# RFMicronHermes_1_1.net
KiCad netlist of a schematic drawn in EAGLE
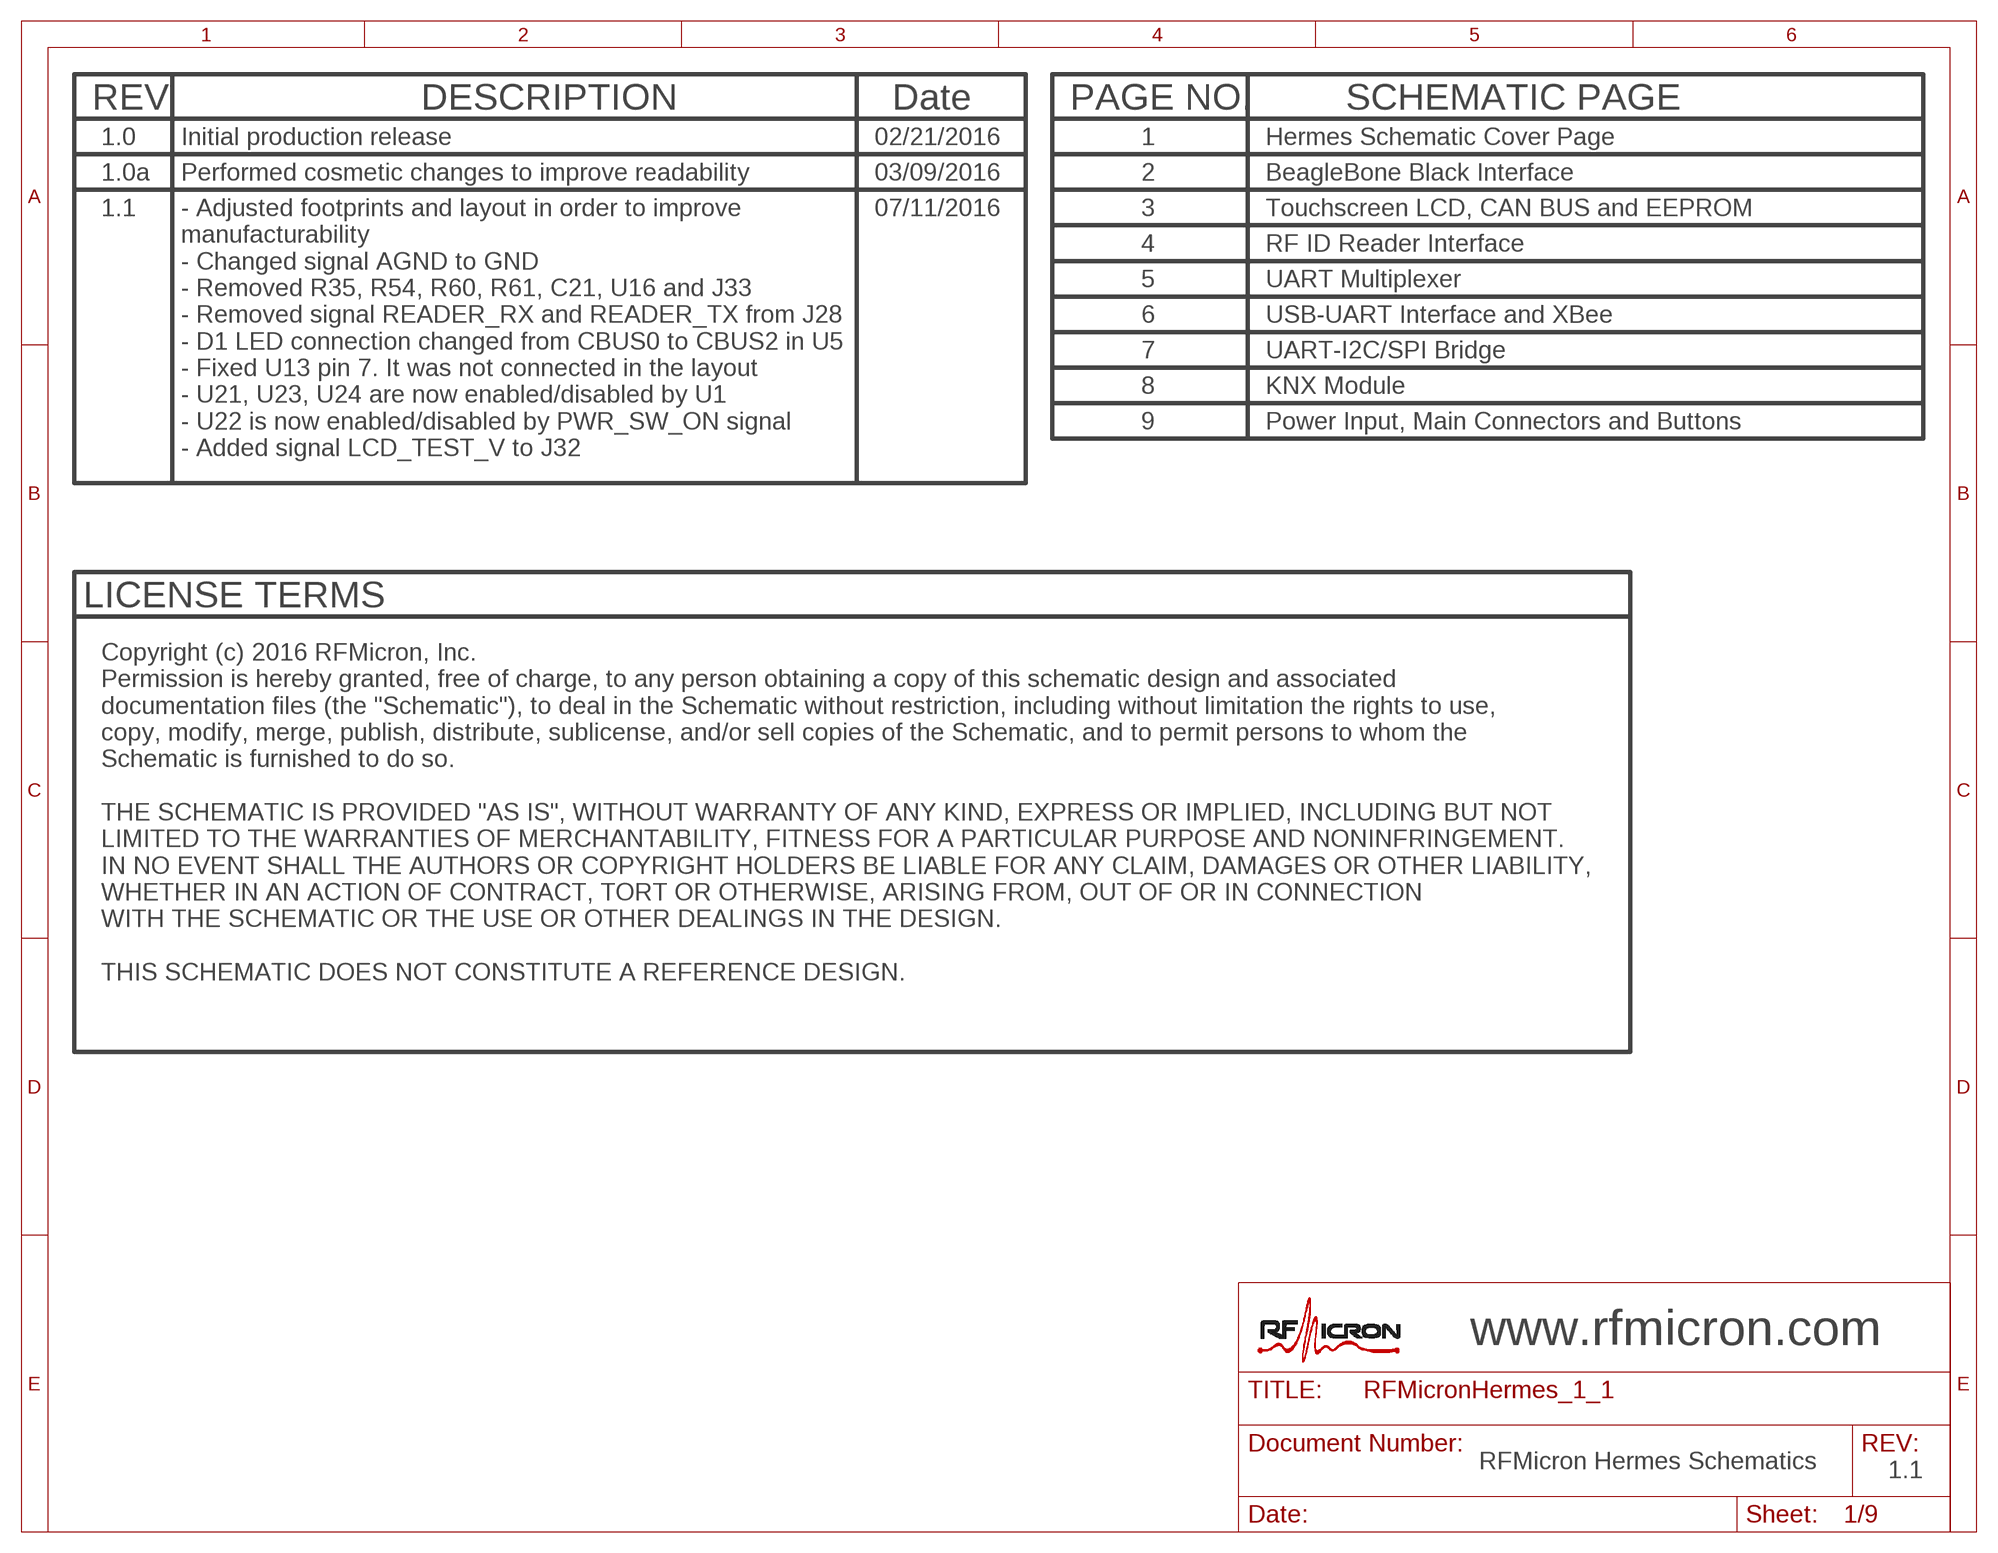
[diagram p0: schematic, sheet 1]
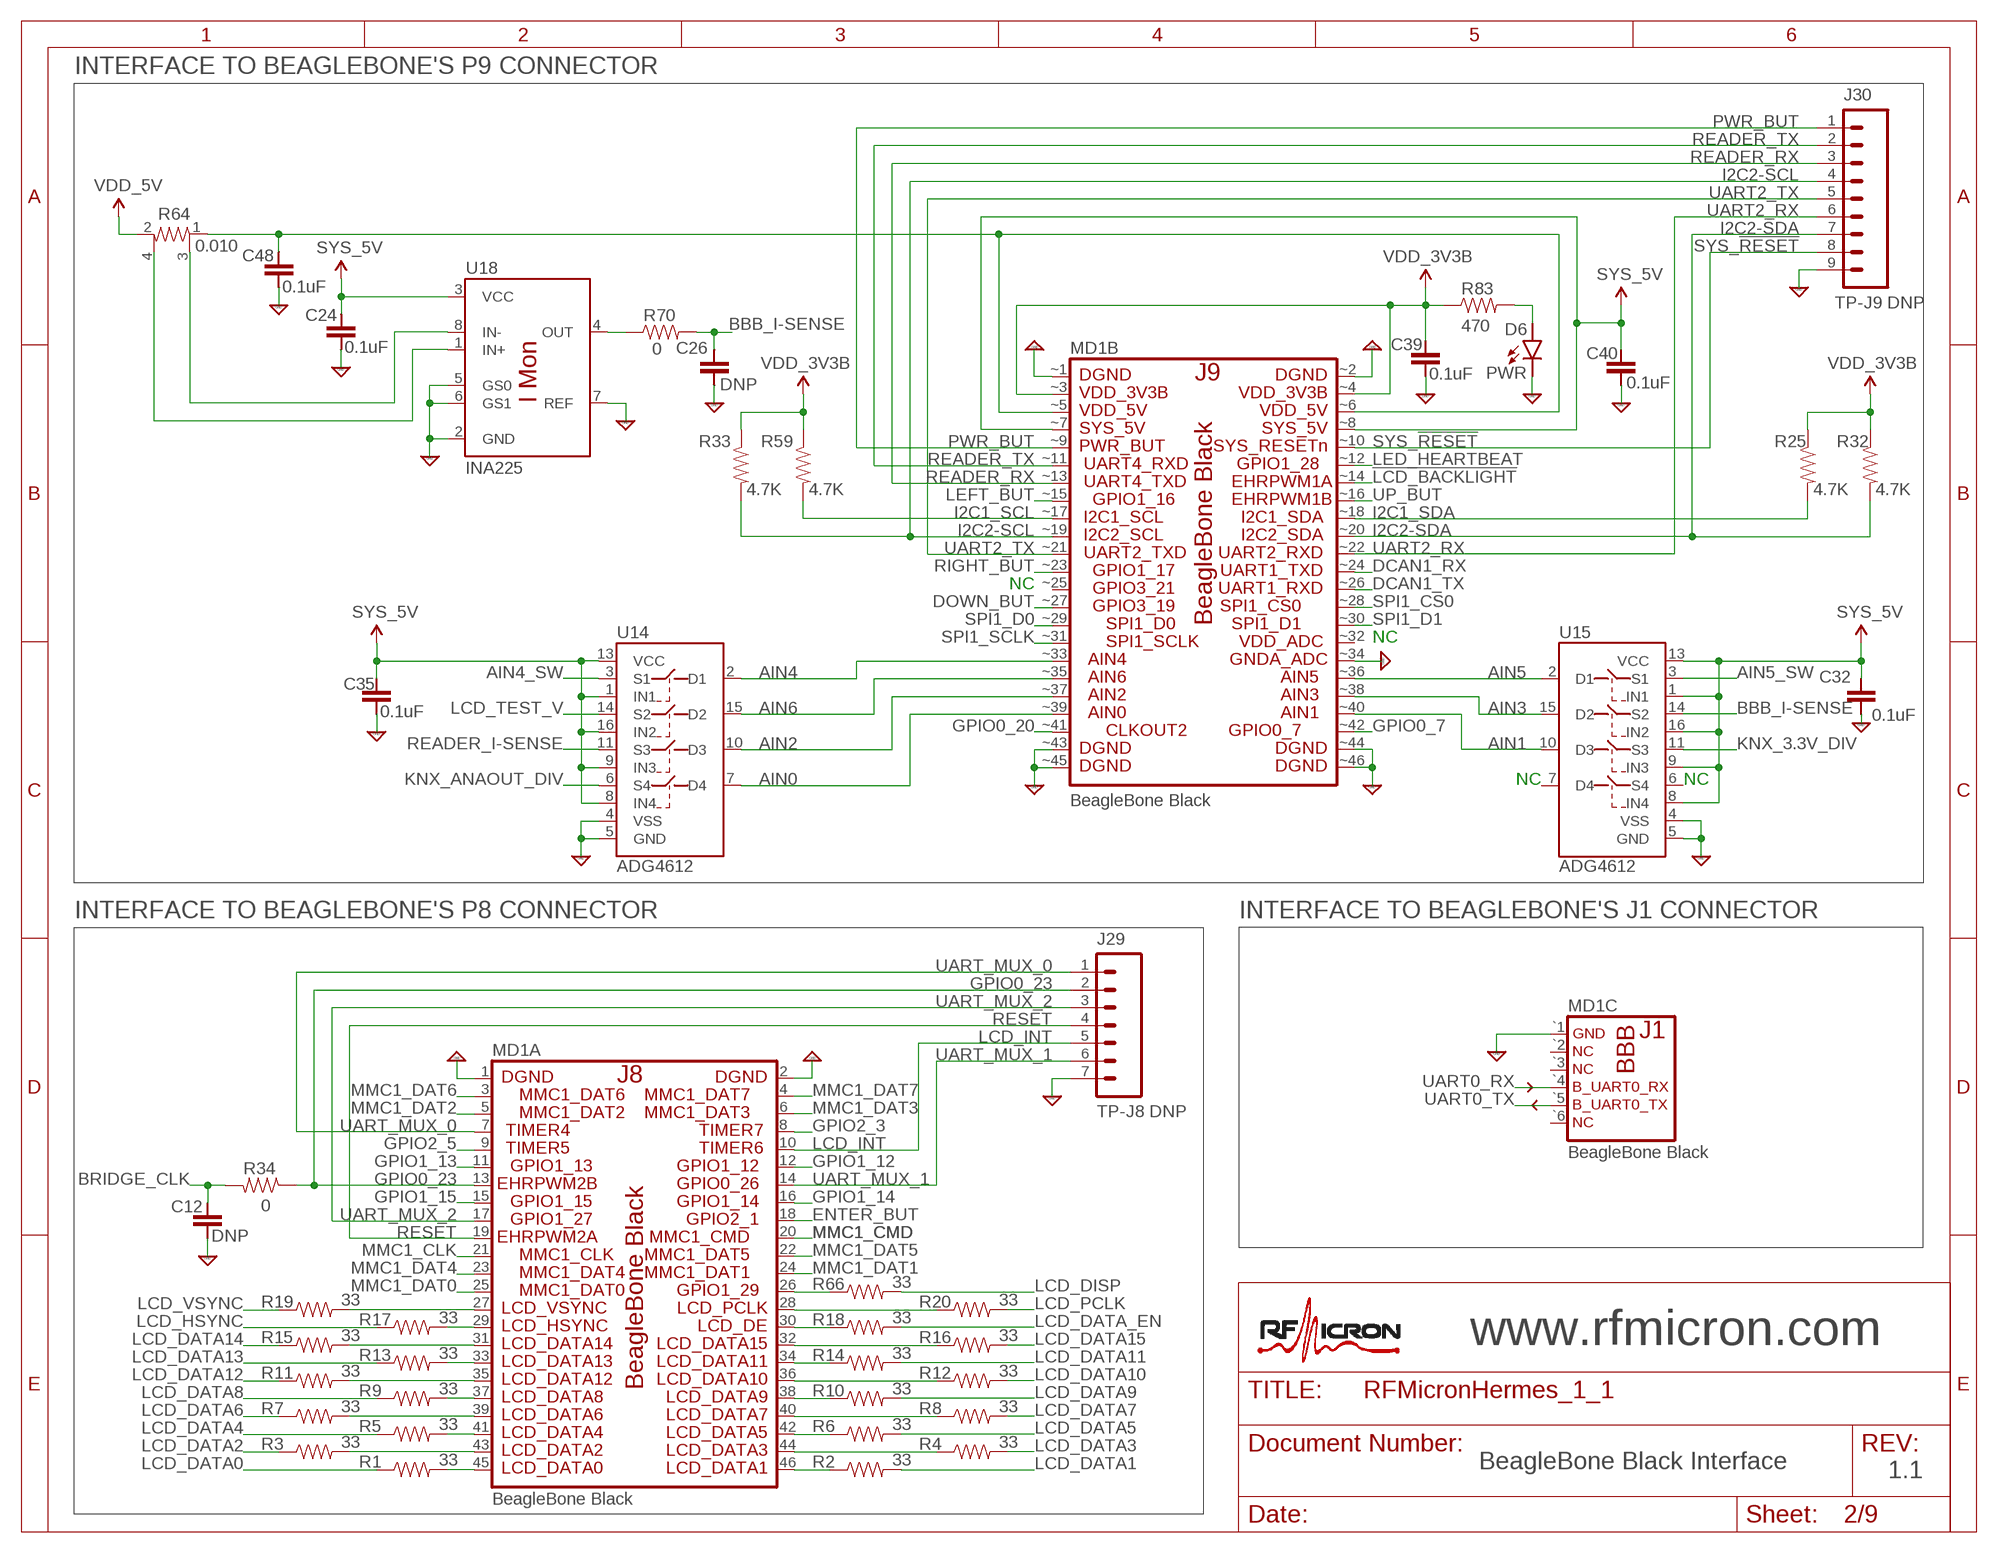
[diagram p1: schematic, sheet 2]
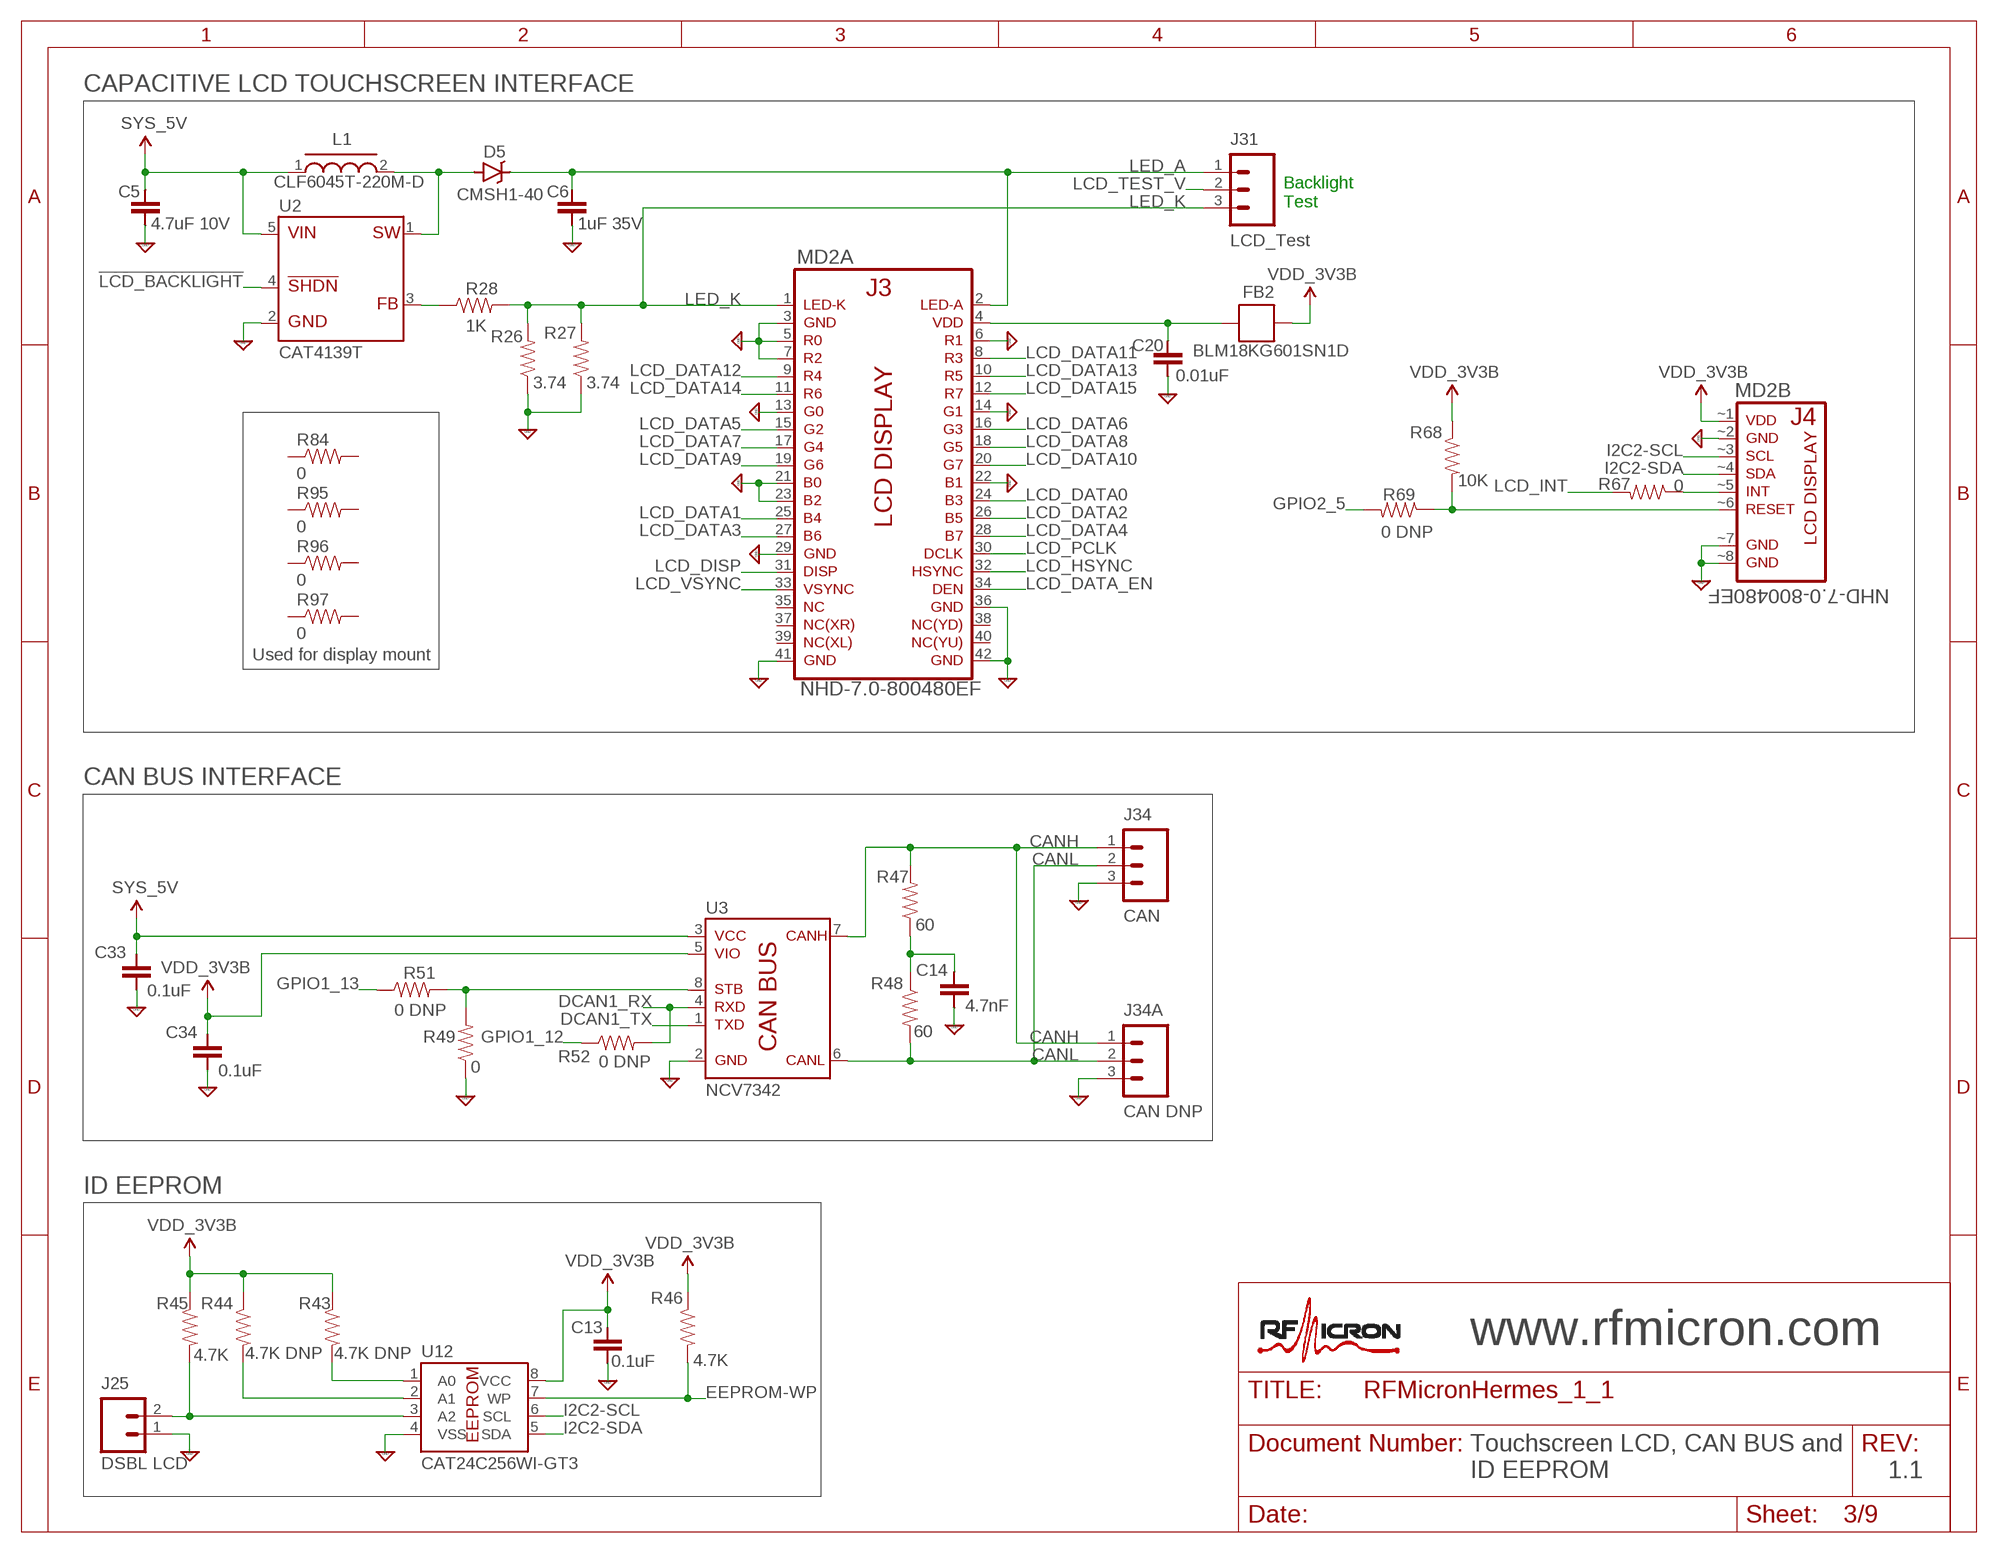
[diagram p2: schematic, sheet 3]
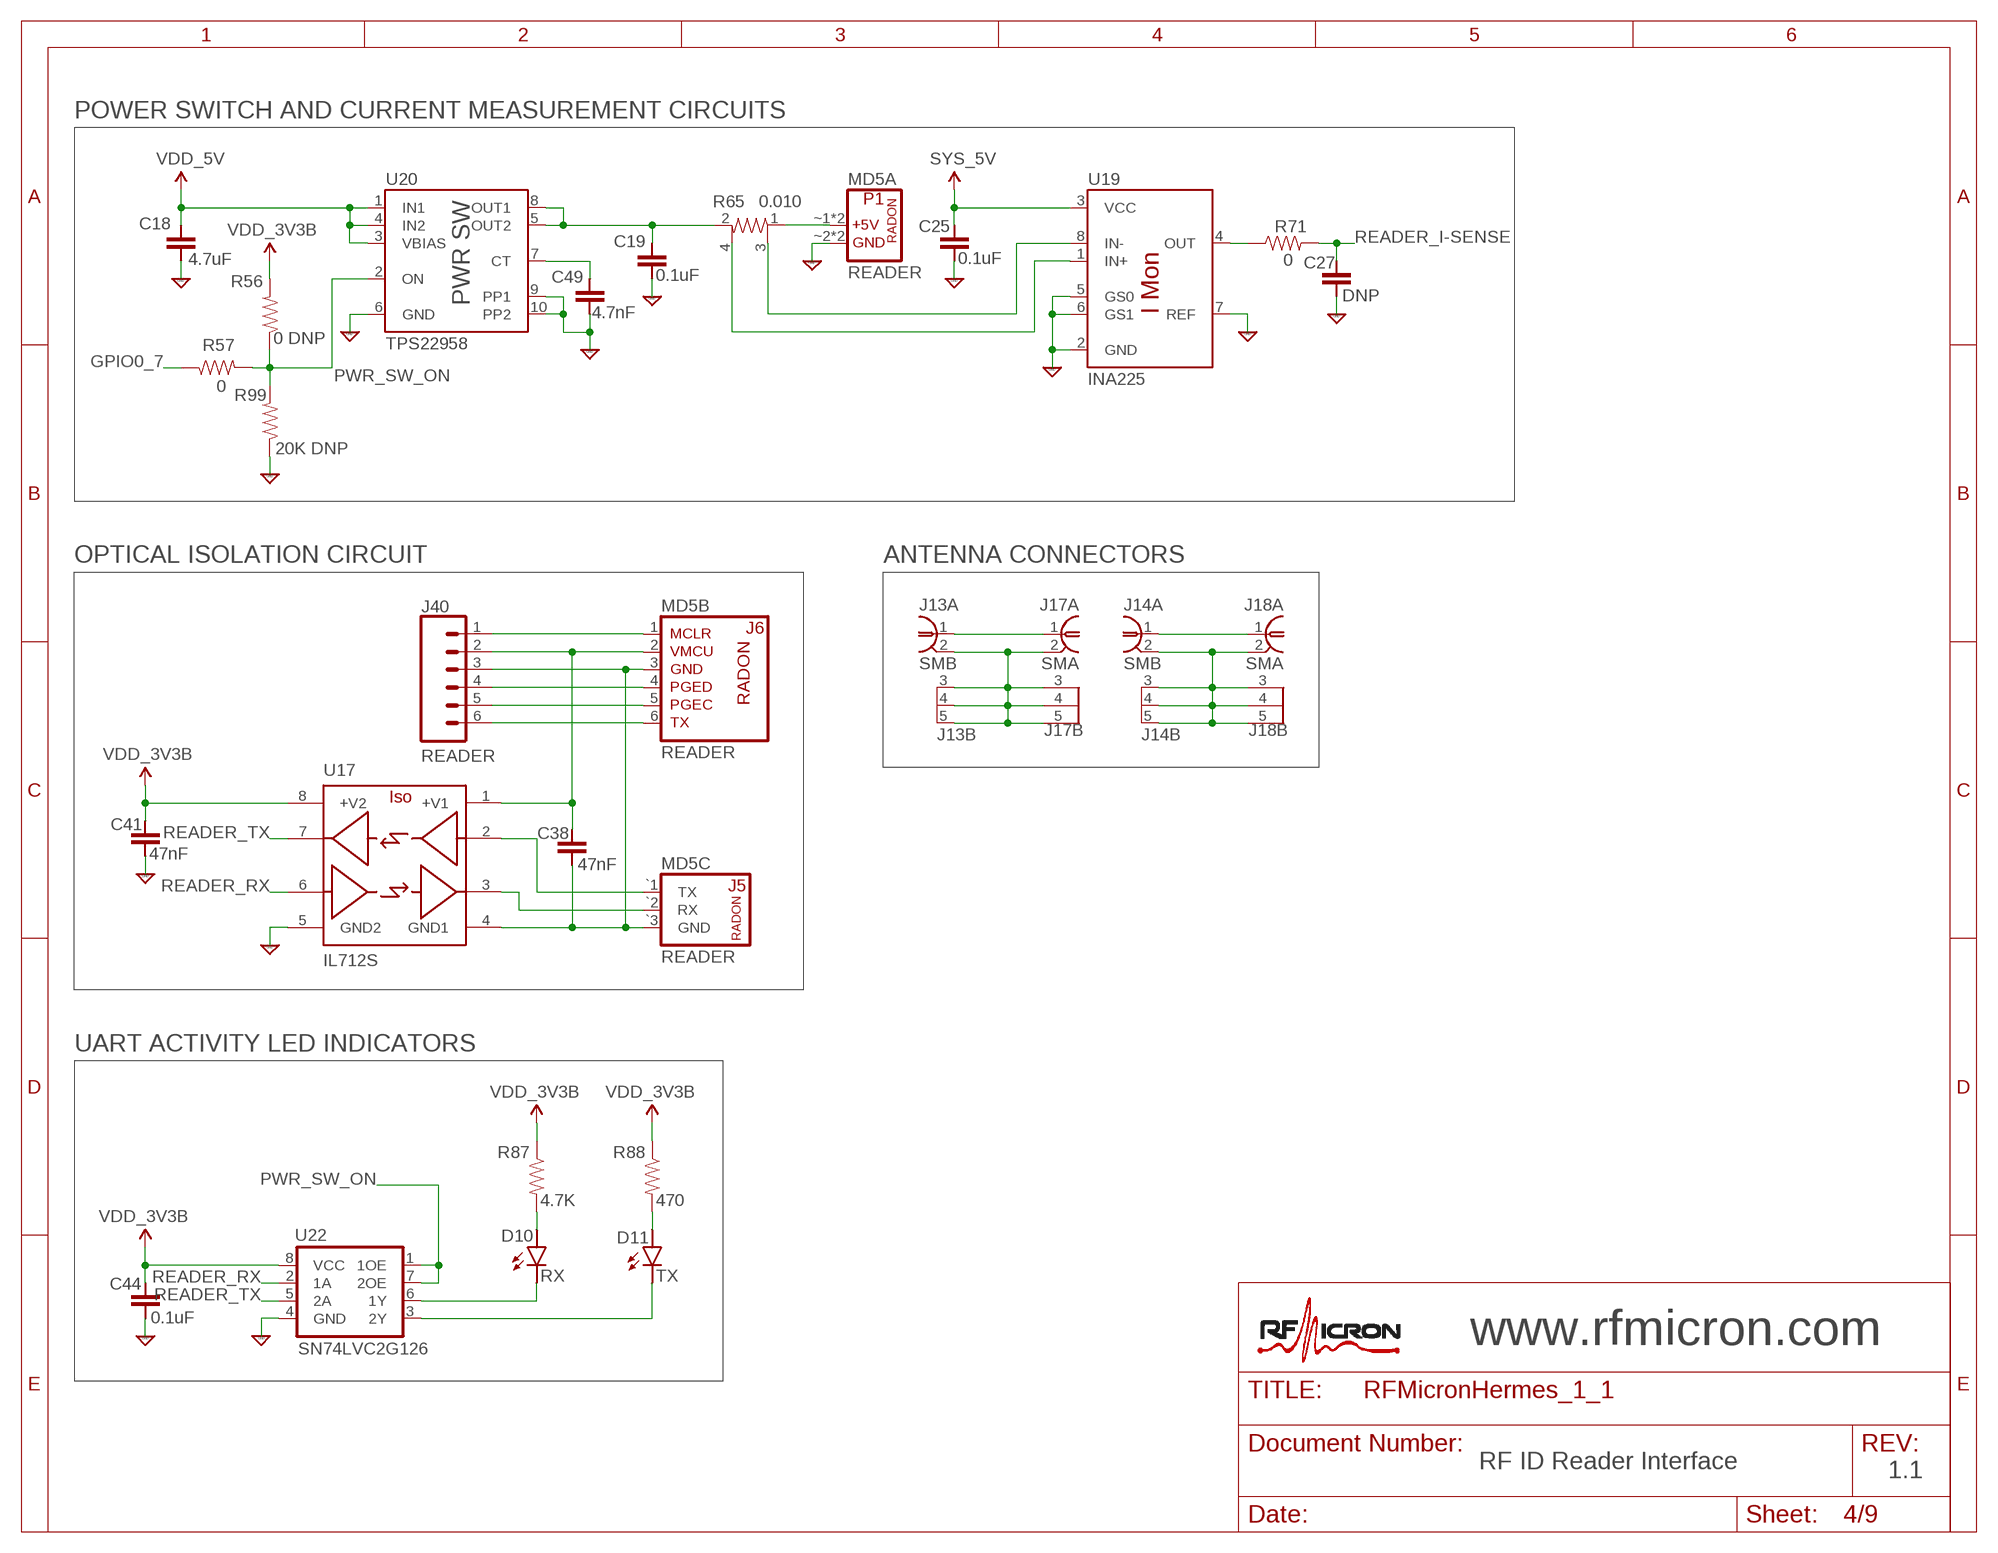
[diagram p3: schematic, sheet 4]
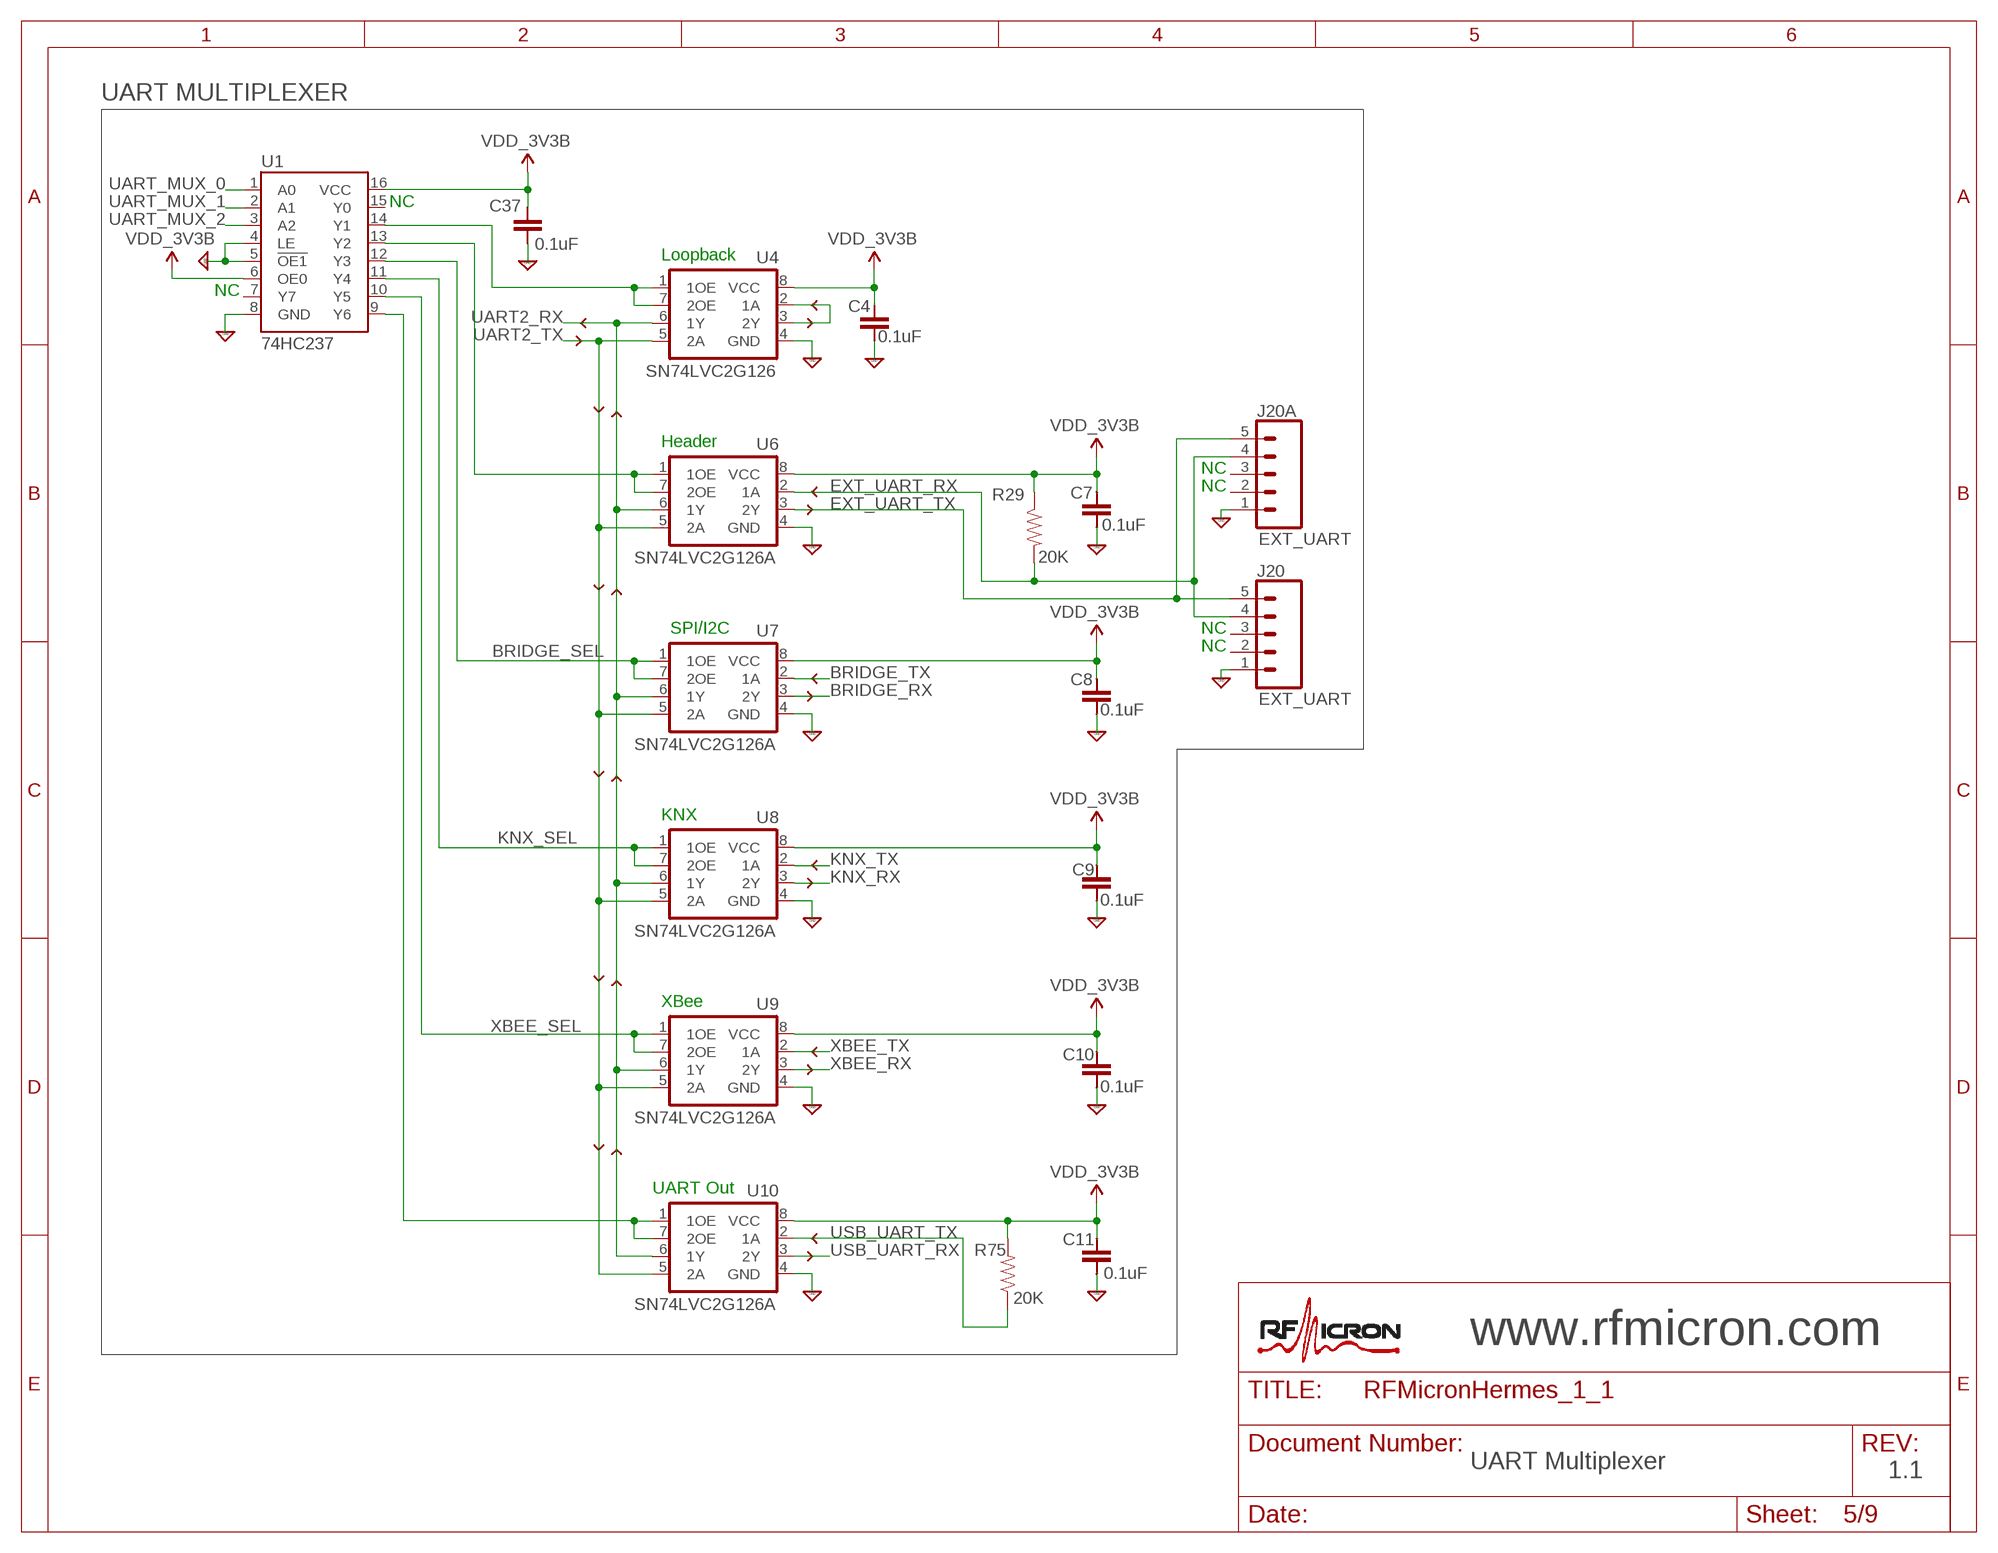
[diagram p4: schematic, sheet 5]
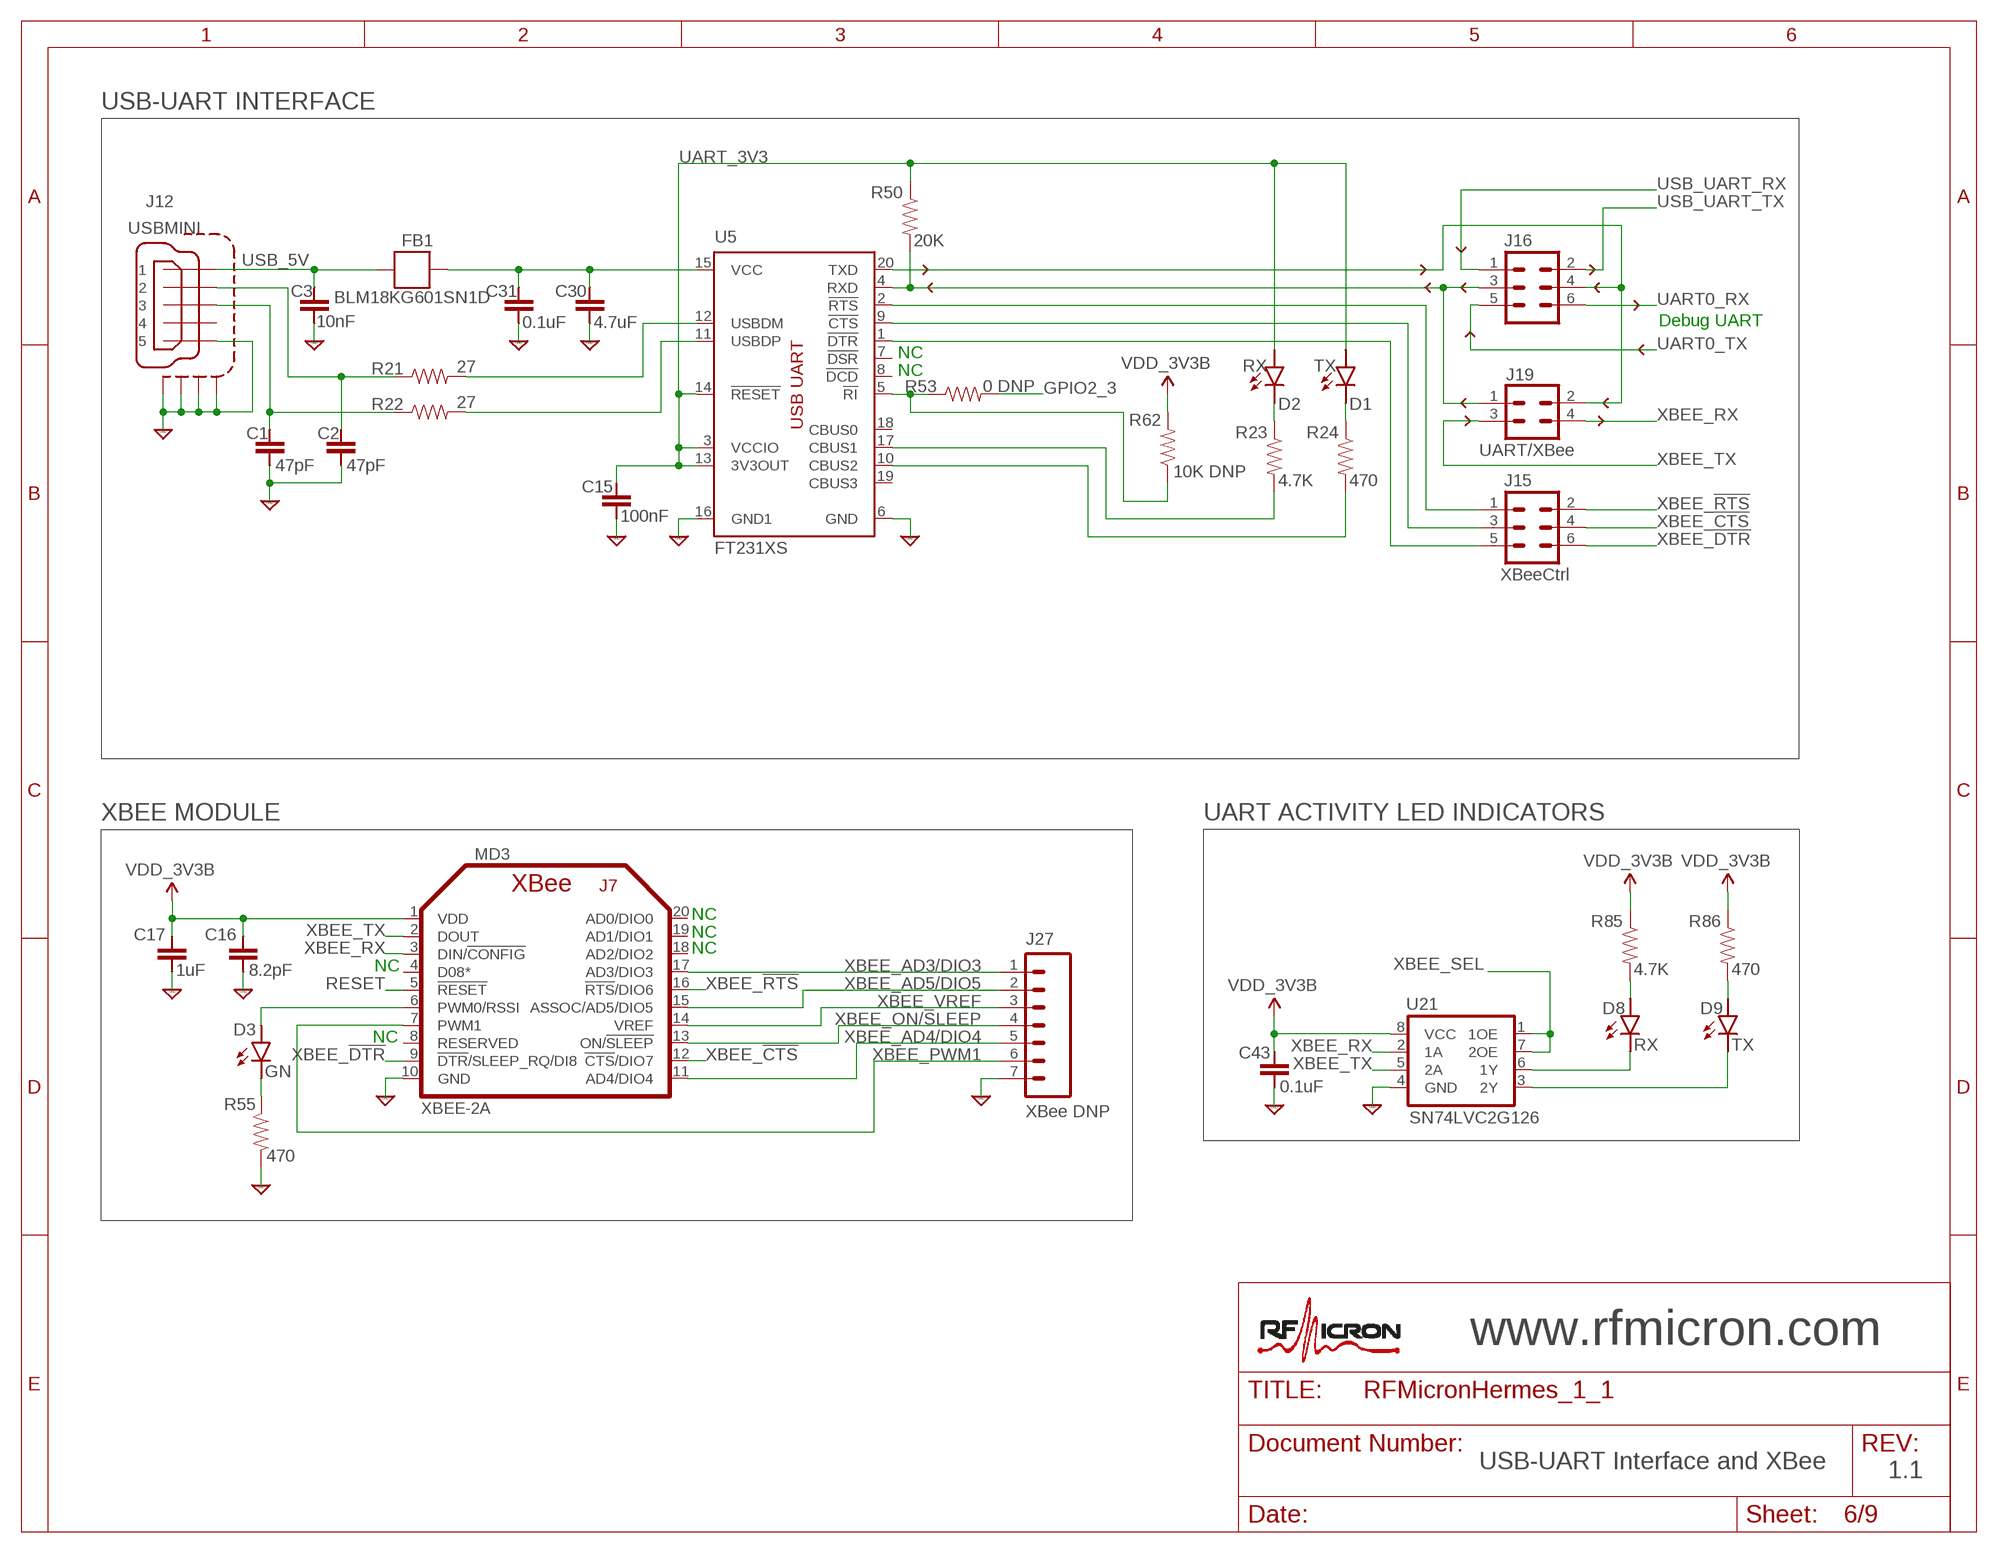
[diagram p5: schematic, sheet 6]
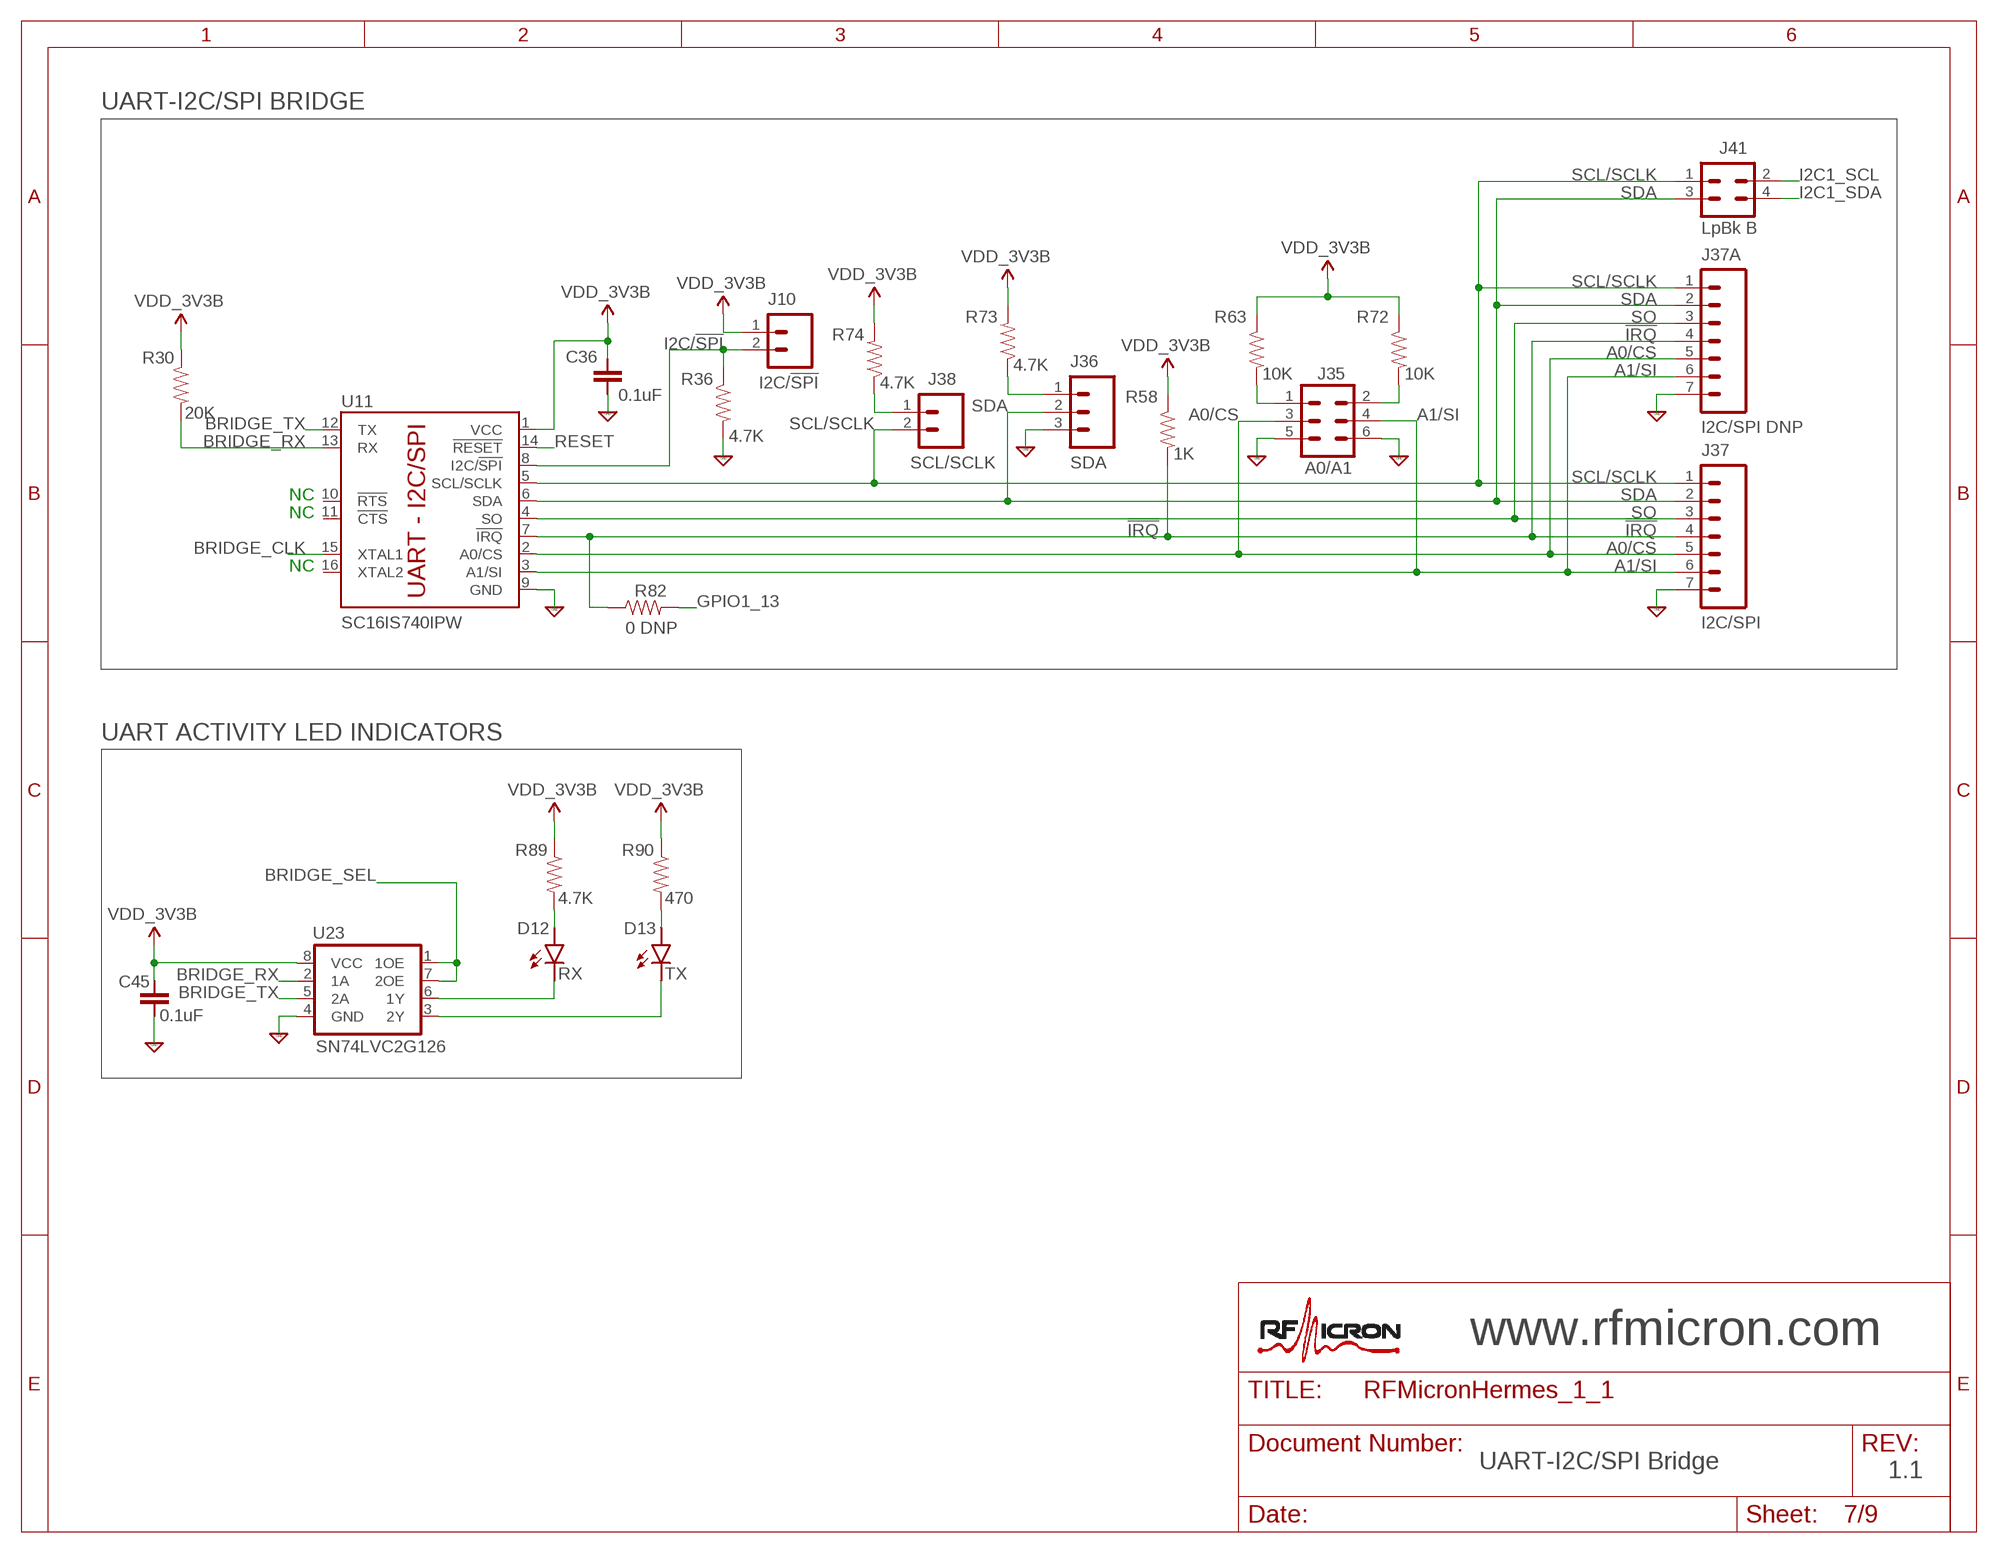
[diagram p6: schematic, sheet 7]
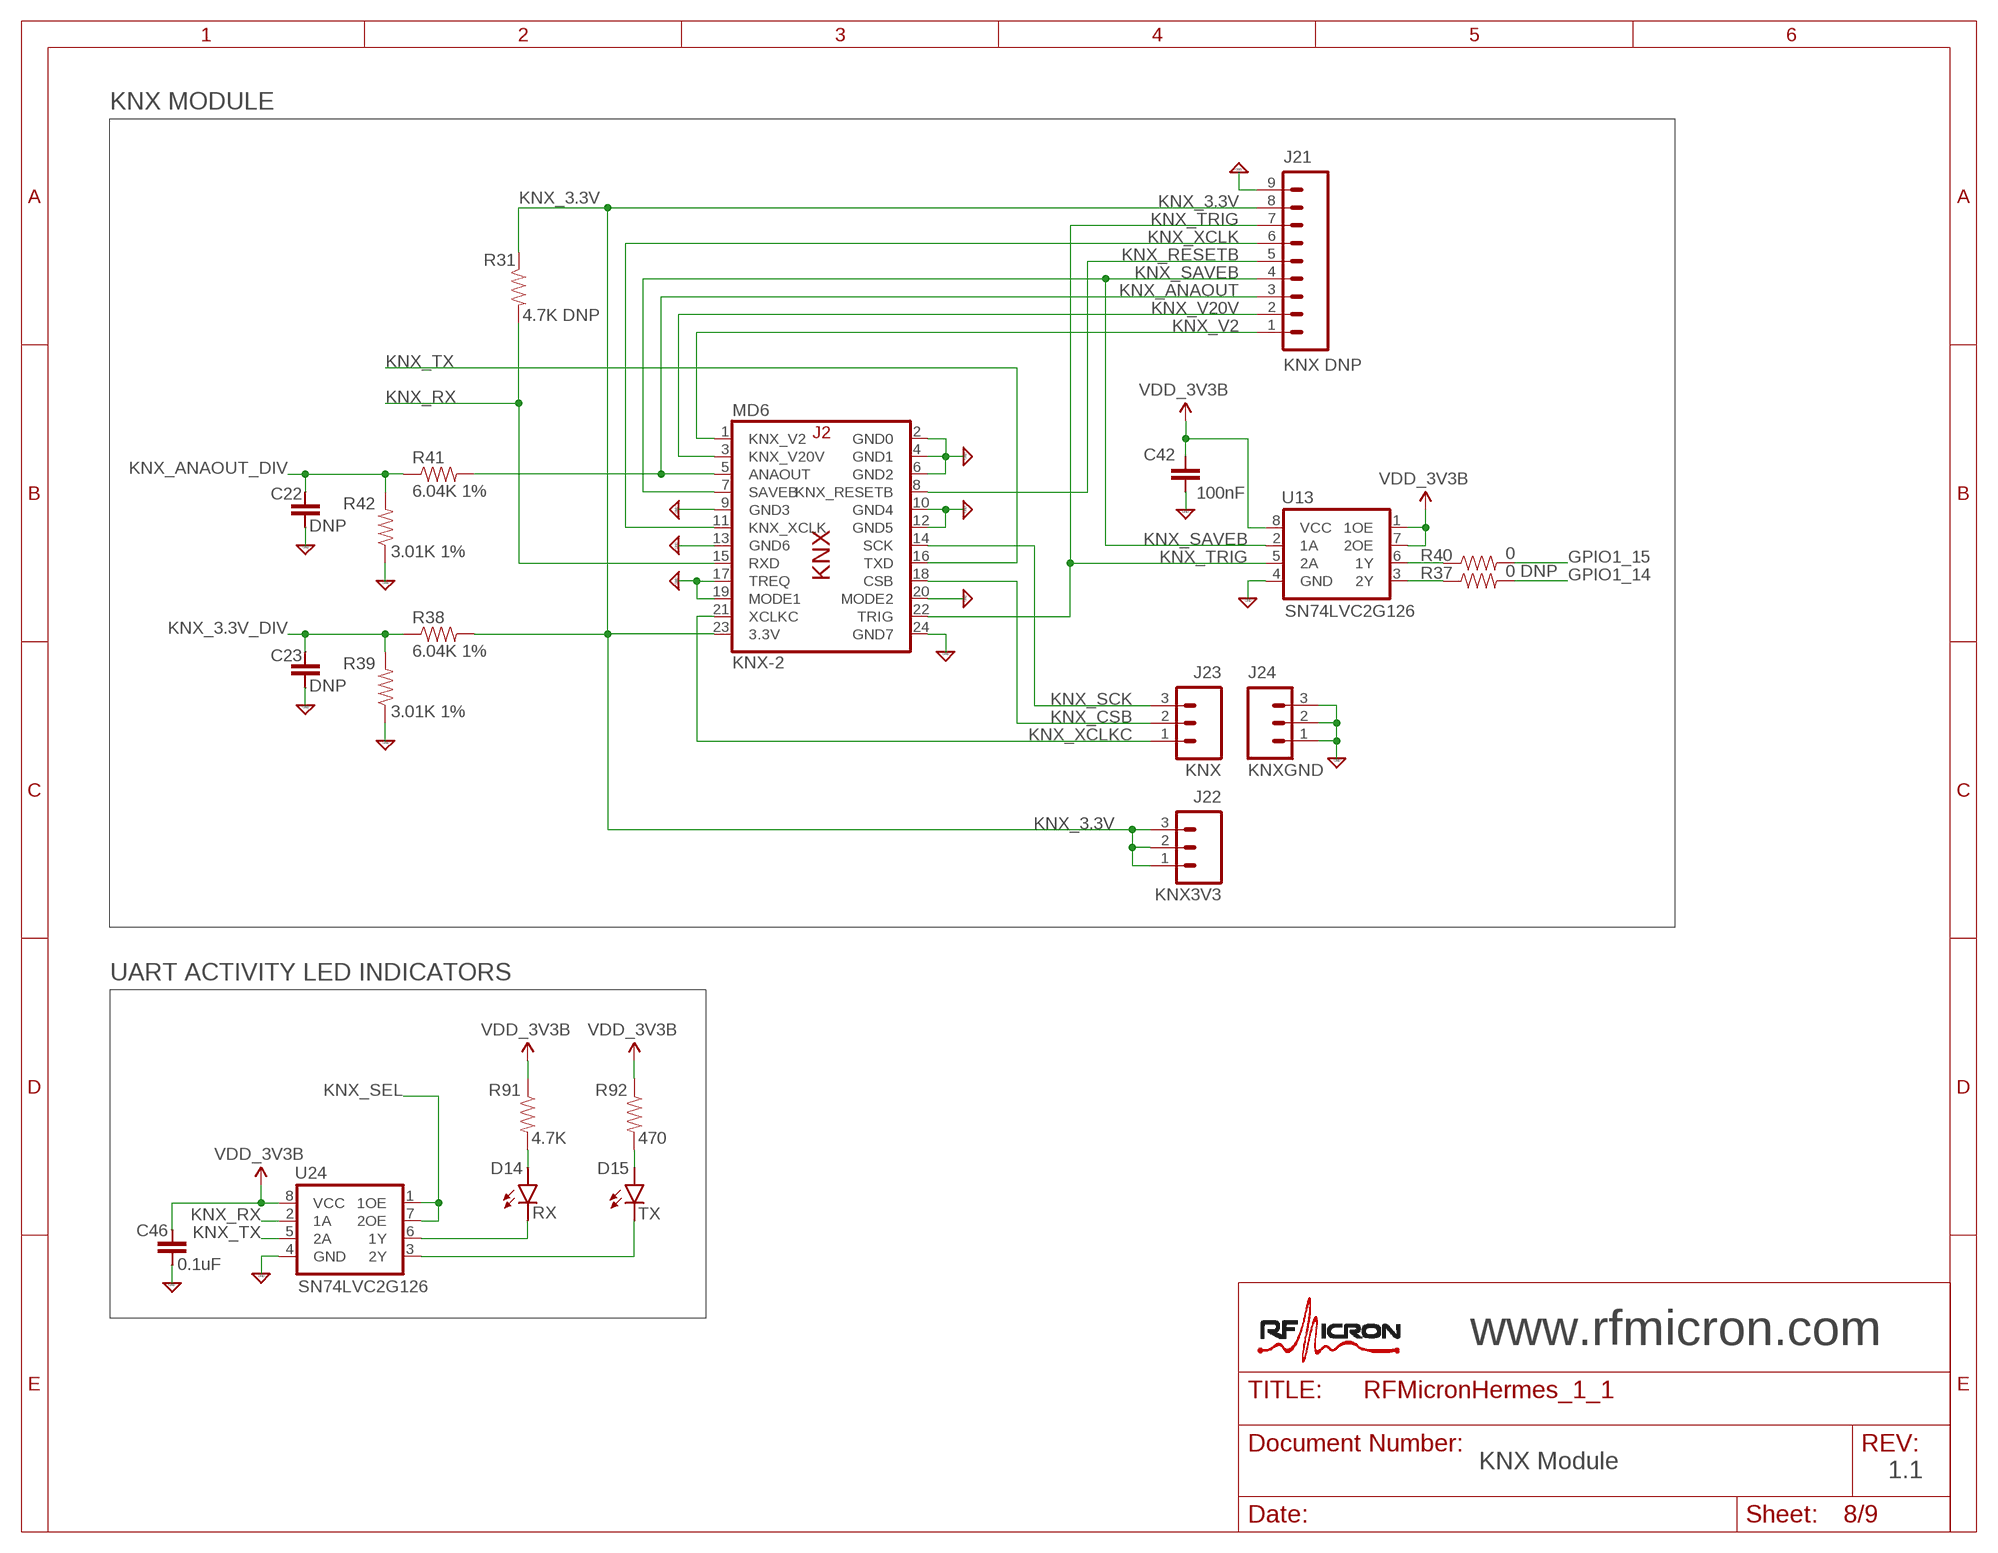
[diagram p7: schematic, sheet 8]
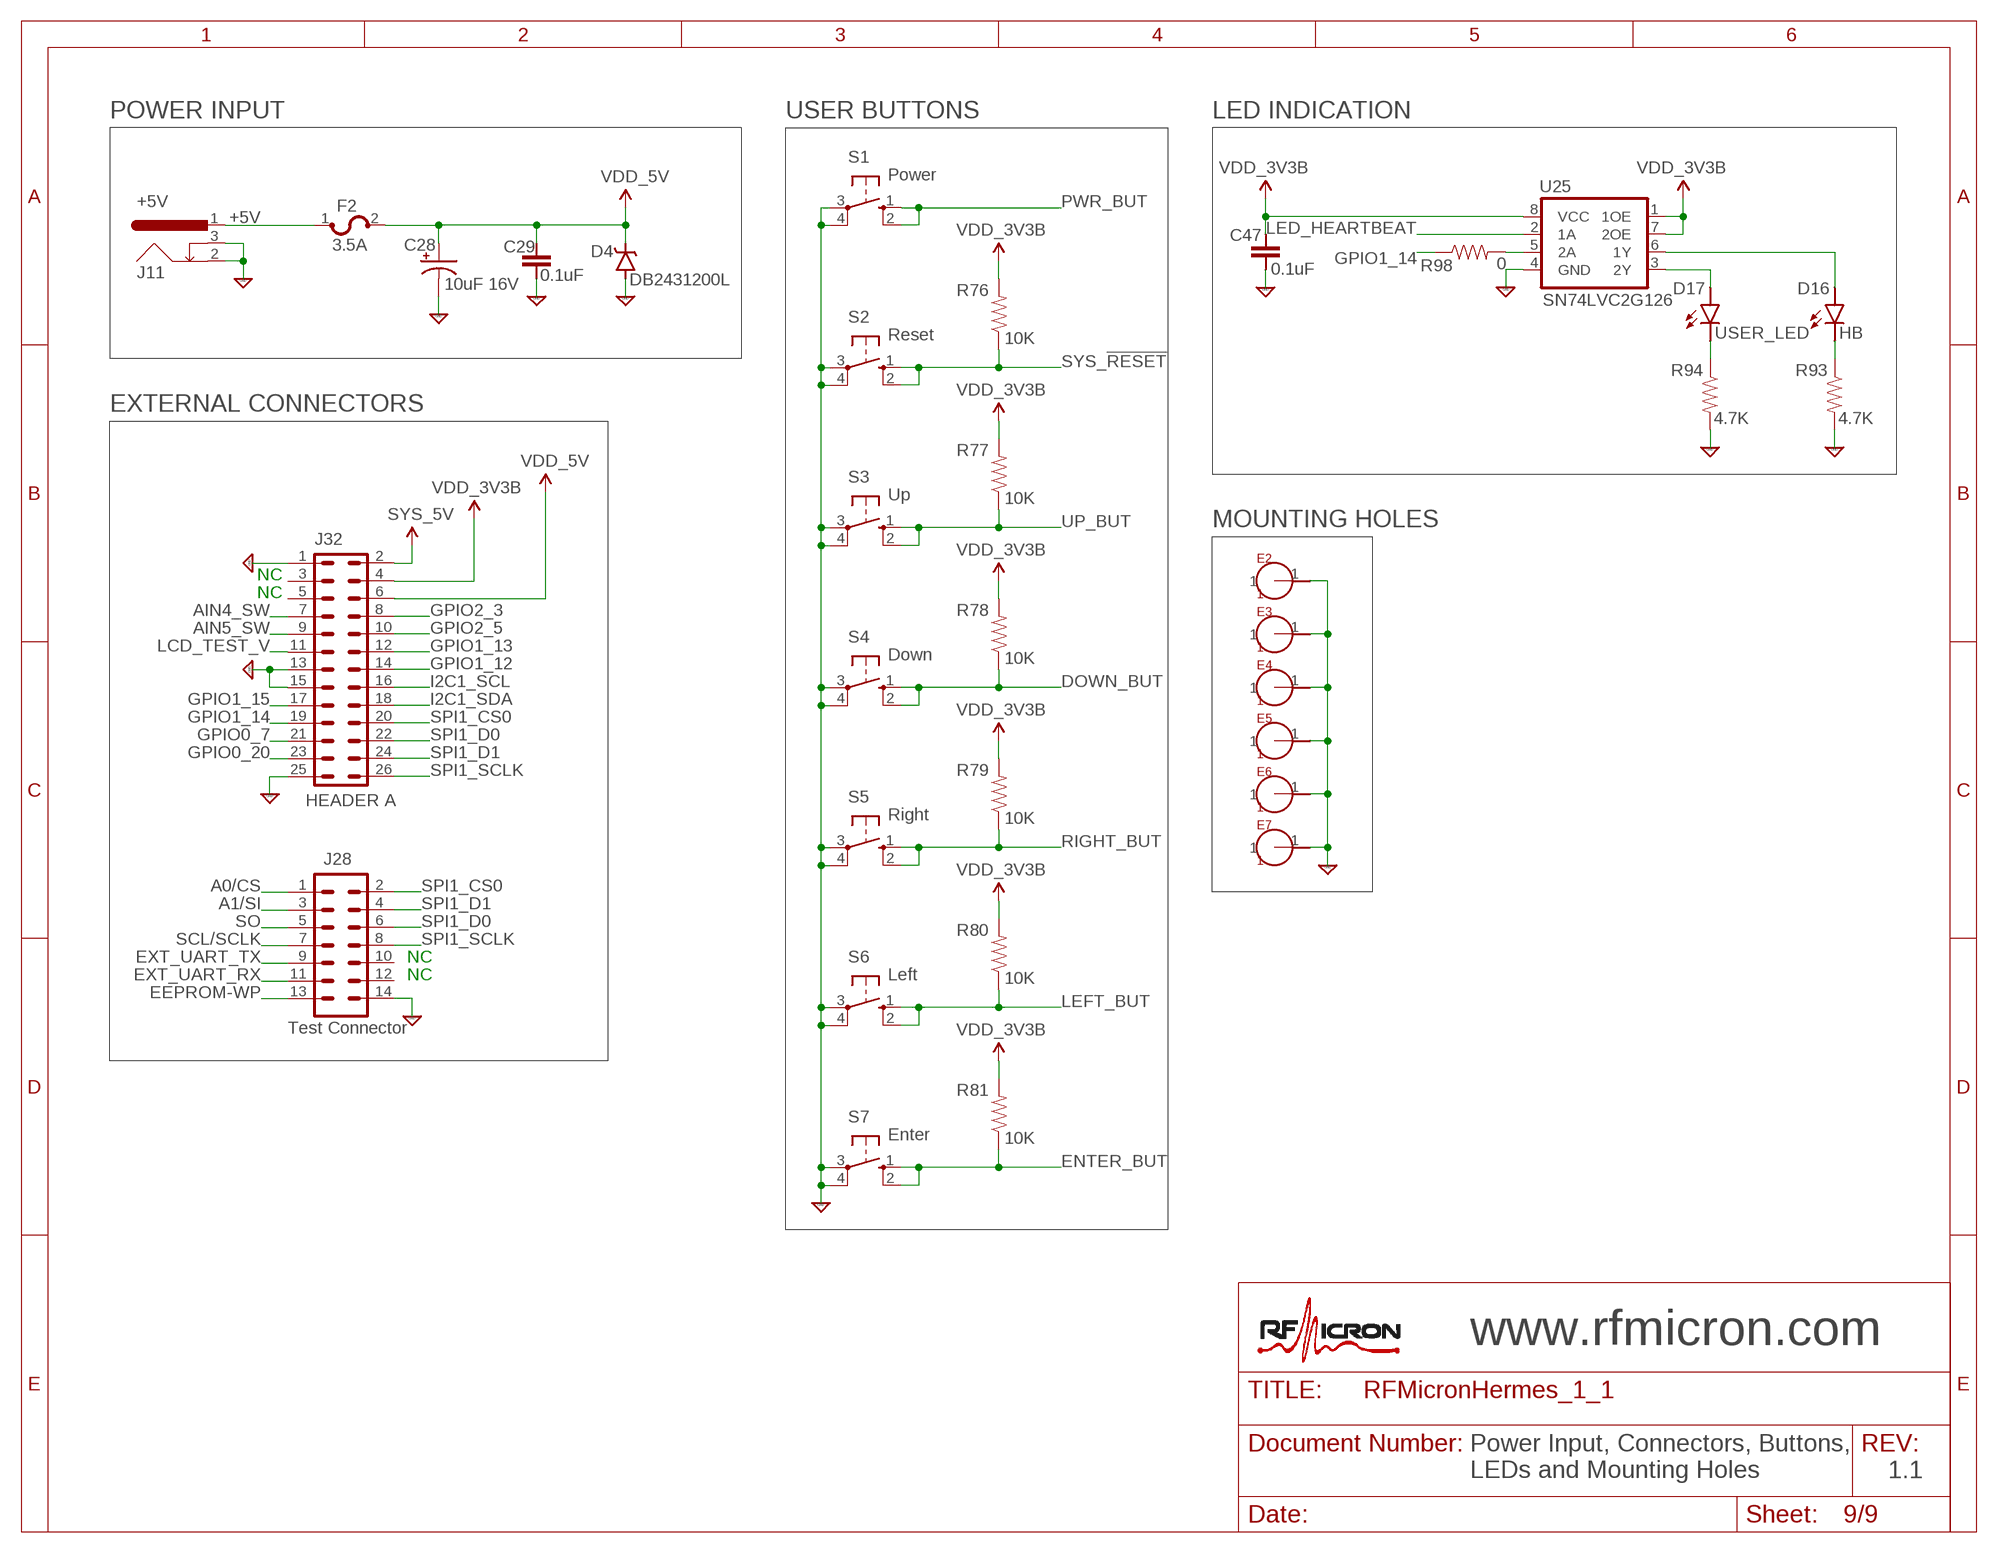
[diagram p8: schematic, sheet 9]

(export (version "E")
  (design (tool "Eeschema 10.0.6"))
  (components
    (comp (ref "C18")
      (value "4.7uF")
      (footprint "eagle-import:C0603K")
      (libsource (lib "eagle-import") (part "CAPC"))
    )
    (comp (ref "C19")
      (value "0.1uF")
      (footprint "eagle-import:C0603K")
      (libsource (lib "eagle-import") (part "CAPC"))
    )
    (comp (ref "C25")
      (value "0.1uF")
      (footprint "eagle-import:C0603K")
      (libsource (lib "eagle-import") (part "CAPC"))
    )
    (comp (ref "C27")
      (value "DNP")
      (footprint "eagle-import:C0603K")
      (libsource (lib "eagle-import") (part "CAPC"))
    )
    (comp (ref "C38")
      (value "47nF")
      (footprint "eagle-import:C0603K")
      (libsource (lib "eagle-import") (part "CAPC"))
    )
    (comp (ref "C41")
      (value "47nF")
      (footprint "eagle-import:C0603K")
      (libsource (lib "eagle-import") (part "CAPC"))
    )
    (comp (ref "C44")
      (value "0.1uF")
      (footprint "eagle-import:C0603K")
      (libsource (lib "eagle-import") (part "CAPC"))
    )
    (comp (ref "C49")
      (value "4.7nF")
      (footprint "eagle-import:C0603K")
      (libsource (lib "eagle-import") (part "CAPC"))
    )
    (comp (ref "D10")
      (value "RX")
      (footprint "eagle-import:LED-1206")
      (libsource (lib "eagle-import") (part "LED1206"))
    )
    (comp (ref "D11")
      (value "TX")
      (footprint "eagle-import:LED-1206")
      (libsource (lib "eagle-import") (part "LED1206"))
    )
    (comp (ref "J13")
      (value "SMB")
      (footprint "eagle-import:SMB-SMD")
      (libsource (lib "eagle-import") (part "SMB-SMDA"))
    )
    (comp (ref "J14")
      (value "SMB")
      (footprint "eagle-import:SMB-SMD")
      (libsource (lib "eagle-import") (part "SMB-SMDA"))
    )
    (comp (ref "J17")
      (value "SMA")
      (footprint "eagle-import:SMA-EDGE")
      (libsource (lib "eagle-import") (part "BNC-SMA-EDGESMA-ONLY"))
    )
    (comp (ref "J18")
      (value "SMA")
      (footprint "eagle-import:SMA-EDGE")
      (libsource (lib "eagle-import") (part "BNC-SMA-EDGESMA-ONLY"))
    )
    (comp (ref "J40")
      (value "READER")
      (footprint "eagle-import:1X06")
      (libsource (lib "eagle-import") (part "M06SIP"))
    )
    (comp (ref "MD5")
      (value "READER")
      (footprint "eagle-import:RADON_RFID_READ")
      (libsource (lib "eagle-import") (part "RADON_RFID_READ"))
    )
    (comp (ref "R56")
      (value "0 DNP")
      (footprint "eagle-import:R0603")
      (libsource (lib "eagle-import") (part "RESISTORR0603"))
    )
    (comp (ref "R57")
      (value "0")
      (footprint "eagle-import:R0603")
      (libsource (lib "eagle-import") (part "RESISTORR0603"))
    )
    (comp (ref "R65")
      (value "0.010")
      (footprint "eagle-import:RESIST_4-TERM_VISHAY")
      (libsource (lib "eagle-import") (part "RESISTOR_4-TERM1"))
    )
    (comp (ref "R71")
      (value "0")
      (footprint "eagle-import:R0603")
      (libsource (lib "eagle-import") (part "RESISTORR0603"))
    )
    (comp (ref "R87")
      (value "4.7K")
      (footprint "eagle-import:R0603")
      (libsource (lib "eagle-import") (part "RESISTORR0603"))
    )
    (comp (ref "R88")
      (value "470")
      (footprint "eagle-import:R0603")
      (libsource (lib "eagle-import") (part "RESISTORR0603"))
    )
    (comp (ref "R99")
      (value "20K DNP")
      (footprint "eagle-import:R0603")
      (libsource (lib "eagle-import") (part "RESISTORR0603"))
    )
    (comp (ref "U17")
      (value "IL712S")
      (footprint "eagle-import:SOIC08")
      (libsource (lib "eagle-import") (part "IL712S"))
    )
    (comp (ref "U19")
      (value "INA225")
      (footprint "eagle-import:MSOP8")
      (libsource (lib "eagle-import") (part "INA225"))
    )
    (comp (ref "U20")
      (value "TPS22958")
      (footprint "eagle-import:MSOP8-POWERPAD")
      (libsource (lib "eagle-import") (part "TPS22958POWERSWITCH"))
    )
    (comp (ref "U22")
      (value "SN74LVC2G126")
      (footprint "eagle-import:SM8-TI-A")
      (libsource (lib "eagle-import") (part "SN74LVC2G126-ALTA"))
    )
    (comp (ref "C12")
      (value "DNP")
      (footprint "eagle-import:C0603K")
      (libsource (lib "eagle-import") (part "CAPC"))
    )
    (comp (ref "C24")
      (value "0.1uF")
      (footprint "eagle-import:C0603K")
      (libsource (lib "eagle-import") (part "CAPC"))
    )
    (comp (ref "C26")
      (value "DNP")
      (footprint "eagle-import:C0603K")
      (libsource (lib "eagle-import") (part "CAPC"))
    )
    (comp (ref "C32")
      (value "0.1uF")
      (footprint "eagle-import:C0603K")
      (libsource (lib "eagle-import") (part "CAPC"))
    )
    (comp (ref "C35")
      (value "0.1uF")
      (footprint "eagle-import:C0603K")
      (libsource (lib "eagle-import") (part "CAPC"))
    )
    (comp (ref "C39")
      (value "0.1uF")
      (footprint "eagle-import:C0603K")
      (libsource (lib "eagle-import") (part "CAPC"))
    )
    (comp (ref "C40")
      (value "0.1uF")
      (footprint "eagle-import:C0603K")
      (libsource (lib "eagle-import") (part "CAPC"))
    )
    (comp (ref "C48")
      (value "0.1uF")
      (footprint "eagle-import:C0603K")
      (libsource (lib "eagle-import") (part "CAPC"))
    )
    (comp (ref "D6")
      (value "PWR")
      (footprint "eagle-import:LED-1206")
      (libsource (lib "eagle-import") (part "LED1206"))
    )
    (comp (ref "J29")
      (value "TP-J8 DNP")
      (footprint "eagle-import:1X07-SPECIAL")
      (libsource (lib "eagle-import") (part "M07SP"))
    )
    (comp (ref "J30")
      (value "TP-J9 DNP")
      (footprint "eagle-import:1X09-SPECIAL")
      (libsource (lib "eagle-import") (part "M09SPECIAL"))
    )
    (comp (ref "MD1")
      (value "BeagleBone Black")
      (footprint "eagle-import:BBONE_BK")
      (libsource (lib "eagle-import") (part "BBONE_BKBOT_UP"))
    )
    (comp (ref "R1")
      (value "33")
      (footprint "eagle-import:R0603")
      (libsource (lib "eagle-import") (part "RESISTORR0603"))
    )
    (comp (ref "R2")
      (value "33")
      (footprint "eagle-import:R0603")
      (libsource (lib "eagle-import") (part "RESISTORR0603"))
    )
    (comp (ref "R3")
      (value "33")
      (footprint "eagle-import:R0603")
      (libsource (lib "eagle-import") (part "RESISTORR0603"))
    )
    (comp (ref "R4")
      (value "33")
      (footprint "eagle-import:R0603")
      (libsource (lib "eagle-import") (part "RESISTORR0603"))
    )
    (comp (ref "R5")
      (value "33")
      (footprint "eagle-import:R0603")
      (libsource (lib "eagle-import") (part "RESISTORR0603"))
    )
    (comp (ref "R6")
      (value "33")
      (footprint "eagle-import:R0603")
      (libsource (lib "eagle-import") (part "RESISTORR0603"))
    )
    (comp (ref "R7")
      (value "33")
      (footprint "eagle-import:R0603")
      (libsource (lib "eagle-import") (part "RESISTORR0603"))
    )
    (comp (ref "R8")
      (value "33")
      (footprint "eagle-import:R0603")
      (libsource (lib "eagle-import") (part "RESISTORR0603"))
    )
    (comp (ref "R9")
      (value "33")
      (footprint "eagle-import:R0603")
      (libsource (lib "eagle-import") (part "RESISTORR0603"))
    )
    (comp (ref "R10")
      (value "33")
      (footprint "eagle-import:R0603")
      (libsource (lib "eagle-import") (part "RESISTORR0603"))
    )
    (comp (ref "R11")
      (value "33")
      (footprint "eagle-import:R0603")
      (libsource (lib "eagle-import") (part "RESISTORR0603"))
    )
    (comp (ref "R12")
      (value "33")
      (footprint "eagle-import:R0603")
      (libsource (lib "eagle-import") (part "RESISTORR0603"))
    )
    (comp (ref "R13")
      (value "33")
      (footprint "eagle-import:R0603")
      (libsource (lib "eagle-import") (part "RESISTORR0603"))
    )
    (comp (ref "R14")
      (value "33")
      (footprint "eagle-import:R0603")
      (libsource (lib "eagle-import") (part "RESISTORR0603"))
    )
    (comp (ref "R15")
      (value "33")
      (footprint "eagle-import:R0603")
      (libsource (lib "eagle-import") (part "RESISTORR0603"))
    )
    (comp (ref "R16")
      (value "33")
      (footprint "eagle-import:R0603")
      (libsource (lib "eagle-import") (part "RESISTORR0603"))
    )
    (comp (ref "R17")
      (value "33")
      (footprint "eagle-import:R0603")
      (libsource (lib "eagle-import") (part "RESISTORR0603"))
    )
    (comp (ref "R18")
      (value "33")
      (footprint "eagle-import:R0603")
      (libsource (lib "eagle-import") (part "RESISTORR0603"))
    )
    (comp (ref "R19")
      (value "33")
      (footprint "eagle-import:R0603")
      (libsource (lib "eagle-import") (part "RESISTORR0603"))
    )
    (comp (ref "R20")
      (value "33")
      (footprint "eagle-import:R0603")
      (libsource (lib "eagle-import") (part "RESISTORR0603"))
    )
    (comp (ref "R25")
      (value "4.7K")
      (footprint "eagle-import:R0603")
      (libsource (lib "eagle-import") (part "RESISTORR0603"))
    )
    (comp (ref "R32")
      (value "4.7K")
      (footprint "eagle-import:R0603")
      (libsource (lib "eagle-import") (part "RESISTORR0603"))
    )
    (comp (ref "R33")
      (value "4.7K")
      (footprint "eagle-import:R0603")
      (libsource (lib "eagle-import") (part "RESISTORR0603"))
    )
    (comp (ref "R34")
      (value "0")
      (footprint "eagle-import:R0603")
      (libsource (lib "eagle-import") (part "RESISTORR0603"))
    )
    (comp (ref "R59")
      (value "4.7K")
      (footprint "eagle-import:R0603")
      (libsource (lib "eagle-import") (part "RESISTORR0603"))
    )
    (comp (ref "R64")
      (value "0.010")
      (footprint "eagle-import:RESIST_4-TERM_VISHAY")
      (libsource (lib "eagle-import") (part "RESISTOR_4-TERM1"))
    )
    (comp (ref "R66")
      (value "33")
      (footprint "eagle-import:R0603")
      (libsource (lib "eagle-import") (part "RESISTORR0603"))
    )
    (comp (ref "R70")
      (value "0")
      (footprint "eagle-import:R0603")
      (libsource (lib "eagle-import") (part "RESISTORR0603"))
    )
    (comp (ref "R83")
      (value "470")
      (footprint "eagle-import:R0603")
      (libsource (lib "eagle-import") (part "RESISTORR0603"))
    )
    (comp (ref "U14")
      (value "ADG4612")
      (footprint "eagle-import:TSSOP16")
      (libsource (lib "eagle-import") (part "ADG4612"))
    )
    (comp (ref "U15")
      (value "ADG4612")
      (footprint "eagle-import:TSSOP16")
      (libsource (lib "eagle-import") (part "ADG4612"))
    )
    (comp (ref "U18")
      (value "INA225")
      (footprint "eagle-import:MSOP8")
      (libsource (lib "eagle-import") (part "INA225"))
    )
    (comp (ref "C36")
      (value "0.1uF")
      (footprint "eagle-import:C0603K")
      (libsource (lib "eagle-import") (part "CAPC"))
    )
    (comp (ref "C45")
      (value "0.1uF")
      (footprint "eagle-import:C0603K")
      (libsource (lib "eagle-import") (part "CAPC"))
    )
    (comp (ref "D12")
      (value "RX")
      (footprint "eagle-import:LED-1206")
      (libsource (lib "eagle-import") (part "LED1206"))
    )
    (comp (ref "D13")
      (value "TX")
      (footprint "eagle-import:LED-1206")
      (libsource (lib "eagle-import") (part "LED1206"))
    )
    (comp (ref "J10")
      (value "I2C/!SPI")
      (footprint "eagle-import:1X2")
      (libsource (lib "eagle-import") (part "M02ATH"))
    )
    (comp (ref "J35")
      (value "A0/A1")
      (footprint "eagle-import:2X3SM")
      (libsource (lib "eagle-import") (part "M03X2SM"))
    )
    (comp (ref "J36")
      (value "SDA")
      (footprint "eagle-import:1X03-SPECIAL")
      (libsource (lib "eagle-import") (part "M03SP"))
    )
    (comp (ref "J37")
      (value "I2C/SPI")
      (footprint "eagle-import:PHOENIX1725708-7")
      (libsource (lib "eagle-import") (part "M07PH"))
    )
    (comp (ref "J37A")
      (value "I2C/SPI DNP")
      (footprint "eagle-import:1X07-SPECIAL")
      (libsource (lib "eagle-import") (part "M07SP"))
    )
    (comp (ref "J38")
      (value "SCL/SCLK")
      (footprint "eagle-import:1X2")
      (libsource (lib "eagle-import") (part "M02ATH"))
    )
    (comp (ref "J41")
      (value "LpBk B")
      (footprint "eagle-import:2X2SM")
      (libsource (lib "eagle-import") (part "2X2SM"))
    )
    (comp (ref "R30")
      (value "20K")
      (footprint "eagle-import:R0603")
      (libsource (lib "eagle-import") (part "RESISTORR0603"))
    )
    (comp (ref "R36")
      (value "4.7K")
      (footprint "eagle-import:R0603")
      (libsource (lib "eagle-import") (part "RESISTORR0603"))
    )
    (comp (ref "R58")
      (value "1K")
      (footprint "eagle-import:R0603")
      (libsource (lib "eagle-import") (part "RESISTORR0603"))
    )
    (comp (ref "R63")
      (value "10K")
      (footprint "eagle-import:R0603")
      (libsource (lib "eagle-import") (part "RESISTORR0603"))
    )
    (comp (ref "R72")
      (value "10K")
      (footprint "eagle-import:R0603")
      (libsource (lib "eagle-import") (part "RESISTORR0603"))
    )
    (comp (ref "R73")
      (value "4.7K")
      (footprint "eagle-import:R0603")
      (libsource (lib "eagle-import") (part "RESISTORR0603"))
    )
    (comp (ref "R74")
      (value "4.7K")
      (footprint "eagle-import:R0603")
      (libsource (lib "eagle-import") (part "RESISTORR0603"))
    )
    (comp (ref "R82")
      (value "0 DNP")
      (footprint "eagle-import:R0603")
      (libsource (lib "eagle-import") (part "RESISTORR0603"))
    )
    (comp (ref "R89")
      (value "4.7K")
      (footprint "eagle-import:R0603")
      (libsource (lib "eagle-import") (part "RESISTORR0603"))
    )
    (comp (ref "R90")
      (value "470")
      (footprint "eagle-import:R0603")
      (libsource (lib "eagle-import") (part "RESISTORR0603"))
    )
    (comp (ref "U11")
      (value "SC16IS740IPW")
      (footprint "eagle-import:TSSOP16")
      (libsource (lib "eagle-import") (part "SC16IS740IPW"))
    )
    (comp (ref "U23")
      (value "SN74LVC2G126")
      (footprint "eagle-import:SM8-TI-A")
      (libsource (lib "eagle-import") (part "SN74LVC2G126-ALTA"))
    )
    (comp (ref "C28")
      (value "10uF 16V")
      (footprint "eagle-import:EIA3216")
      (libsource (lib "eagle-import") (part "CAP_POL1206"))
    )
    (comp (ref "C29")
      (value "0.1uF")
      (footprint "eagle-import:C0603K")
      (libsource (lib "eagle-import") (part "CAPC"))
    )
    (comp (ref "C47")
      (value "0.1uF")
      (footprint "eagle-import:C0603K")
      (libsource (lib "eagle-import") (part "CAPC"))
    )
    (comp (ref "D4")
      (value "DB2431200L")
      (footprint "eagle-import:SC-110A-POWER_DIODE")
      (libsource (lib "eagle-import") (part "DIODE-SCHOTTKY3"))
    )
    (comp (ref "D16")
      (value "HB")
      (footprint "eagle-import:LED-1206")
      (libsource (lib "eagle-import") (part "LED1206"))
    )
    (comp (ref "D17")
      (value "USER_LED")
      (footprint "eagle-import:LED-1206")
      (libsource (lib "eagle-import") (part "LED1206"))
    )
    (comp (ref "E2")
      (value "1")
      (footprint "eagle-import:MTHOLE4-40")
      (libsource (lib "eagle-import") (part "HOLE-MOUNT1"))
    )
    (comp (ref "E3")
      (value "1")
      (footprint "eagle-import:MTHOLE4-40")
      (libsource (lib "eagle-import") (part "HOLE-MOUNT1"))
    )
    (comp (ref "E4")
      (value "1")
      (footprint "eagle-import:MTHOLE4-40")
      (libsource (lib "eagle-import") (part "HOLE-MOUNT1"))
    )
    (comp (ref "E5")
      (value "1")
      (footprint "eagle-import:MTHOLE4-40")
      (libsource (lib "eagle-import") (part "HOLE-MOUNT1"))
    )
    (comp (ref "E6")
      (value "1")
      (footprint "eagle-import:MTHOLE4-40")
      (libsource (lib "eagle-import") (part "HOLE-MOUNT1"))
    )
    (comp (ref "E7")
      (value "1")
      (footprint "eagle-import:MTHOLE4-40")
      (libsource (lib "eagle-import") (part "HOLE-MOUNT1"))
    )
    (comp (ref "F2")
      (value "3.5A")
      (footprint "eagle-import:FUSE_OMNI-BLOCK-154")
      (libsource (lib "eagle-import") (part "FUSE_OMNI-BLOCK-154-SM"))
    )
    (comp (ref "J11")
      (value "+5V")
      (footprint "eagle-import:POWER_JACK_PTH")
      (libsource (lib "eagle-import") (part "POWER_JACKPTH"))
    )
    (comp (ref "J28")
      (value "Test Connector")
      (footprint "eagle-import:2X7SM")
      (libsource (lib "eagle-import") (part "M2X7SM"))
    )
    (comp (ref "J32")
      (value "HEADER A")
      (footprint "eagle-import:2X13-SM")
      (libsource (lib "eagle-import") (part "M2X13SM"))
    )
    (comp (ref "R76")
      (value "10K")
      (footprint "eagle-import:R0603")
      (libsource (lib "eagle-import") (part "RESISTORR0603"))
    )
    (comp (ref "R77")
      (value "10K")
      (footprint "eagle-import:R0603")
      (libsource (lib "eagle-import") (part "RESISTORR0603"))
    )
    (comp (ref "R78")
      (value "10K")
      (footprint "eagle-import:R0603")
      (libsource (lib "eagle-import") (part "RESISTORR0603"))
    )
    (comp (ref "R79")
      (value "10K")
      (footprint "eagle-import:R0603")
      (libsource (lib "eagle-import") (part "RESISTORR0603"))
    )
    (comp (ref "R80")
      (value "10K")
      (footprint "eagle-import:R0603")
      (libsource (lib "eagle-import") (part "RESISTORR0603"))
    )
    (comp (ref "R81")
      (value "10K")
      (footprint "eagle-import:R0603")
      (libsource (lib "eagle-import") (part "RESISTORR0603"))
    )
    (comp (ref "R93")
      (value "4.7K")
      (footprint "eagle-import:R0603")
      (libsource (lib "eagle-import") (part "RESISTORR0603"))
    )
    (comp (ref "R94")
      (value "4.7K")
      (footprint "eagle-import:R0603")
      (libsource (lib "eagle-import") (part "RESISTORR0603"))
    )
    (comp (ref "R98")
      (value "0")
      (footprint "eagle-import:R0603")
      (libsource (lib "eagle-import") (part "RESISTORR0603"))
    )
    (comp (ref "S1")
      (value "Power")
      (footprint "eagle-import:EVQ-PAC04M")
      (libsource (lib "eagle-import") (part "10-XXT"))
    )
    (comp (ref "S2")
      (value "Reset")
      (footprint "eagle-import:EVQ-PAC04M")
      (libsource (lib "eagle-import") (part "10-XXT"))
    )
    (comp (ref "S3")
      (value "Up")
      (footprint "eagle-import:EVQ-PAC04M")
      (libsource (lib "eagle-import") (part "10-XXT"))
    )
    (comp (ref "S4")
      (value "Down")
      (footprint "eagle-import:EVQ-PAC04M")
      (libsource (lib "eagle-import") (part "10-XXT"))
    )
    (comp (ref "S5")
      (value "Right")
      (footprint "eagle-import:EVQ-PAC04M")
      (libsource (lib "eagle-import") (part "10-XXT"))
    )
    (comp (ref "S6")
      (value "Left")
      (footprint "eagle-import:EVQ-PAC04M")
      (libsource (lib "eagle-import") (part "10-XXT"))
    )
    (comp (ref "S7")
      (value "Enter")
      (footprint "eagle-import:EVQ-PAC04M")
      (libsource (lib "eagle-import") (part "10-XXT"))
    )
    (comp (ref "U25")
      (value "SN74LVC2G126")
      (footprint "eagle-import:SM8-TI-A")
      (libsource (lib "eagle-import") (part "SN74LVC2G126-ALTA"))
    )
    (comp (ref "C4")
      (value "0.1uF")
      (footprint "eagle-import:C0603K")
      (libsource (lib "eagle-import") (part "CAPC"))
    )
    (comp (ref "C7")
      (value "0.1uF")
      (footprint "eagle-import:C0603K")
      (libsource (lib "eagle-import") (part "CAPC"))
    )
    (comp (ref "C8")
      (value "0.1uF")
      (footprint "eagle-import:C0603K")
      (libsource (lib "eagle-import") (part "CAPC"))
    )
    (comp (ref "C9")
      (value "0.1uF")
      (footprint "eagle-import:C0603K")
      (libsource (lib "eagle-import") (part "CAPC"))
    )
    (comp (ref "C10")
      (value "0.1uF")
      (footprint "eagle-import:C0603K")
      (libsource (lib "eagle-import") (part "CAPC"))
    )
    (comp (ref "C11")
      (value "0.1uF")
      (footprint "eagle-import:C0603K")
      (libsource (lib "eagle-import") (part "CAPC"))
    )
    (comp (ref "C37")
      (value "0.1uF")
      (footprint "eagle-import:C0603K")
      (libsource (lib "eagle-import") (part "CAPC"))
    )
    (comp (ref "J20")
      (value "EXT_UART")
      (footprint "eagle-import:PHOENIX1725685-5")
      (libsource (lib "eagle-import") (part "M05PH"))
    )
    (comp (ref "J20A")
      (value "EXT_UART")
      (footprint "eagle-import:1X05")
      (libsource (lib "eagle-import") (part "M051X5"))
    )
    (comp (ref "R29")
      (value "20K")
      (footprint "eagle-import:R0603")
      (libsource (lib "eagle-import") (part "RESISTORR0603"))
    )
    (comp (ref "R75")
      (value "20K")
      (footprint "eagle-import:R0603")
      (libsource (lib "eagle-import") (part "RESISTORR0603"))
    )
    (comp (ref "U1")
      (value "74HC237")
      (footprint "eagle-import:TSSOP16")
      (libsource (lib "eagle-import") (part "74HC237"))
    )
    (comp (ref "U4")
      (value "SN74LVC2G126")
      (footprint "eagle-import:SM8-TI-A")
      (libsource (lib "eagle-import") (part "SN74LVC2G126A"))
    )
    (comp (ref "U6")
      (value "SN74LVC2G126A")
      (footprint "eagle-import:SM8-TI-A")
      (libsource (lib "eagle-import") (part "SN74LVC2G126A"))
    )
    (comp (ref "U7")
      (value "SN74LVC2G126A")
      (footprint "eagle-import:SM8-TI-A")
      (libsource (lib "eagle-import") (part "SN74LVC2G126A"))
    )
    (comp (ref "U8")
      (value "SN74LVC2G126A")
      (footprint "eagle-import:SM8-TI-A")
      (libsource (lib "eagle-import") (part "SN74LVC2G126A"))
    )
    (comp (ref "U9")
      (value "SN74LVC2G126A")
      (footprint "eagle-import:SM8-TI-A")
      (libsource (lib "eagle-import") (part "SN74LVC2G126A"))
    )
    (comp (ref "U10")
      (value "SN74LVC2G126A")
      (footprint "eagle-import:SM8-TI-A")
      (libsource (lib "eagle-import") (part "SN74LVC2G126A"))
    )
    (comp (ref "C5")
      (value "4.7uF 10V")
      (footprint "eagle-import:C0603K")
      (libsource (lib "eagle-import") (part "CAPC"))
    )
    (comp (ref "C6")
      (value "1uF 35V")
      (footprint "eagle-import:C0603K")
      (libsource (lib "eagle-import") (part "CAPC"))
    )
    (comp (ref "C13")
      (value "0.1uF")
      (footprint "eagle-import:C0603K")
      (libsource (lib "eagle-import") (part "CAPC"))
    )
    (comp (ref "C14")
      (value "4.7nF")
      (footprint "eagle-import:C0603K")
      (libsource (lib "eagle-import") (part "CAPC"))
    )
    (comp (ref "C20")
      (value "0.01uF")
      (footprint "eagle-import:C0603K")
      (libsource (lib "eagle-import") (part "CAPC"))
    )
    (comp (ref "C33")
      (value "0.1uF")
      (footprint "eagle-import:C0603K")
      (libsource (lib "eagle-import") (part "CAPC"))
    )
    (comp (ref "C34")
      (value "0.1uF")
      (footprint "eagle-import:C0603K")
      (libsource (lib "eagle-import") (part "CAPC"))
    )
    (comp (ref "D5")
      (value "CMSH1-40")
      (footprint "eagle-import:SMB-DIODE")
      (libsource (lib "eagle-import") (part "DIODE-SCHOTTKY1"))
    )
    (comp (ref "FB2")
      (value "BLM18KG601SN1D")
      (footprint "eagle-import:0603")
      (libsource (lib "eagle-import") (part "FERRITEBEAD"))
    )
    (comp (ref "J25")
      (value "DSBL LCD")
      (footprint "eagle-import:1X2SM")
      (libsource (lib "eagle-import") (part "M02ASM"))
    )
    (comp (ref "J31")
      (value "LCD_Test")
      (footprint "eagle-import:1X03-SPECIAL")
      (libsource (lib "eagle-import") (part "M03SP"))
    )
    (comp (ref "J34")
      (value "CAN")
      (footprint "eagle-import:PHOENIX1725669-3")
      (libsource (lib "eagle-import") (part "M03PH"))
    )
    (comp (ref "J34A")
      (value "CAN DNP")
      (footprint "eagle-import:1X03-SPECIAL")
      (libsource (lib "eagle-import") (part "M03SP"))
    )
    (comp (ref "L1")
      (value "CLF6045T-220M-D")
      (footprint "eagle-import:TDK_CA")
      (libsource (lib "eagle-import") (part "TDK-CA_INDUCT"))
    )
    (comp (ref "MD2")
      (value "NHD-7.0-800480EF")
      (footprint "eagle-import:NEWHAVEN_LCD_NHD-7.0-800480EF")
      (libsource (lib "eagle-import") (part "NEWHAVEN_LCD_NHD-7.0-800480EF"))
    )
    (comp (ref "R26")
      (value "3.74")
      (footprint "eagle-import:R0603")
      (libsource (lib "eagle-import") (part "RESISTORR0603"))
    )
    (comp (ref "R27")
      (value "3.74")
      (footprint "eagle-import:R0603")
      (libsource (lib "eagle-import") (part "RESISTORR0603"))
    )
    (comp (ref "R28")
      (value "1K")
      (footprint "eagle-import:R0603")
      (libsource (lib "eagle-import") (part "RESISTORR0603"))
    )
    (comp (ref "R43")
      (value "4.7K DNP")
      (footprint "eagle-import:R0603")
      (libsource (lib "eagle-import") (part "RESISTORR0603"))
    )
    (comp (ref "R44")
      (value "4.7K DNP")
      (footprint "eagle-import:R0603")
      (libsource (lib "eagle-import") (part "RESISTORR0603"))
    )
    (comp (ref "R45")
      (value "4.7K")
      (footprint "eagle-import:R0603")
      (libsource (lib "eagle-import") (part "RESISTORR0603"))
    )
    (comp (ref "R46")
      (value "4.7K")
      (footprint "eagle-import:R0603")
      (libsource (lib "eagle-import") (part "RESISTORR0603"))
    )
    (comp (ref "R47")
      (value "60")
      (footprint "eagle-import:R0603")
      (libsource (lib "eagle-import") (part "RESISTORR0603"))
    )
    (comp (ref "R48")
      (value "60")
      (footprint "eagle-import:R0603")
      (libsource (lib "eagle-import") (part "RESISTORR0603"))
    )
    (comp (ref "R49")
      (value "0")
      (footprint "eagle-import:R0603")
      (libsource (lib "eagle-import") (part "RESISTORR0603"))
    )
    (comp (ref "R51")
      (value "0 DNP")
      (footprint "eagle-import:R0603")
      (libsource (lib "eagle-import") (part "RESISTORR0603"))
    )
    (comp (ref "R52")
      (value "0 DNP")
      (footprint "eagle-import:R0603")
      (libsource (lib "eagle-import") (part "RESISTORR0603"))
    )
    (comp (ref "R67")
      (value "0")
      (footprint "eagle-import:R0603")
      (libsource (lib "eagle-import") (part "RESISTORR0603"))
    )
    (comp (ref "R68")
      (value "10K")
      (footprint "eagle-import:R0603")
      (libsource (lib "eagle-import") (part "RESISTORR0603"))
    )
    (comp (ref "R69")
      (value "0 DNP")
      (footprint "eagle-import:R0603")
      (libsource (lib "eagle-import") (part "RESISTORR0603"))
    )
    (comp (ref "R84")
      (value "0")
      (footprint "eagle-import:0805-RES")
      (libsource (lib "eagle-import") (part "RESISTOR0805"))
    )
    (comp (ref "R95")
      (value "0")
      (footprint "eagle-import:0805-RES")
      (libsource (lib "eagle-import") (part "RESISTOR0805"))
    )
    (comp (ref "R96")
      (value "0")
      (footprint "eagle-import:0805-RES")
      (libsource (lib "eagle-import") (part "RESISTOR0805"))
    )
    (comp (ref "R97")
      (value "0")
      (footprint "eagle-import:0805-RES")
      (libsource (lib "eagle-import") (part "RESISTOR0805"))
    )
    (comp (ref "U2")
      (value "CAT4139T")
      (footprint "eagle-import:TSOT-23-5")
      (libsource (lib "eagle-import") (part "CAT4139T"))
    )
    (comp (ref "U3")
      (value "NCV7342")
      (footprint "eagle-import:SOIC08")
      (libsource (lib "eagle-import") (part "NCV7342"))
    )
    (comp (ref "U12")
      (value "CAT24C256WI-GT3")
      (footprint "eagle-import:SO08")
      (libsource (lib "eagle-import") (part "EEPROM-I2CSMD"))
    )
    (comp (ref "C22")
      (value "DNP")
      (footprint "eagle-import:C0603K")
      (libsource (lib "eagle-import") (part "CAPC"))
    )
    (comp (ref "C23")
      (value "DNP")
      (footprint "eagle-import:C0603K")
      (libsource (lib "eagle-import") (part "CAPC"))
    )
    (comp (ref "C42")
      (value "100nF")
      (footprint "eagle-import:C0603K")
      (libsource (lib "eagle-import") (part "CAPC"))
    )
    (comp (ref "C46")
      (value "0.1uF")
      (footprint "eagle-import:C0603K")
      (libsource (lib "eagle-import") (part "CAPC"))
    )
    (comp (ref "D14")
      (value "RX")
      (footprint "eagle-import:LED-1206")
      (libsource (lib "eagle-import") (part "LED1206"))
    )
    (comp (ref "D15")
      (value "TX")
      (footprint "eagle-import:LED-1206")
      (libsource (lib "eagle-import") (part "LED1206"))
    )
    (comp (ref "J21")
      (value "KNX DNP")
      (footprint "eagle-import:1X09-SPECIAL")
      (libsource (lib "eagle-import") (part "M09SPECIAL"))
    )
    (comp (ref "J22")
      (value "KNX3V3")
      (footprint "eagle-import:1X03-SPECIAL")
      (libsource (lib "eagle-import") (part "M03SP"))
    )
    (comp (ref "J23")
      (value "KNX")
      (footprint "eagle-import:1X03-SPECIAL")
      (libsource (lib "eagle-import") (part "M03SP"))
    )
    (comp (ref "J24")
      (value "KNXGND")
      (footprint "eagle-import:1X03-SPECIAL")
      (libsource (lib "eagle-import") (part "M03SP"))
    )
    (comp (ref "MD6")
      (value "KNX-2")
      (footprint "eagle-import:KNX-1")
      (libsource (lib "eagle-import") (part "KNX-2"))
    )
    (comp (ref "R31")
      (value "4.7K DNP")
      (footprint "eagle-import:R0603")
      (libsource (lib "eagle-import") (part "RESISTORR0603"))
    )
    (comp (ref "R37")
      (value "0 DNP")
      (footprint "eagle-import:R0603")
      (libsource (lib "eagle-import") (part "RESISTORR0603"))
    )
    (comp (ref "R38")
      (value "6.04K 1%")
      (footprint "eagle-import:R0603")
      (libsource (lib "eagle-import") (part "RESISTORR0603"))
    )
    (comp (ref "R39")
      (value "3.01K 1%")
      (footprint "eagle-import:R0603")
      (libsource (lib "eagle-import") (part "RESISTORR0603"))
    )
    (comp (ref "R40")
      (value "0")
      (footprint "eagle-import:R0603")
      (libsource (lib "eagle-import") (part "RESISTORR0603"))
    )
    (comp (ref "R41")
      (value "6.04K 1%")
      (footprint "eagle-import:R0603")
      (libsource (lib "eagle-import") (part "RESISTORR0603"))
    )
    (comp (ref "R42")
      (value "3.01K 1%")
      (footprint "eagle-import:R0603")
      (libsource (lib "eagle-import") (part "RESISTORR0603"))
    )
    (comp (ref "R91")
      (value "4.7K")
      (footprint "eagle-import:R0603")
      (libsource (lib "eagle-import") (part "RESISTORR0603"))
    )
    (comp (ref "R92")
      (value "470")
      (footprint "eagle-import:R0603")
      (libsource (lib "eagle-import") (part "RESISTORR0603"))
    )
    (comp (ref "U13")
      (value "SN74LVC2G126")
      (footprint "eagle-import:SM8-TI-A")
      (libsource (lib "eagle-import") (part "SN74LVC2G126-ALTA"))
    )
    (comp (ref "U24")
      (value "SN74LVC2G126")
      (footprint "eagle-import:SM8-TI-A")
      (libsource (lib "eagle-import") (part "SN74LVC2G126-ALTA"))
    )
    (comp (ref "C1")
      (value "47pF")
      (footprint "eagle-import:C0603K")
      (libsource (lib "eagle-import") (part "CAPC"))
    )
    (comp (ref "C2")
      (value "47pF")
      (footprint "eagle-import:C0603K")
      (libsource (lib "eagle-import") (part "CAPC"))
    )
    (comp (ref "C3")
      (value "10nF")
      (footprint "eagle-import:C0603K")
      (libsource (lib "eagle-import") (part "CAPC"))
    )
    (comp (ref "C15")
      (value "100nF")
      (footprint "eagle-import:C0603K")
      (libsource (lib "eagle-import") (part "CAPC"))
    )
    (comp (ref "C16")
      (value "8.2pF")
      (footprint "eagle-import:C0603K")
      (libsource (lib "eagle-import") (part "CAPC"))
    )
    (comp (ref "C17")
      (value "1uF")
      (footprint "eagle-import:C0603K")
      (libsource (lib "eagle-import") (part "CAPC"))
    )
    (comp (ref "C30")
      (value "4.7uF")
      (footprint "eagle-import:C0603K")
      (libsource (lib "eagle-import") (part "CAPC"))
    )
    (comp (ref "C31")
      (value "0.1uF")
      (footprint "eagle-import:C0603K")
      (libsource (lib "eagle-import") (part "CAPC"))
    )
    (comp (ref "C43")
      (value "0.1uF")
      (footprint "eagle-import:C0603K")
      (libsource (lib "eagle-import") (part "CAPC"))
    )
    (comp (ref "D1")
      (value "TX")
      (footprint "eagle-import:LED-1206")
      (libsource (lib "eagle-import") (part "LED1206"))
    )
    (comp (ref "D2")
      (value "RX")
      (footprint "eagle-import:LED-1206")
      (libsource (lib "eagle-import") (part "LED1206"))
    )
    (comp (ref "D3")
      (value "GN")
      (footprint "eagle-import:LED-1206")
      (libsource (lib "eagle-import") (part "LED1206"))
    )
    (comp (ref "D8")
      (value "RX")
      (footprint "eagle-import:LED-1206")
      (libsource (lib "eagle-import") (part "LED1206"))
    )
    (comp (ref "D9")
      (value "TX")
      (footprint "eagle-import:LED-1206")
      (libsource (lib "eagle-import") (part "LED1206"))
    )
    (comp (ref "FB1")
      (value "BLM18KG601SN1D")
      (footprint "eagle-import:0603")
      (libsource (lib "eagle-import") (part "FERRITEBEAD"))
    )
    (comp (ref "J12")
      (value "USBMINI")
      (footprint "eagle-import:USBMINI-TH")
      (libsource (lib "eagle-import") (part "USBMINI-32007-400TH"))
    )
    (comp (ref "J15")
      (value "XBeeCtrl")
      (footprint "eagle-import:2X3")
      (libsource (lib "eagle-import") (part "M03X2NL"))
    )
    (comp (ref "J16")
      (value "M03X2SM")
      (footprint "eagle-import:2X3SM")
      (libsource (lib "eagle-import") (part "M03X2SM"))
    )
    (comp (ref "J19")
      (value "UART/XBee")
      (footprint "eagle-import:2X2SM")
      (libsource (lib "eagle-import") (part "2X2SM"))
    )
    (comp (ref "J27")
      (value "XBee DNP")
      (footprint "eagle-import:1X07-SPECIAL")
      (libsource (lib "eagle-import") (part "M07SP"))
    )
    (comp (ref "MD3")
      (value "XBEE-2A")
      (footprint "eagle-import:XBEE-2")
      (libsource (lib "eagle-import") (part "XBEE-2A"))
    )
    (comp (ref "R21")
      (value "27")
      (footprint "eagle-import:R0603")
      (libsource (lib "eagle-import") (part "RESISTORR0603"))
    )
    (comp (ref "R22")
      (value "27")
      (footprint "eagle-import:R0603")
      (libsource (lib "eagle-import") (part "RESISTORR0603"))
    )
    (comp (ref "R23")
      (value "4.7K")
      (footprint "eagle-import:R0603")
      (libsource (lib "eagle-import") (part "RESISTORR0603"))
    )
    (comp (ref "R24")
      (value "470")
      (footprint "eagle-import:R0603")
      (libsource (lib "eagle-import") (part "RESISTORR0603"))
    )
    (comp (ref "R50")
      (value "20K")
      (footprint "eagle-import:R0603")
      (libsource (lib "eagle-import") (part "RESISTORR0603"))
    )
    (comp (ref "R53")
      (value "0 DNP")
      (footprint "eagle-import:R0603")
      (libsource (lib "eagle-import") (part "RESISTORR0603"))
    )
    (comp (ref "R55")
      (value "470")
      (footprint "eagle-import:R0603")
      (libsource (lib "eagle-import") (part "RESISTORR0603"))
    )
    (comp (ref "R62")
      (value "10K DNP")
      (footprint "eagle-import:R0603")
      (libsource (lib "eagle-import") (part "RESISTORR0603"))
    )
    (comp (ref "R85")
      (value "4.7K")
      (footprint "eagle-import:R0603")
      (libsource (lib "eagle-import") (part "RESISTORR0603"))
    )
    (comp (ref "R86")
      (value "470")
      (footprint "eagle-import:R0603")
      (libsource (lib "eagle-import") (part "RESISTORR0603"))
    )
    (comp (ref "U5")
      (value "FT231XS")
      (footprint "eagle-import:SSOP20-.150")
      (libsource (lib "eagle-import") (part "FT231XX"))
    )
    (comp (ref "U21")
      (value "SN74LVC2G126")
      (footprint "eagle-import:SM8-TI-A")
      (libsource (lib "eagle-import") (part "SN74LVC2G126-ALTA"))
    )
  )
  (nets
    (net (code "1") (name "+5V") (class "Default")
      (node (ref "F2") (pin "1") (pinfunction "1_1") (pintype "bidirectional"))
      (node (ref "J11") (pin "1") (pinfunction "PWR_1") (pintype "bidirectional"))
    )
    (net (code "2") (name "A0{slash}CS") (class "Default")
      (node (ref "J28") (pin "1") (pinfunction "1_1") (pintype "passive"))
      (node (ref "J35") (pin "3") (pinfunction "3_3") (pintype "passive"))
      (node (ref "J37") (pin "5") (pinfunction "5_5") (pintype "passive"))
      (node (ref "J37A") (pin "5") (pinfunction "5_5") (pintype "passive"))
      (node (ref "U11") (pin "2") (pinfunction "A0/CS_2") (pintype "bidirectional"))
    )
    (net (code "3") (name "A1{slash}SI") (class "Default")
      (node (ref "J28") (pin "3") (pinfunction "3_3") (pintype "passive"))
      (node (ref "J35") (pin "4") (pinfunction "4_4") (pintype "passive"))
      (node (ref "J37") (pin "6") (pinfunction "6_6") (pintype "passive"))
      (node (ref "J37A") (pin "6") (pinfunction "6_6") (pintype "passive"))
      (node (ref "U11") (pin "3") (pinfunction "A1/SI_3") (pintype "bidirectional"))
    )
    (net (code "4") (name "AIN0") (class "Default")
      (node (ref "MD1") (pin "~39") (pinfunction "39_~39") (pintype "bidirectional"))
      (node (ref "U14") (pin "7") (pinfunction "D4_7") (pintype "bidirectional"))
    )
    (net (code "5") (name "AIN1") (class "Default")
      (node (ref "MD1") (pin "~40") (pinfunction "40_~40") (pintype "bidirectional"))
      (node (ref "U15") (pin "10") (pinfunction "D3_10") (pintype "bidirectional"))
    )
    (net (code "6") (name "AIN2") (class "Default")
      (node (ref "MD1") (pin "~37") (pinfunction "37_~37") (pintype "bidirectional"))
      (node (ref "U14") (pin "10") (pinfunction "D3_10") (pintype "bidirectional"))
    )
    (net (code "7") (name "AIN3") (class "Default")
      (node (ref "MD1") (pin "~38") (pinfunction "38_~38") (pintype "bidirectional"))
      (node (ref "U15") (pin "15") (pinfunction "D2_15") (pintype "bidirectional"))
    )
    (net (code "8") (name "AIN4") (class "Default")
      (node (ref "MD1") (pin "~33") (pinfunction "33_~33") (pintype "bidirectional"))
      (node (ref "U14") (pin "2") (pinfunction "D1_2") (pintype "bidirectional"))
    )
    (net (code "9") (name "AIN4_SW") (class "Default")
      (node (ref "J32") (pin "7") (pinfunction "7_7") (pintype "passive"))
      (node (ref "U14") (pin "3") (pinfunction "S1_3") (pintype "bidirectional"))
    )
    (net (code "10") (name "AIN5") (class "Default")
      (node (ref "MD1") (pin "~36") (pinfunction "36_~36") (pintype "bidirectional"))
      (node (ref "U15") (pin "2") (pinfunction "D1_2") (pintype "bidirectional"))
    )
    (net (code "11") (name "AIN5_SW") (class "Default")
      (node (ref "J32") (pin "9") (pinfunction "9_9") (pintype "passive"))
      (node (ref "U15") (pin "3") (pinfunction "S1_3") (pintype "bidirectional"))
    )
    (net (code "12") (name "AIN6") (class "Default")
      (node (ref "MD1") (pin "~35") (pinfunction "35_~35") (pintype "bidirectional"))
      (node (ref "U14") (pin "15") (pinfunction "D2_15") (pintype "bidirectional"))
    )
    (net (code "13") (name "BBB_I-SENSE") (class "Default")
      (node (ref "C26") (pin "1") (pinfunction "+_1") (pintype "passive"))
      (node (ref "R70") (pin "2") (pinfunction "2_2") (pintype "passive"))
      (node (ref "U15") (pin "14") (pinfunction "S2_14") (pintype "bidirectional"))
    )
    (net (code "14") (name "BRIDGE_CLK") (class "Default")
      (node (ref "C12") (pin "1") (pinfunction "+_1") (pintype "passive"))
      (node (ref "R34") (pin "2") (pinfunction "2_2") (pintype "passive"))
      (node (ref "U11") (pin "15") (pinfunction "XTAL1_15") (pintype "bidirectional"))
    )
    (net (code "15") (name "BRIDGE_RX") (class "Default")
      (node (ref "R30") (pin "2") (pinfunction "2_2") (pintype "passive"))
      (node (ref "U11") (pin "13") (pinfunction "RX_13") (pintype "bidirectional"))
      (node (ref "U23") (pin "2") (pinfunction "1A_2") (pintype "input"))
      (node (ref "U7") (pin "3") (pinfunction "2Y_3") (pintype "output"))
    )
    (net (code "16") (name "BRIDGE_SEL") (class "Default")
      (node (ref "U1") (pin "12") (pinfunction "Y3_12") (pintype "bidirectional"))
      (node (ref "U23") (pin "1") (pinfunction "1OE_1") (pintype "input"))
      (node (ref "U23") (pin "7") (pinfunction "2OE_7") (pintype "input"))
      (node (ref "U7") (pin "1") (pinfunction "1OE_1") (pintype "input"))
      (node (ref "U7") (pin "7") (pinfunction "2OE_7") (pintype "input"))
    )
    (net (code "17") (name "BRIDGE_TX") (class "Default")
      (node (ref "U11") (pin "12") (pinfunction "TX_12") (pintype "bidirectional"))
      (node (ref "U23") (pin "5") (pinfunction "2A_5") (pintype "input"))
      (node (ref "U7") (pin "2") (pinfunction "1A_2") (pintype "input"))
    )
    (net (code "18") (name "CANH") (class "Default")
      (node (ref "J34") (pin "1") (pinfunction "1_1") (pintype "passive"))
      (node (ref "J34A") (pin "1") (pinfunction "1_1") (pintype "passive"))
      (node (ref "R47") (pin "2") (pinfunction "2_2") (pintype "passive"))
      (node (ref "U3") (pin "7") (pinfunction "CANH_7") (pintype "bidirectional"))
    )
    (net (code "19") (name "CANL") (class "Default")
      (node (ref "J34") (pin "2") (pinfunction "2_2") (pintype "passive"))
      (node (ref "J34A") (pin "2") (pinfunction "2_2") (pintype "passive"))
      (node (ref "R48") (pin "2") (pinfunction "2_2") (pintype "passive"))
      (node (ref "U3") (pin "6") (pinfunction "CANL_6") (pintype "bidirectional"))
    )
    (net (code "20") (name "DCAN1_RX") (class "Default")
      (node (ref "MD1") (pin "~24") (pinfunction "24_~24") (pintype "bidirectional"))
      (node (ref "R52") (pin "2") (pinfunction "2_2") (pintype "passive"))
      (node (ref "U3") (pin "4") (pinfunction "RXD_4") (pintype "bidirectional"))
    )
    (net (code "21") (name "DCAN1_TX") (class "Default")
      (node (ref "MD1") (pin "~26") (pinfunction "26_~26") (pintype "bidirectional"))
      (node (ref "U3") (pin "1") (pinfunction "TXD_1") (pintype "bidirectional"))
    )
    (net (code "22") (name "DOWN_BUT") (class "Default")
      (node (ref "MD1") (pin "~27") (pinfunction "27_~27") (pintype "bidirectional"))
      (node (ref "R78") (pin "1") (pinfunction "1_1") (pintype "passive"))
      (node (ref "S4") (pin "1") (pinfunction "S_1") (pintype "passive"))
      (node (ref "S4") (pin "2") (pinfunction "S1_2") (pintype "passive"))
    )
    (net (code "23") (name "EEPROM-WP") (class "Default")
      (node (ref "J28") (pin "13") (pinfunction "13_13") (pintype "passive"))
      (node (ref "R46") (pin "2") (pinfunction "2_2") (pintype "passive"))
      (node (ref "U12") (pin "7") (pinfunction "WP_7") (pintype "bidirectional"))
    )
    (net (code "24") (name "ENTER_BUT") (class "Default")
      (node (ref "MD1") (pin "18") (pinfunction "18_18") (pintype "bidirectional"))
      (node (ref "R81") (pin "1") (pinfunction "1_1") (pintype "passive"))
      (node (ref "S7") (pin "1") (pinfunction "S_1") (pintype "passive"))
      (node (ref "S7") (pin "2") (pinfunction "S1_2") (pintype "passive"))
    )
    (net (code "25") (name "EXT_UART_RX") (class "Default")
      (node (ref "J20") (pin "4") (pinfunction "4_4") (pintype "passive"))
      (node (ref "J20A") (pin "4") (pinfunction "4_4") (pintype "passive"))
      (node (ref "J28") (pin "11") (pinfunction "11_11") (pintype "passive"))
      (node (ref "R29") (pin "2") (pinfunction "2_2") (pintype "passive"))
      (node (ref "U6") (pin "2") (pinfunction "1A_2") (pintype "input"))
    )
    (net (code "26") (name "EXT_UART_TX") (class "Default")
      (node (ref "J20") (pin "5") (pinfunction "5_5") (pintype "passive"))
      (node (ref "J20A") (pin "5") (pinfunction "5_5") (pintype "passive"))
      (node (ref "J28") (pin "9") (pinfunction "9_9") (pintype "passive"))
      (node (ref "U6") (pin "3") (pinfunction "2Y_3") (pintype "output"))
    )
    (net (code "27") (name "GND") (class "Default")
      (node (ref "C1") (pin "2") (pinfunction "-_2") (pintype "passive"))
      (node (ref "C10") (pin "1") (pinfunction "+_1") (pintype "passive"))
      (node (ref "C11") (pin "1") (pinfunction "+_1") (pintype "passive"))
      (node (ref "C12") (pin "2") (pinfunction "-_2") (pintype "passive"))
      (node (ref "C13") (pin "2") (pinfunction "-_2") (pintype "passive"))
      (node (ref "C14") (pin "2") (pinfunction "-_2") (pintype "passive"))
      (node (ref "C15") (pin "2") (pinfunction "-_2") (pintype "passive"))
      (node (ref "C16") (pin "2") (pinfunction "-_2") (pintype "passive"))
      (node (ref "C17") (pin "2") (pinfunction "-_2") (pintype "passive"))
      (node (ref "C18") (pin "2") (pinfunction "-_2") (pintype "passive"))
      (node (ref "C19") (pin "2") (pinfunction "-_2") (pintype "passive"))
      (node (ref "C2") (pin "2") (pinfunction "-_2") (pintype "passive"))
      (node (ref "C20") (pin "2") (pinfunction "-_2") (pintype "passive"))
      (node (ref "C22") (pin "2") (pinfunction "-_2") (pintype "passive"))
      (node (ref "C23") (pin "2") (pinfunction "-_2") (pintype "passive"))
      (node (ref "C24") (pin "1") (pinfunction "+_1") (pintype "passive"))
      (node (ref "C25") (pin "1") (pinfunction "+_1") (pintype "passive"))
      (node (ref "C26") (pin "2") (pinfunction "-_2") (pintype "passive"))
      (node (ref "C27") (pin "2") (pinfunction "-_2") (pintype "passive"))
      (node (ref "C28") (pin "C") (pinfunction "-_C") (pintype "passive"))
      (node (ref "C29") (pin "2") (pinfunction "-_2") (pintype "passive"))
      (node (ref "C3") (pin "2") (pinfunction "-_2") (pintype "passive"))
      (node (ref "C30") (pin "2") (pinfunction "-_2") (pintype "passive"))
      (node (ref "C31") (pin "2") (pinfunction "-_2") (pintype "passive"))
      (node (ref "C32") (pin "2") (pinfunction "-_2") (pintype "passive"))
      (node (ref "C33") (pin "2") (pinfunction "-_2") (pintype "passive"))
      (node (ref "C34") (pin "2") (pinfunction "-_2") (pintype "passive"))
      (node (ref "C35") (pin "2") (pinfunction "-_2") (pintype "passive"))
      (node (ref "C36") (pin "2") (pinfunction "-_2") (pintype "passive"))
      (node (ref "C37") (pin "2") (pinfunction "-_2") (pintype "passive"))
      (node (ref "C39") (pin "2") (pinfunction "-_2") (pintype "passive"))
      (node (ref "C4") (pin "1") (pinfunction "+_1") (pintype "passive"))
      (node (ref "C40") (pin "2") (pinfunction "-_2") (pintype "passive"))
      (node (ref "C41") (pin "2") (pinfunction "-_2") (pintype "passive"))
      (node (ref "C42") (pin "2") (pinfunction "-_2") (pintype "passive"))
      (node (ref "C43") (pin "1") (pinfunction "+_1") (pintype "passive"))
      (node (ref "C44") (pin "1") (pinfunction "+_1") (pintype "passive"))
      (node (ref "C45") (pin "1") (pinfunction "+_1") (pintype "passive"))
      (node (ref "C46") (pin "1") (pinfunction "+_1") (pintype "passive"))
      (node (ref "C47") (pin "1") (pinfunction "+_1") (pintype "passive"))
      (node (ref "C48") (pin "2") (pinfunction "-_2") (pintype "passive"))
      (node (ref "C49") (pin "2") (pinfunction "-_2") (pintype "passive"))
      (node (ref "C5") (pin "2") (pinfunction "-_2") (pintype "passive"))
      (node (ref "C6") (pin "2") (pinfunction "-_2") (pintype "passive"))
      (node (ref "C7") (pin "1") (pinfunction "+_1") (pintype "passive"))
      (node (ref "C8") (pin "1") (pinfunction "+_1") (pintype "passive"))
      (node (ref "C9") (pin "1") (pinfunction "+_1") (pintype "passive"))
      (node (ref "D4") (pin "A") (pinfunction "A_A") (pintype "passive"))
      (node (ref "D6") (pin "C") (pinfunction "C_C") (pintype "passive"))
      (node (ref "E2") (pin "1") (pinfunction "1_1") (pintype "bidirectional"))
      (node (ref "E3") (pin "1") (pinfunction "1_1") (pintype "bidirectional"))
      (node (ref "E4") (pin "1") (pinfunction "1_1") (pintype "bidirectional"))
      (node (ref "E5") (pin "1") (pinfunction "1_1") (pintype "bidirectional"))
      (node (ref "E6") (pin "1") (pinfunction "1_1") (pintype "bidirectional"))
      (node (ref "E7") (pin "1") (pinfunction "1_1") (pintype "bidirectional"))
      (node (ref "J11") (pin "2") (pinfunction "GND_2") (pintype "bidirectional"))
      (node (ref "J11") (pin "3") (pinfunction "GNDBREAK_3") (pintype "bidirectional"))
      (node (ref "J12") (pin "5") (pinfunction "5_5") (pintype "passive"))
      (node (ref "J12") (pin "6") (pinfunction "S1_6") (pintype "passive"))
      (node (ref "J12") (pin "7") (pinfunction "S2_7") (pintype "passive"))
      (node (ref "J12") (pin "8") (pinfunction "S3_8") (pintype "passive"))
      (node (ref "J12") (pin "9") (pinfunction "S4_9") (pintype "passive"))
      (node (ref "J20") (pin "1") (pinfunction "1_1") (pintype "passive"))
      (node (ref "J20A") (pin "1") (pinfunction "1_1") (pintype "passive"))
      (node (ref "J21") (pin "9") (pinfunction "9_9") (pintype "passive"))
      (node (ref "J24") (pin "1") (pinfunction "1_1") (pintype "passive"))
      (node (ref "J24") (pin "2") (pinfunction "2_2") (pintype "passive"))
      (node (ref "J24") (pin "3") (pinfunction "3_3") (pintype "passive"))
      (node (ref "J25") (pin "1") (pinfunction "1_1") (pintype "passive"))
      (node (ref "J27") (pin "7") (pinfunction "7_7") (pintype "passive"))
      (node (ref "J28") (pin "14") (pinfunction "14_14") (pintype "passive"))
      (node (ref "J29") (pin "7") (pinfunction "7_7") (pintype "passive"))
      (node (ref "J30") (pin "9") (pinfunction "9_9") (pintype "passive"))
      (node (ref "J32") (pin "1") (pinfunction "1_1") (pintype "passive"))
      (node (ref "J32") (pin "13") (pinfunction "13_13") (pintype "passive"))
      (node (ref "J32") (pin "15") (pinfunction "15_15") (pintype "passive"))
      (node (ref "J32") (pin "25") (pinfunction "25_25") (pintype "passive"))
      (node (ref "J34") (pin "3") (pinfunction "3_3") (pintype "passive"))
      (node (ref "J34A") (pin "3") (pinfunction "3_3") (pintype "passive"))
      (node (ref "J35") (pin "5") (pinfunction "5_5") (pintype "passive"))
      (node (ref "J35") (pin "6") (pinfunction "6_6") (pintype "passive"))
      (node (ref "J36") (pin "3") (pinfunction "3_3") (pintype "passive"))
      (node (ref "J37") (pin "7") (pinfunction "7_7") (pintype "passive"))
      (node (ref "J37A") (pin "7") (pinfunction "7_7") (pintype "passive"))
      (node (ref "MD1") (pin "1") (pinfunction "1_1") (pintype "bidirectional"))
      (node (ref "MD1") (pin "2") (pinfunction "2_2") (pintype "bidirectional"))
      (node (ref "MD1") (pin "`1") (pinfunction "1_`1") (pintype "bidirectional"))
      (node (ref "MD1") (pin "~1") (pinfunction "1_~1") (pintype "bidirectional"))
      (node (ref "MD1") (pin "~2") (pinfunction "2_~2") (pintype "bidirectional"))
      (node (ref "MD1") (pin "~34") (pinfunction "34_~34") (pintype "bidirectional"))
      (node (ref "MD1") (pin "~43") (pinfunction "43_~43") (pintype "bidirectional"))
      (node (ref "MD1") (pin "~44") (pinfunction "44_~44") (pintype "bidirectional"))
      (node (ref "MD1") (pin "~45") (pinfunction "45_~45") (pintype "bidirectional"))
      (node (ref "MD1") (pin "~46") (pinfunction "46_~46") (pintype "bidirectional"))
      (node (ref "MD2") (pin "13") (pinfunction "13_13") (pintype "passive"))
      (node (ref "MD2") (pin "14") (pinfunction "14_14") (pintype "passive"))
      (node (ref "MD2") (pin "21") (pinfunction "21_21") (pintype "passive"))
      (node (ref "MD2") (pin "22") (pinfunction "22_22") (pintype "passive"))
      (node (ref "MD2") (pin "23") (pinfunction "23_23") (pintype "passive"))
      (node (ref "MD2") (pin "29") (pinfunction "29_29") (pintype "passive"))
      (node (ref "MD2") (pin "3") (pinfunction "3_3") (pintype "passive"))
      (node (ref "MD2") (pin "36") (pinfunction "36_36") (pintype "passive"))
      (node (ref "MD2") (pin "41") (pinfunction "41_41") (pintype "passive"))
      (node (ref "MD2") (pin "42") (pinfunction "42_42") (pintype "passive"))
      (node (ref "MD2") (pin "5") (pinfunction "5_5") (pintype "passive"))
      (node (ref "MD2") (pin "6") (pinfunction "6_6") (pintype "passive"))
      (node (ref "MD2") (pin "7") (pinfunction "7_7") (pintype "passive"))
      (node (ref "MD2") (pin "~2") (pinfunction "2_~2") (pintype "passive"))
      (node (ref "MD2") (pin "~7") (pinfunction "7_~7") (pintype "passive"))
      (node (ref "MD2") (pin "~8") (pinfunction "8_~8") (pintype "passive"))
      (node (ref "MD3") (pin "10") (pinfunction "GND_10") (pintype "power_in"))
      (node (ref "MD5") (pin "~2") (pinfunction "2_~2") (pintype "bidirectional"))
      (node (ref "MD5") (pin "~4") (pinfunction "2_~4") (pintype "bidirectional"))
      (node (ref "MD6") (pin "10") (pinfunction "GND4_10") (pintype "bidirectional"))
      (node (ref "MD6") (pin "12") (pinfunction "GND5_12") (pintype "bidirectional"))
      (node (ref "MD6") (pin "13") (pinfunction "GND6_13") (pintype "bidirectional"))
      (node (ref "MD6") (pin "17") (pinfunction "TREQ_17") (pintype "bidirectional"))
      (node (ref "MD6") (pin "19") (pinfunction "MODE1_19") (pintype "bidirectional"))
      (node (ref "MD6") (pin "2") (pinfunction "GND0_2") (pintype "bidirectional"))
      (node (ref "MD6") (pin "20") (pinfunction "MODE2_20") (pintype "bidirectional"))
      (node (ref "MD6") (pin "24") (pinfunction "GND7_24") (pintype "bidirectional"))
      (node (ref "MD6") (pin "4") (pinfunction "GND1_4") (pintype "bidirectional"))
      (node (ref "MD6") (pin "6") (pinfunction "GND2_6") (pintype "bidirectional"))
      (node (ref "MD6") (pin "9") (pinfunction "GND3_9") (pintype "bidirectional"))
      (node (ref "R26") (pin "1") (pinfunction "1_1") (pintype "passive"))
      (node (ref "R27") (pin "1") (pinfunction "1_1") (pintype "passive"))
      (node (ref "R36") (pin "2") (pinfunction "2_2") (pintype "passive"))
      (node (ref "R39") (pin "1") (pinfunction "1_1") (pintype "passive"))
      (node (ref "R42") (pin "1") (pinfunction "1_1") (pintype "passive"))
      (node (ref "R49") (pin "1") (pinfunction "1_1") (pintype "passive"))
      (node (ref "R55") (pin "2") (pinfunction "2_2") (pintype "passive"))
      (node (ref "R93") (pin "2") (pinfunction "2_2") (pintype "passive"))
      (node (ref "R94") (pin "2") (pinfunction "2_2") (pintype "passive"))
      (node (ref "R99") (pin "1") (pinfunction "1_1") (pintype "passive"))
      (node (ref "S1") (pin "3") (pinfunction "P_3") (pintype "passive"))
      (node (ref "S1") (pin "4") (pinfunction "P1_4") (pintype "passive"))
      (node (ref "S2") (pin "3") (pinfunction "P_3") (pintype "passive"))
      (node (ref "S2") (pin "4") (pinfunction "P1_4") (pintype "passive"))
      (node (ref "S3") (pin "3") (pinfunction "P_3") (pintype "passive"))
      (node (ref "S3") (pin "4") (pinfunction "P1_4") (pintype "passive"))
      (node (ref "S4") (pin "3") (pinfunction "P_3") (pintype "passive"))
      (node (ref "S4") (pin "4") (pinfunction "P1_4") (pintype "passive"))
      (node (ref "S5") (pin "3") (pinfunction "P_3") (pintype "passive"))
      (node (ref "S5") (pin "4") (pinfunction "P1_4") (pintype "passive"))
      (node (ref "S6") (pin "3") (pinfunction "P_3") (pintype "passive"))
      (node (ref "S6") (pin "4") (pinfunction "P1_4") (pintype "passive"))
      (node (ref "S7") (pin "3") (pinfunction "P_3") (pintype "passive"))
      (node (ref "S7") (pin "4") (pinfunction "P1_4") (pintype "passive"))
      (node (ref "U1") (pin "4") (pinfunction "LE_4") (pintype "bidirectional"))
      (node (ref "U1") (pin "5") (pinfunction "~{OE1}_5") (pintype "bidirectional"))
      (node (ref "U1") (pin "8") (pinfunction "GND_8") (pintype "bidirectional"))
      (node (ref "U10") (pin "4") (pinfunction "GND_4") (pintype "passive"))
      (node (ref "U11") (pin "9") (pinfunction "GND_9") (pintype "bidirectional"))
      (node (ref "U12") (pin "4") (pinfunction "VSS_4") (pintype "power_in"))
      (node (ref "U13") (pin "4") (pinfunction "GND_4") (pintype "passive"))
      (node (ref "U14") (pin "4") (pinfunction "VSS_4") (pintype "bidirectional"))
      (node (ref "U14") (pin "5") (pinfunction "GND_5") (pintype "bidirectional"))
      (node (ref "U15") (pin "4") (pinfunction "VSS_4") (pintype "bidirectional"))
      (node (ref "U15") (pin "5") (pinfunction "GND_5") (pintype "bidirectional"))
      (node (ref "U17") (pin "5") (pinfunction "GND2_5") (pintype "bidirectional"))
      (node (ref "U18") (pin "2") (pinfunction "GND_2") (pintype "bidirectional"))
      (node (ref "U18") (pin "5") (pinfunction "GS0_5") (pintype "bidirectional"))
      (node (ref "U18") (pin "6") (pinfunction "GS1_6") (pintype "bidirectional"))
      (node (ref "U18") (pin "7") (pinfunction "REF_7") (pintype "bidirectional"))
      (node (ref "U19") (pin "2") (pinfunction "GND_2") (pintype "bidirectional"))
      (node (ref "U19") (pin "5") (pinfunction "GS0_5") (pintype "bidirectional"))
      (node (ref "U19") (pin "6") (pinfunction "GS1_6") (pintype "bidirectional"))
      (node (ref "U19") (pin "7") (pinfunction "REF_7") (pintype "bidirectional"))
      (node (ref "U2") (pin "2") (pinfunction "GND_2") (pintype "bidirectional"))
      (node (ref "U20") (pin "10") (pinfunction "PP2_10") (pintype "bidirectional"))
      (node (ref "U20") (pin "6") (pinfunction "GND_6") (pintype "bidirectional"))
      (node (ref "U20") (pin "9") (pinfunction "PP1_9") (pintype "bidirectional"))
      (node (ref "U21") (pin "4") (pinfunction "GND_4") (pintype "passive"))
      (node (ref "U22") (pin "4") (pinfunction "GND_4") (pintype "passive"))
      (node (ref "U23") (pin "4") (pinfunction "GND_4") (pintype "passive"))
      (node (ref "U24") (pin "4") (pinfunction "GND_4") (pintype "passive"))
      (node (ref "U25") (pin "4") (pinfunction "GND_4") (pintype "passive"))
      (node (ref "U3") (pin "2") (pinfunction "GND_2") (pintype "bidirectional"))
      (node (ref "U4") (pin "4") (pinfunction "GND_4") (pintype "passive"))
      (node (ref "U5") (pin "16") (pinfunction "GND1_16") (pintype "power_in"))
      (node (ref "U5") (pin "6") (pinfunction "GND_6") (pintype "power_in"))
      (node (ref "U6") (pin "4") (pinfunction "GND_4") (pintype "passive"))
      (node (ref "U7") (pin "4") (pinfunction "GND_4") (pintype "passive"))
      (node (ref "U8") (pin "4") (pinfunction "GND_4") (pintype "passive"))
      (node (ref "U9") (pin "4") (pinfunction "GND_4") (pintype "passive"))
    )
    (net (code "28") (name "GPIO0_7") (class "Default")
      (node (ref "J32") (pin "21") (pinfunction "21_21") (pintype "passive"))
      (node (ref "MD1") (pin "~42") (pinfunction "42_~42") (pintype "bidirectional"))
      (node (ref "R57") (pin "1") (pinfunction "1_1") (pintype "passive"))
    )
    (net (code "29") (name "GPIO0_20") (class "Default")
      (node (ref "J32") (pin "23") (pinfunction "23_23") (pintype "passive"))
      (node (ref "MD1") (pin "~41") (pinfunction "41_~41") (pintype "bidirectional"))
    )
    (net (code "30") (name "GPIO0_23") (class "Default")
      (node (ref "J29") (pin "2") (pinfunction "2_2") (pintype "passive"))
      (node (ref "MD1") (pin "13") (pinfunction "13_13") (pintype "bidirectional"))
      (node (ref "R34") (pin "1") (pinfunction "1_1") (pintype "passive"))
    )
    (net (code "31") (name "GPIO1_12") (class "Default")
      (node (ref "J32") (pin "14") (pinfunction "14_14") (pintype "passive"))
      (node (ref "MD1") (pin "12") (pinfunction "12_12") (pintype "bidirectional"))
      (node (ref "R52") (pin "1") (pinfunction "1_1") (pintype "passive"))
    )
    (net (code "32") (name "GPIO1_13") (class "Default")
      (node (ref "J32") (pin "12") (pinfunction "12_12") (pintype "passive"))
      (node (ref "MD1") (pin "11") (pinfunction "11_11") (pintype "bidirectional"))
      (node (ref "R51") (pin "1") (pinfunction "1_1") (pintype "passive"))
      (node (ref "R82") (pin "2") (pinfunction "2_2") (pintype "passive"))
    )
    (net (code "33") (name "GPIO1_14") (class "Default")
      (node (ref "J32") (pin "19") (pinfunction "19_19") (pintype "passive"))
      (node (ref "MD1") (pin "16") (pinfunction "16_16") (pintype "bidirectional"))
      (node (ref "R37") (pin "2") (pinfunction "2_2") (pintype "passive"))
      (node (ref "R98") (pin "1") (pinfunction "1_1") (pintype "passive"))
    )
    (net (code "34") (name "GPIO1_15") (class "Default")
      (node (ref "J32") (pin "17") (pinfunction "17_17") (pintype "passive"))
      (node (ref "MD1") (pin "15") (pinfunction "15_15") (pintype "bidirectional"))
      (node (ref "R40") (pin "2") (pinfunction "2_2") (pintype "passive"))
    )
    (net (code "35") (name "GPIO2_3") (class "Default")
      (node (ref "J32") (pin "8") (pinfunction "8_8") (pintype "passive"))
      (node (ref "MD1") (pin "8") (pinfunction "8_8") (pintype "bidirectional"))
      (node (ref "R53") (pin "2") (pinfunction "2_2") (pintype "passive"))
    )
    (net (code "36") (name "GPIO2_5") (class "Default")
      (node (ref "J32") (pin "10") (pinfunction "10_10") (pintype "passive"))
      (node (ref "MD1") (pin "9") (pinfunction "9_9") (pintype "bidirectional"))
      (node (ref "R69") (pin "2") (pinfunction "2_2") (pintype "passive"))
    )
    (net (code "37") (name "I2C1_SCL") (class "Default")
      (node (ref "J32") (pin "16") (pinfunction "16_16") (pintype "passive"))
      (node (ref "J41") (pin "2") (pinfunction "2_2") (pintype "passive"))
      (node (ref "MD1") (pin "~17") (pinfunction "17_~17") (pintype "bidirectional"))
      (node (ref "R59") (pin "2") (pinfunction "2_2") (pintype "passive"))
    )
    (net (code "38") (name "I2C1_SDA") (class "Default")
      (node (ref "J32") (pin "18") (pinfunction "18_18") (pintype "passive"))
      (node (ref "J41") (pin "4") (pinfunction "4_4") (pintype "passive"))
      (node (ref "MD1") (pin "~18") (pinfunction "18_~18") (pintype "bidirectional"))
      (node (ref "R25") (pin "2") (pinfunction "2_2") (pintype "passive"))
    )
    (net (code "39") (name "I2C2-SCL") (class "Default")
      (node (ref "J30") (pin "4") (pinfunction "4_4") (pintype "passive"))
      (node (ref "MD1") (pin "~19") (pinfunction "19_~19") (pintype "bidirectional"))
      (node (ref "MD2") (pin "~3") (pinfunction "3_~3") (pintype "passive"))
      (node (ref "R33") (pin "2") (pinfunction "2_2") (pintype "passive"))
      (node (ref "U12") (pin "6") (pinfunction "SCL_6") (pintype "bidirectional"))
    )
    (net (code "40") (name "I2C2-SDA") (class "Default")
      (node (ref "J30") (pin "7") (pinfunction "7_7") (pintype "passive"))
      (node (ref "MD1") (pin "~20") (pinfunction "20_~20") (pintype "bidirectional"))
      (node (ref "MD2") (pin "~4") (pinfunction "4_~4") (pintype "passive"))
      (node (ref "R32") (pin "2") (pinfunction "2_2") (pintype "passive"))
      (node (ref "U12") (pin "5") (pinfunction "SDA_5") (pintype "bidirectional"))
    )
    (net (code "41") (name "I2C{slash}~{SPI}") (class "Default")
      (node (ref "J10") (pin "2") (pinfunction "2_2") (pintype "passive"))
      (node (ref "R36") (pin "1") (pinfunction "1_1") (pintype "passive"))
      (node (ref "U11") (pin "8") (pinfunction "I2C/~{SPI}_8") (pintype "bidirectional"))
    )
    (net (code "42") (name "KNX_3.3V") (class "Default")
      (node (ref "J21") (pin "8") (pinfunction "8_8") (pintype "passive"))
      (node (ref "J22") (pin "1") (pinfunction "1_1") (pintype "passive"))
      (node (ref "J22") (pin "2") (pinfunction "2_2") (pintype "passive"))
      (node (ref "J22") (pin "3") (pinfunction "3_3") (pintype "passive"))
      (node (ref "MD6") (pin "23") (pinfunction "3.3V_23") (pintype "bidirectional"))
      (node (ref "R31") (pin "1") (pinfunction "1_1") (pintype "passive"))
      (node (ref "R38") (pin "2") (pinfunction "2_2") (pintype "passive"))
    )
    (net (code "43") (name "KNX_3.3V_DIV") (class "Default")
      (node (ref "C23") (pin "1") (pinfunction "+_1") (pintype "passive"))
      (node (ref "R38") (pin "1") (pinfunction "1_1") (pintype "passive"))
      (node (ref "R39") (pin "2") (pinfunction "2_2") (pintype "passive"))
      (node (ref "U15") (pin "11") (pinfunction "S3_11") (pintype "bidirectional"))
    )
    (net (code "44") (name "KNX_ANAOUT") (class "Default")
      (node (ref "J21") (pin "3") (pinfunction "3_3") (pintype "passive"))
      (node (ref "MD6") (pin "5") (pinfunction "ANAOUT_5") (pintype "bidirectional"))
      (node (ref "R41") (pin "2") (pinfunction "2_2") (pintype "passive"))
    )
    (net (code "45") (name "KNX_ANAOUT_DIV") (class "Default")
      (node (ref "C22") (pin "1") (pinfunction "+_1") (pintype "passive"))
      (node (ref "R41") (pin "1") (pinfunction "1_1") (pintype "passive"))
      (node (ref "R42") (pin "2") (pinfunction "2_2") (pintype "passive"))
      (node (ref "U14") (pin "6") (pinfunction "S4_6") (pintype "bidirectional"))
    )
    (net (code "46") (name "KNX_CSB") (class "Default")
      (node (ref "J23") (pin "2") (pinfunction "2_2") (pintype "passive"))
      (node (ref "MD6") (pin "18") (pinfunction "CSB_18") (pintype "bidirectional"))
    )
    (net (code "47") (name "KNX_RESETB") (class "Default")
      (node (ref "J21") (pin "5") (pinfunction "5_5") (pintype "passive"))
      (node (ref "MD6") (pin "8") (pinfunction "KNX_RESETB_8") (pintype "bidirectional"))
    )
    (net (code "48") (name "KNX_RX") (class "Default")
      (node (ref "MD6") (pin "15") (pinfunction "RXD_15") (pintype "bidirectional"))
      (node (ref "R31") (pin "2") (pinfunction "2_2") (pintype "passive"))
      (node (ref "U24") (pin "2") (pinfunction "1A_2") (pintype "input"))
      (node (ref "U8") (pin "3") (pinfunction "2Y_3") (pintype "output"))
    )
    (net (code "49") (name "KNX_SAVEB") (class "Default")
      (node (ref "J21") (pin "4") (pinfunction "4_4") (pintype "passive"))
      (node (ref "MD6") (pin "7") (pinfunction "SAVEB_7") (pintype "bidirectional"))
      (node (ref "U13") (pin "2") (pinfunction "1A_2") (pintype "input"))
    )
    (net (code "50") (name "KNX_SCK") (class "Default")
      (node (ref "J23") (pin "3") (pinfunction "3_3") (pintype "passive"))
      (node (ref "MD6") (pin "14") (pinfunction "SCK_14") (pintype "bidirectional"))
    )
    (net (code "51") (name "KNX_SEL") (class "Default")
      (node (ref "U1") (pin "11") (pinfunction "Y4_11") (pintype "bidirectional"))
      (node (ref "U24") (pin "1") (pinfunction "1OE_1") (pintype "input"))
      (node (ref "U24") (pin "7") (pinfunction "2OE_7") (pintype "input"))
      (node (ref "U8") (pin "1") (pinfunction "1OE_1") (pintype "input"))
      (node (ref "U8") (pin "7") (pinfunction "2OE_7") (pintype "input"))
    )
    (net (code "52") (name "KNX_TRIG") (class "Default")
      (node (ref "J21") (pin "7") (pinfunction "7_7") (pintype "passive"))
      (node (ref "MD6") (pin "22") (pinfunction "TRIG_22") (pintype "bidirectional"))
      (node (ref "U13") (pin "5") (pinfunction "2A_5") (pintype "input"))
    )
    (net (code "53") (name "KNX_TX") (class "Default")
      (node (ref "MD6") (pin "16") (pinfunction "TXD_16") (pintype "bidirectional"))
      (node (ref "U24") (pin "5") (pinfunction "2A_5") (pintype "input"))
      (node (ref "U8") (pin "2") (pinfunction "1A_2") (pintype "input"))
    )
    (net (code "54") (name "KNX_V2") (class "Default")
      (node (ref "J21") (pin "1") (pinfunction "1_1") (pintype "passive"))
      (node (ref "MD6") (pin "1") (pinfunction "KNX_V2_1") (pintype "bidirectional"))
    )
    (net (code "55") (name "KNX_V20V") (class "Default")
      (node (ref "J21") (pin "2") (pinfunction "2_2") (pintype "passive"))
      (node (ref "MD6") (pin "3") (pinfunction "KNX_V20V_3") (pintype "bidirectional"))
    )
    (net (code "56") (name "KNX_XCLK") (class "Default")
      (node (ref "J21") (pin "6") (pinfunction "6_6") (pintype "passive"))
      (node (ref "MD6") (pin "11") (pinfunction "KNX_XCLK_11") (pintype "bidirectional"))
    )
    (net (code "57") (name "KNX_XCLKC") (class "Default")
      (node (ref "J23") (pin "1") (pinfunction "1_1") (pintype "passive"))
      (node (ref "MD6") (pin "21") (pinfunction "XCLKC_21") (pintype "bidirectional"))
    )
    (net (code "58") (name "LCD_DATA0") (class "Default")
      (node (ref "MD2") (pin "24") (pinfunction "24_24") (pintype "passive"))
      (node (ref "R1") (pin "1") (pinfunction "1_1") (pintype "passive"))
    )
    (net (code "59") (name "LCD_DATA1") (class "Default")
      (node (ref "MD2") (pin "25") (pinfunction "25_25") (pintype "passive"))
      (node (ref "R2") (pin "2") (pinfunction "2_2") (pintype "passive"))
    )
    (net (code "60") (name "LCD_DATA2") (class "Default")
      (node (ref "MD2") (pin "26") (pinfunction "26_26") (pintype "passive"))
      (node (ref "R3") (pin "1") (pinfunction "1_1") (pintype "passive"))
    )
    (net (code "61") (name "LCD_DATA3") (class "Default")
      (node (ref "MD2") (pin "27") (pinfunction "27_27") (pintype "passive"))
      (node (ref "R4") (pin "2") (pinfunction "2_2") (pintype "passive"))
    )
    (net (code "62") (name "LCD_DATA4") (class "Default")
      (node (ref "MD2") (pin "28") (pinfunction "28_28") (pintype "passive"))
      (node (ref "R5") (pin "1") (pinfunction "1_1") (pintype "passive"))
    )
    (net (code "63") (name "LCD_DATA5") (class "Default")
      (node (ref "MD2") (pin "15") (pinfunction "15_15") (pintype "passive"))
      (node (ref "R6") (pin "2") (pinfunction "2_2") (pintype "passive"))
    )
    (net (code "64") (name "LCD_DATA6") (class "Default")
      (node (ref "MD2") (pin "16") (pinfunction "16_16") (pintype "passive"))
      (node (ref "R7") (pin "1") (pinfunction "1_1") (pintype "passive"))
    )
    (net (code "65") (name "LCD_DATA7") (class "Default")
      (node (ref "MD2") (pin "17") (pinfunction "17_17") (pintype "passive"))
      (node (ref "R8") (pin "2") (pinfunction "2_2") (pintype "passive"))
    )
    (net (code "66") (name "LCD_DATA8") (class "Default")
      (node (ref "MD2") (pin "18") (pinfunction "18_18") (pintype "passive"))
      (node (ref "R9") (pin "1") (pinfunction "1_1") (pintype "passive"))
    )
    (net (code "67") (name "LCD_DATA9") (class "Default")
      (node (ref "MD2") (pin "19") (pinfunction "19_19") (pintype "passive"))
      (node (ref "R10") (pin "2") (pinfunction "2_2") (pintype "passive"))
    )
    (net (code "68") (name "LCD_DATA10") (class "Default")
      (node (ref "MD2") (pin "20") (pinfunction "20_20") (pintype "passive"))
      (node (ref "R12") (pin "2") (pinfunction "2_2") (pintype "passive"))
    )
    (net (code "69") (name "LCD_DATA11") (class "Default")
      (node (ref "MD2") (pin "8") (pinfunction "8_8") (pintype "passive"))
      (node (ref "R14") (pin "2") (pinfunction "2_2") (pintype "passive"))
    )
    (net (code "70") (name "LCD_DATA12") (class "Default")
      (node (ref "MD2") (pin "9") (pinfunction "9_9") (pintype "passive"))
      (node (ref "R11") (pin "1") (pinfunction "1_1") (pintype "passive"))
    )
    (net (code "71") (name "LCD_DATA13") (class "Default")
      (node (ref "MD2") (pin "10") (pinfunction "10_10") (pintype "passive"))
      (node (ref "R13") (pin "1") (pinfunction "1_1") (pintype "passive"))
    )
    (net (code "72") (name "LCD_DATA14") (class "Default")
      (node (ref "MD2") (pin "11") (pinfunction "11_11") (pintype "passive"))
      (node (ref "R15") (pin "1") (pinfunction "1_1") (pintype "passive"))
    )
    (net (code "73") (name "LCD_DATA15") (class "Default")
      (node (ref "MD2") (pin "12") (pinfunction "12_12") (pintype "passive"))
      (node (ref "R16") (pin "2") (pinfunction "2_2") (pintype "passive"))
    )
    (net (code "74") (name "LCD_DATA_EN") (class "Default")
      (node (ref "MD2") (pin "34") (pinfunction "34_34") (pintype "passive"))
      (node (ref "R18") (pin "2") (pinfunction "2_2") (pintype "passive"))
    )
    (net (code "75") (name "LCD_DISP") (class "Default")
      (node (ref "MD2") (pin "31") (pinfunction "31_31") (pintype "passive"))
      (node (ref "R66") (pin "2") (pinfunction "2_2") (pintype "passive"))
    )
    (net (code "76") (name "LCD_HSYNC") (class "Default")
      (node (ref "MD2") (pin "32") (pinfunction "32_32") (pintype "passive"))
      (node (ref "R17") (pin "1") (pinfunction "1_1") (pintype "passive"))
    )
    (net (code "77") (name "LCD_INT") (class "Default")
      (node (ref "J29") (pin "5") (pinfunction "5_5") (pintype "passive"))
      (node (ref "MD1") (pin "10") (pinfunction "10_10") (pintype "bidirectional"))
      (node (ref "R67") (pin "2") (pinfunction "2_2") (pintype "passive"))
    )
    (net (code "78") (name "LCD_PCLK") (class "Default")
      (node (ref "MD2") (pin "30") (pinfunction "30_30") (pintype "passive"))
      (node (ref "R20") (pin "2") (pinfunction "2_2") (pintype "passive"))
    )
    (net (code "79") (name "LCD_TEST_V") (class "Default")
      (node (ref "J31") (pin "2") (pinfunction "2_2") (pintype "passive"))
      (node (ref "J32") (pin "11") (pinfunction "11_11") (pintype "passive"))
      (node (ref "U14") (pin "14") (pinfunction "S2_14") (pintype "bidirectional"))
    )
    (net (code "80") (name "LCD_VSYNC") (class "Default")
      (node (ref "MD2") (pin "33") (pinfunction "33_33") (pintype "passive"))
      (node (ref "R19") (pin "1") (pinfunction "1_1") (pintype "passive"))
    )
    (net (code "81") (name "LED_A") (class "Default")
      (node (ref "C6") (pin "1") (pinfunction "+_1") (pintype "passive"))
      (node (ref "D5") (pin "C") (pinfunction "C_C") (pintype "passive"))
      (node (ref "J31") (pin "1") (pinfunction "1_1") (pintype "passive"))
      (node (ref "MD2") (pin "2") (pinfunction "2_2") (pintype "passive"))
    )
    (net (code "82") (name "LED_HEARTBEAT") (class "Default")
      (node (ref "MD1") (pin "~12") (pinfunction "12_~12") (pintype "bidirectional"))
      (node (ref "U25") (pin "2") (pinfunction "1A_2") (pintype "input"))
    )
    (net (code "83") (name "LED_K") (class "Default")
      (node (ref "J31") (pin "3") (pinfunction "3_3") (pintype "passive"))
      (node (ref "MD2") (pin "1") (pinfunction "1_1") (pintype "passive"))
      (node (ref "R26") (pin "2") (pinfunction "2_2") (pintype "passive"))
      (node (ref "R27") (pin "2") (pinfunction "2_2") (pintype "passive"))
      (node (ref "R28") (pin "2") (pinfunction "2_2") (pintype "passive"))
    )
    (net (code "84") (name "LEFT_BUT") (class "Default")
      (node (ref "MD1") (pin "~15") (pinfunction "15_~15") (pintype "bidirectional"))
      (node (ref "R80") (pin "1") (pinfunction "1_1") (pintype "passive"))
      (node (ref "S6") (pin "1") (pinfunction "S_1") (pintype "passive"))
      (node (ref "S6") (pin "2") (pinfunction "S1_2") (pintype "passive"))
    )
    (net (code "85") (name "MMC1_CLK") (class "Default")
      (node (ref "MD1") (pin "21") (pinfunction "21_21") (pintype "bidirectional"))
    )
    (net (code "86") (name "MMC1_CMD") (class "Default")
      (node (ref "MD1") (pin "20") (pinfunction "20_20") (pintype "bidirectional"))
    )
    (net (code "87") (name "MMC1_DAT0") (class "Default")
      (node (ref "MD1") (pin "25") (pinfunction "25_25") (pintype "bidirectional"))
    )
    (net (code "88") (name "MMC1_DAT1") (class "Default")
      (node (ref "MD1") (pin "24") (pinfunction "24_24") (pintype "bidirectional"))
    )
    (net (code "89") (name "MMC1_DAT2") (class "Default")
      (node (ref "MD1") (pin "5") (pinfunction "5_5") (pintype "bidirectional"))
    )
    (net (code "90") (name "MMC1_DAT3") (class "Default")
      (node (ref "MD1") (pin "6") (pinfunction "6_6") (pintype "bidirectional"))
    )
    (net (code "91") (name "MMC1_DAT4") (class "Default")
      (node (ref "MD1") (pin "23") (pinfunction "23_23") (pintype "bidirectional"))
    )
    (net (code "92") (name "MMC1_DAT5") (class "Default")
      (node (ref "MD1") (pin "22") (pinfunction "22_22") (pintype "bidirectional"))
    )
    (net (code "93") (name "MMC1_DAT6") (class "Default")
      (node (ref "MD1") (pin "3") (pinfunction "3_3") (pintype "bidirectional"))
    )
    (net (code "94") (name "MMC1_DAT7") (class "Default")
      (node (ref "MD1") (pin "4") (pinfunction "4_4") (pintype "bidirectional"))
    )
    (net (code "95") (name "Net-(C1-+)") (class "Default")
      (node (ref "C1") (pin "1") (pinfunction "+_1") (pintype "passive"))
      (node (ref "J12") (pin "3") (pinfunction "3_3") (pintype "passive"))
      (node (ref "R22") (pin "1") (pinfunction "1_1") (pintype "passive"))
    )
    (net (code "96") (name "Net-(C2-+)") (class "Default")
      (node (ref "C2") (pin "1") (pinfunction "+_1") (pintype "passive"))
      (node (ref "J12") (pin "2") (pinfunction "2_2") (pintype "passive"))
      (node (ref "R21") (pin "1") (pinfunction "1_1") (pintype "passive"))
    )
    (net (code "97") (name "Net-(C14-+)") (class "Default")
      (node (ref "C14") (pin "1") (pinfunction "+_1") (pintype "passive"))
      (node (ref "R47") (pin "1") (pinfunction "1_1") (pintype "passive"))
      (node (ref "R48") (pin "1") (pinfunction "1_1") (pintype "passive"))
    )
    (net (code "98") (name "Net-(C19-+)") (class "Default")
      (node (ref "C19") (pin "1") (pinfunction "+_1") (pintype "passive"))
      (node (ref "R65") (pin "2") (pinfunction "2_2") (pintype "passive"))
      (node (ref "U20") (pin "5") (pinfunction "OUT2_5") (pintype "bidirectional"))
      (node (ref "U20") (pin "8") (pinfunction "OUT1_8") (pintype "bidirectional"))
    )
    (net (code "99") (name "Net-(C20-+)") (class "Default")
      (node (ref "C20") (pin "1") (pinfunction "+_1") (pintype "passive"))
      (node (ref "FB2") (pin "2") (pinfunction "P$2_2") (pintype "bidirectional"))
      (node (ref "MD2") (pin "4") (pinfunction "4_4") (pintype "passive"))
    )
    (net (code "100") (name "Net-(C30-+)") (class "Default")
      (node (ref "C30") (pin "1") (pinfunction "+_1") (pintype "passive"))
      (node (ref "C31") (pin "1") (pinfunction "+_1") (pintype "passive"))
      (node (ref "FB1") (pin "1") (pinfunction "P$1_1") (pintype "bidirectional"))
      (node (ref "U5") (pin "15") (pinfunction "VCC_15") (pintype "power_in"))
    )
    (net (code "101") (name "Net-(C38-+)") (class "Default")
      (node (ref "C38") (pin "1") (pinfunction "+_1") (pintype "passive"))
      (node (ref "J40") (pin "2") (pinfunction "2_2") (pintype "passive"))
      (node (ref "MD5") (pin "2") (pinfunction "VMCU_2") (pintype "bidirectional"))
      (node (ref "U17") (pin "1") (pinfunction "+V1_1") (pintype "bidirectional"))
    )
    (net (code "102") (name "Net-(C38--)") (class "Default")
      (node (ref "C38") (pin "2") (pinfunction "-_2") (pintype "passive"))
      (node (ref "J40") (pin "3") (pinfunction "3_3") (pintype "passive"))
      (node (ref "MD5") (pin "3") (pinfunction "3_3") (pintype "bidirectional"))
      (node (ref "MD5") (pin "`3") (pinfunction "GND_`3") (pintype "bidirectional"))
      (node (ref "U17") (pin "4") (pinfunction "GND1_4") (pintype "bidirectional"))
    )
    (net (code "103") (name "Net-(C48-+)") (class "Default")
      (node (ref "C48") (pin "1") (pinfunction "+_1") (pintype "passive"))
      (node (ref "MD1") (pin "~5") (pinfunction "5_~5") (pintype "bidirectional"))
      (node (ref "MD1") (pin "~6") (pinfunction "6_~6") (pintype "bidirectional"))
      (node (ref "R64") (pin "1") (pinfunction "1_1") (pintype "passive"))
    )
    (net (code "104") (name "Net-(C49-+)") (class "Default")
      (node (ref "C49") (pin "1") (pinfunction "+_1") (pintype "passive"))
      (node (ref "U20") (pin "7") (pinfunction "CT_7") (pintype "bidirectional"))
    )
    (net (code "105") (name "Net-(D1-PadC)") (class "Default")
      (node (ref "D1") (pin "C") (pinfunction "C_C") (pintype "passive"))
      (node (ref "R24") (pin "1") (pinfunction "1_1") (pintype "passive"))
    )
    (net (code "106") (name "Net-(D2-PadC)") (class "Default")
      (node (ref "D2") (pin "C") (pinfunction "C_C") (pintype "passive"))
      (node (ref "R23") (pin "1") (pinfunction "1_1") (pintype "passive"))
    )
    (net (code "107") (name "Net-(D3-PadC)") (class "Default")
      (node (ref "D3") (pin "C") (pinfunction "C_C") (pintype "passive"))
      (node (ref "R55") (pin "1") (pinfunction "1_1") (pintype "passive"))
    )
    (net (code "108") (name "Net-(D6-PadA)") (class "Default")
      (node (ref "D6") (pin "A") (pinfunction "A_A") (pintype "passive"))
      (node (ref "R83") (pin "2") (pinfunction "2_2") (pintype "passive"))
    )
    (net (code "109") (name "Net-(D8-PadA)") (class "Default")
      (node (ref "D8") (pin "A") (pinfunction "A_A") (pintype "passive"))
      (node (ref "R85") (pin "2") (pinfunction "2_2") (pintype "passive"))
    )
    (net (code "110") (name "Net-(D9-PadA)") (class "Default")
      (node (ref "D9") (pin "A") (pinfunction "A_A") (pintype "passive"))
      (node (ref "R86") (pin "2") (pinfunction "2_2") (pintype "passive"))
    )
    (net (code "111") (name "Net-(D10-PadA)") (class "Default")
      (node (ref "D10") (pin "A") (pinfunction "A_A") (pintype "passive"))
      (node (ref "R87") (pin "2") (pinfunction "2_2") (pintype "passive"))
    )
    (net (code "112") (name "Net-(D11-PadA)") (class "Default")
      (node (ref "D11") (pin "A") (pinfunction "A_A") (pintype "passive"))
      (node (ref "R88") (pin "2") (pinfunction "2_2") (pintype "passive"))
    )
    (net (code "113") (name "Net-(D12-PadA)") (class "Default")
      (node (ref "D12") (pin "A") (pinfunction "A_A") (pintype "passive"))
      (node (ref "R89") (pin "2") (pinfunction "2_2") (pintype "passive"))
    )
    (net (code "114") (name "Net-(D13-PadA)") (class "Default")
      (node (ref "D13") (pin "A") (pinfunction "A_A") (pintype "passive"))
      (node (ref "R90") (pin "2") (pinfunction "2_2") (pintype "passive"))
    )
    (net (code "115") (name "Net-(D14-PadA)") (class "Default")
      (node (ref "D14") (pin "A") (pinfunction "A_A") (pintype "passive"))
      (node (ref "R91") (pin "2") (pinfunction "2_2") (pintype "passive"))
    )
    (net (code "116") (name "Net-(D15-PadA)") (class "Default")
      (node (ref "D15") (pin "A") (pinfunction "A_A") (pintype "passive"))
      (node (ref "R92") (pin "2") (pinfunction "2_2") (pintype "passive"))
    )
    (net (code "117") (name "Net-(D16-PadC)") (class "Default")
      (node (ref "D16") (pin "C") (pinfunction "C_C") (pintype "passive"))
      (node (ref "R93") (pin "1") (pinfunction "1_1") (pintype "passive"))
    )
    (net (code "118") (name "Net-(D17-PadC)") (class "Default")
      (node (ref "D17") (pin "C") (pinfunction "C_C") (pintype "passive"))
      (node (ref "R94") (pin "1") (pinfunction "1_1") (pintype "passive"))
    )
    (net (code "119") (name "Net-(J13-Pad1)") (class "Default")
      (node (ref "J13") (pin "1") (pinfunction "1_1") (pintype "passive"))
      (node (ref "J17") (pin "1") (pinfunction "1_1") (pintype "passive"))
    )
    (net (code "120") (name "Net-(J13A-GND)") (class "Default")
      (node (ref "J13") (pin "2") (pinfunction "GND_2") (pintype "power_in"))
      (node (ref "J13") (pin "3") (pinfunction "GND_3") (pintype "power_in"))
      (node (ref "J13") (pin "4") (pinfunction "GND_4") (pintype "power_in"))
      (node (ref "J13") (pin "5") (pinfunction "GND_5") (pintype "power_in"))
      (node (ref "J17") (pin "2") (pinfunction "GND_2") (pintype "power_in"))
      (node (ref "J17") (pin "3") (pinfunction "GND_3") (pintype "power_in"))
      (node (ref "J17") (pin "4") (pinfunction "GND_4") (pintype "power_in"))
      (node (ref "J17") (pin "5") (pinfunction "GND_5") (pintype "power_in"))
    )
    (net (code "121") (name "Net-(J14-Pad1)") (class "Default")
      (node (ref "J14") (pin "1") (pinfunction "1_1") (pintype "passive"))
      (node (ref "J18") (pin "1") (pinfunction "1_1") (pintype "passive"))
    )
    (net (code "122") (name "Net-(J14A-GND)") (class "Default")
      (node (ref "J14") (pin "2") (pinfunction "GND_2") (pintype "power_in"))
      (node (ref "J14") (pin "3") (pinfunction "GND_3") (pintype "power_in"))
      (node (ref "J14") (pin "4") (pinfunction "GND_4") (pintype "power_in"))
      (node (ref "J14") (pin "5") (pinfunction "GND_5") (pintype "power_in"))
      (node (ref "J18") (pin "2") (pinfunction "GND_2") (pintype "power_in"))
      (node (ref "J18") (pin "3") (pinfunction "GND_3") (pintype "power_in"))
      (node (ref "J18") (pin "4") (pinfunction "GND_4") (pintype "power_in"))
      (node (ref "J18") (pin "5") (pinfunction "GND_5") (pintype "power_in"))
    )
    (net (code "123") (name "Net-(J35-Pad1)") (class "Default")
      (node (ref "J35") (pin "1") (pinfunction "1_1") (pintype "passive"))
      (node (ref "R63") (pin "2") (pinfunction "2_2") (pintype "passive"))
    )
    (net (code "124") (name "Net-(J35-Pad2)") (class "Default")
      (node (ref "J35") (pin "2") (pinfunction "2_2") (pintype "passive"))
      (node (ref "R72") (pin "2") (pinfunction "2_2") (pintype "passive"))
    )
    (net (code "125") (name "Net-(J36-Pad1)") (class "Default")
      (node (ref "J36") (pin "1") (pinfunction "1_1") (pintype "passive"))
      (node (ref "R73") (pin "1") (pinfunction "1_1") (pintype "passive"))
    )
    (net (code "126") (name "Net-(J38-Pad1)") (class "Default")
      (node (ref "J38") (pin "1") (pinfunction "1_1") (pintype "passive"))
      (node (ref "R74") (pin "1") (pinfunction "1_1") (pintype "passive"))
    )
    (net (code "127") (name "Net-(J40-Pad1)") (class "Default")
      (node (ref "J40") (pin "1") (pinfunction "1_1") (pintype "passive"))
      (node (ref "MD5") (pin "1") (pinfunction "1_1") (pintype "bidirectional"))
    )
    (net (code "128") (name "Net-(J40-Pad4)") (class "Default")
      (node (ref "J40") (pin "4") (pinfunction "4_4") (pintype "passive"))
      (node (ref "MD5") (pin "4") (pinfunction "4_4") (pintype "bidirectional"))
    )
    (net (code "129") (name "Net-(J40-Pad5)") (class "Default")
      (node (ref "J40") (pin "5") (pinfunction "5_5") (pintype "passive"))
      (node (ref "MD5") (pin "5") (pinfunction "5_5") (pintype "bidirectional"))
    )
    (net (code "130") (name "Net-(J40-Pad6)") (class "Default")
      (node (ref "J40") (pin "6") (pinfunction "6_6") (pintype "passive"))
      (node (ref "MD5") (pin "6") (pinfunction "6_6") (pintype "bidirectional"))
    )
    (net (code "131") (name "Net-(MD1-Pad26)") (class "Default")
      (node (ref "MD1") (pin "26") (pinfunction "26_26") (pintype "bidirectional"))
      (node (ref "R66") (pin "1") (pinfunction "1_1") (pintype "passive"))
    )
    (net (code "132") (name "Net-(MD1-Pad27)") (class "Default")
      (node (ref "MD1") (pin "27") (pinfunction "27_27") (pintype "bidirectional"))
      (node (ref "R19") (pin "2") (pinfunction "2_2") (pintype "passive"))
    )
    (net (code "133") (name "Net-(MD1-Pad28)") (class "Default")
      (node (ref "MD1") (pin "28") (pinfunction "28_28") (pintype "bidirectional"))
      (node (ref "R20") (pin "1") (pinfunction "1_1") (pintype "passive"))
    )
    (net (code "134") (name "Net-(MD1-Pad29)") (class "Default")
      (node (ref "MD1") (pin "29") (pinfunction "29_29") (pintype "bidirectional"))
      (node (ref "R17") (pin "2") (pinfunction "2_2") (pintype "passive"))
    )
    (net (code "135") (name "Net-(MD1-Pad30)") (class "Default")
      (node (ref "MD1") (pin "30") (pinfunction "30_30") (pintype "bidirectional"))
      (node (ref "R18") (pin "1") (pinfunction "1_1") (pintype "passive"))
    )
    (net (code "136") (name "Net-(MD1-Pad31)") (class "Default")
      (node (ref "MD1") (pin "31") (pinfunction "31_31") (pintype "bidirectional"))
      (node (ref "R15") (pin "2") (pinfunction "2_2") (pintype "passive"))
    )
    (net (code "137") (name "Net-(MD1-Pad32)") (class "Default")
      (node (ref "MD1") (pin "32") (pinfunction "32_32") (pintype "bidirectional"))
      (node (ref "R16") (pin "1") (pinfunction "1_1") (pintype "passive"))
    )
    (net (code "138") (name "Net-(MD1-Pad33)") (class "Default")
      (node (ref "MD1") (pin "33") (pinfunction "33_33") (pintype "bidirectional"))
      (node (ref "R13") (pin "2") (pinfunction "2_2") (pintype "passive"))
    )
    (net (code "139") (name "Net-(MD1-Pad34)") (class "Default")
      (node (ref "MD1") (pin "34") (pinfunction "34_34") (pintype "bidirectional"))
      (node (ref "R14") (pin "1") (pinfunction "1_1") (pintype "passive"))
    )
    (net (code "140") (name "Net-(MD1-Pad35)") (class "Default")
      (node (ref "MD1") (pin "35") (pinfunction "35_35") (pintype "bidirectional"))
      (node (ref "R11") (pin "2") (pinfunction "2_2") (pintype "passive"))
    )
    (net (code "141") (name "Net-(MD1-Pad36)") (class "Default")
      (node (ref "MD1") (pin "36") (pinfunction "36_36") (pintype "bidirectional"))
      (node (ref "R12") (pin "1") (pinfunction "1_1") (pintype "passive"))
    )
    (net (code "142") (name "Net-(MD1-Pad37)") (class "Default")
      (node (ref "MD1") (pin "37") (pinfunction "37_37") (pintype "bidirectional"))
      (node (ref "R9") (pin "2") (pinfunction "2_2") (pintype "passive"))
    )
    (net (code "143") (name "Net-(MD1-Pad38)") (class "Default")
      (node (ref "MD1") (pin "38") (pinfunction "38_38") (pintype "bidirectional"))
      (node (ref "R10") (pin "1") (pinfunction "1_1") (pintype "passive"))
    )
    (net (code "144") (name "Net-(MD1-Pad39)") (class "Default")
      (node (ref "MD1") (pin "39") (pinfunction "39_39") (pintype "bidirectional"))
      (node (ref "R7") (pin "2") (pinfunction "2_2") (pintype "passive"))
    )
    (net (code "145") (name "Net-(MD1-Pad40)") (class "Default")
      (node (ref "MD1") (pin "40") (pinfunction "40_40") (pintype "bidirectional"))
      (node (ref "R8") (pin "1") (pinfunction "1_1") (pintype "passive"))
    )
    (net (code "146") (name "Net-(MD1-Pad41)") (class "Default")
      (node (ref "MD1") (pin "41") (pinfunction "41_41") (pintype "bidirectional"))
      (node (ref "R5") (pin "2") (pinfunction "2_2") (pintype "passive"))
    )
    (net (code "147") (name "Net-(MD1-Pad42)") (class "Default")
      (node (ref "MD1") (pin "42") (pinfunction "42_42") (pintype "bidirectional"))
      (node (ref "R6") (pin "1") (pinfunction "1_1") (pintype "passive"))
    )
    (net (code "148") (name "Net-(MD1-Pad43)") (class "Default")
      (node (ref "MD1") (pin "43") (pinfunction "43_43") (pintype "bidirectional"))
      (node (ref "R3") (pin "2") (pinfunction "2_2") (pintype "passive"))
    )
    (net (code "149") (name "Net-(MD1-Pad44)") (class "Default")
      (node (ref "MD1") (pin "44") (pinfunction "44_44") (pintype "bidirectional"))
      (node (ref "R4") (pin "1") (pinfunction "1_1") (pintype "passive"))
    )
    (net (code "150") (name "Net-(MD1-Pad45)") (class "Default")
      (node (ref "MD1") (pin "45") (pinfunction "45_45") (pintype "bidirectional"))
      (node (ref "R1") (pin "2") (pinfunction "2_2") (pintype "passive"))
    )
    (net (code "151") (name "Net-(MD1-Pad46)") (class "Default")
      (node (ref "MD1") (pin "46") (pinfunction "46_46") (pintype "bidirectional"))
      (node (ref "R2") (pin "1") (pinfunction "1_1") (pintype "passive"))
    )
    (net (code "152") (name "Net-(MD2B-5)") (class "Default")
      (node (ref "MD2") (pin "~5") (pinfunction "5_~5") (pintype "passive"))
      (node (ref "R67") (pin "1") (pinfunction "1_1") (pintype "passive"))
    )
    (net (code "153") (name "Net-(MD2B-6)") (class "Default")
      (node (ref "MD2") (pin "~6") (pinfunction "6_~6") (pintype "passive"))
      (node (ref "R68") (pin "2") (pinfunction "2_2") (pintype "passive"))
      (node (ref "R69") (pin "1") (pinfunction "1_1") (pintype "passive"))
    )
    (net (code "154") (name "Net-(MD3-PWM0{slash}RSSI)") (class "Default")
      (node (ref "D3") (pin "A") (pinfunction "A_A") (pintype "passive"))
      (node (ref "MD3") (pin "6") (pinfunction "PWM0/RSSI_6") (pintype "bidirectional"))
    )
    (net (code "155") (name "Net-(MD5A-1-Pad~1)") (class "Default")
      (node (ref "MD5") (pin "~1") (pinfunction "1_~1") (pintype "bidirectional"))
      (node (ref "MD5") (pin "~3") (pinfunction "1_~3") (pintype "bidirectional"))
      (node (ref "R65") (pin "1") (pinfunction "1_1") (pintype "passive"))
    )
    (net (code "156") (name "Net-(MD5C-RX)") (class "Default")
      (node (ref "MD5") (pin "`2") (pinfunction "RX_`2") (pintype "bidirectional"))
      (node (ref "U17") (pin "3") (pinfunction "OUT2_3") (pintype "bidirectional"))
    )
    (net (code "157") (name "Net-(MD5C-TX)") (class "Default")
      (node (ref "MD5") (pin "`1") (pinfunction "TX_`1") (pintype "bidirectional"))
      (node (ref "U17") (pin "2") (pinfunction "IN1_2") (pintype "bidirectional"))
    )
    (net (code "158") (name "Net-(U1-Y1)") (class "Default")
      (node (ref "U1") (pin "14") (pinfunction "Y1_14") (pintype "bidirectional"))
      (node (ref "U4") (pin "1") (pinfunction "1OE_1") (pintype "input"))
      (node (ref "U4") (pin "7") (pinfunction "2OE_7") (pintype "input"))
    )
    (net (code "159") (name "Net-(U1-Y2)") (class "Default")
      (node (ref "U1") (pin "13") (pinfunction "Y2_13") (pintype "bidirectional"))
      (node (ref "U6") (pin "1") (pinfunction "1OE_1") (pintype "input"))
      (node (ref "U6") (pin "7") (pinfunction "2OE_7") (pintype "input"))
    )
    (net (code "160") (name "Net-(U1-Y6)") (class "Default")
      (node (ref "U1") (pin "9") (pinfunction "Y6_9") (pintype "bidirectional"))
      (node (ref "U10") (pin "1") (pinfunction "1OE_1") (pintype "input"))
      (node (ref "U10") (pin "7") (pinfunction "2OE_7") (pintype "input"))
    )
    (net (code "161") (name "Net-(U2-FB)") (class "Default")
      (node (ref "R28") (pin "1") (pinfunction "1_1") (pintype "passive"))
      (node (ref "U2") (pin "3") (pinfunction "FB_3") (pintype "bidirectional"))
    )
    (net (code "162") (name "Net-(U2-SW)") (class "Default")
      (node (ref "D5") (pin "A") (pinfunction "A_A") (pintype "passive"))
      (node (ref "L1") (pin "2") (pinfunction "2_2") (pintype "bidirectional"))
      (node (ref "U2") (pin "1") (pinfunction "SW_1") (pintype "bidirectional"))
    )
    (net (code "163") (name "Net-(U3-STB)") (class "Default")
      (node (ref "R49") (pin "2") (pinfunction "2_2") (pintype "passive"))
      (node (ref "R51") (pin "2") (pinfunction "2_2") (pintype "passive"))
      (node (ref "U3") (pin "8") (pinfunction "STB_8") (pintype "bidirectional"))
    )
    (net (code "164") (name "Net-(U4-1A)") (class "Default")
      (node (ref "U4") (pin "2") (pinfunction "1A_2") (pintype "input"))
      (node (ref "U4") (pin "3") (pinfunction "2Y_3") (pintype "output"))
    )
    (net (code "165") (name "Net-(U5-CBUS1)") (class "Default")
      (node (ref "R23") (pin "2") (pinfunction "2_2") (pintype "passive"))
      (node (ref "U5") (pin "17") (pinfunction "CBUS1_17") (pintype "bidirectional"))
    )
    (net (code "166") (name "Net-(U5-CBUS2)") (class "Default")
      (node (ref "R24") (pin "2") (pinfunction "2_2") (pintype "passive"))
      (node (ref "U5") (pin "10") (pinfunction "CBUS2_10") (pintype "bidirectional"))
    )
    (net (code "167") (name "Net-(U5-RXD)") (class "Default")
      (node (ref "J16") (pin "3") (pinfunction "3_3") (pintype "passive"))
      (node (ref "J19") (pin "1") (pinfunction "1_1") (pintype "passive"))
      (node (ref "R50") (pin "2") (pinfunction "2_2") (pintype "passive"))
      (node (ref "U5") (pin "4") (pinfunction "RXD_4") (pintype "input"))
    )
    (net (code "168") (name "Net-(U5-TXD)") (class "Default")
      (node (ref "J16") (pin "4") (pinfunction "4_4") (pintype "passive"))
      (node (ref "J19") (pin "2") (pinfunction "2_2") (pintype "passive"))
      (node (ref "U5") (pin "20") (pinfunction "TXD_20") (pintype "output"))
    )
    (net (code "169") (name "Net-(U5-USBDM)") (class "Default")
      (node (ref "R21") (pin "2") (pinfunction "2_2") (pintype "passive"))
      (node (ref "U5") (pin "12") (pinfunction "USBDM_12") (pintype "bidirectional"))
    )
    (net (code "170") (name "Net-(U5-USBDP)") (class "Default")
      (node (ref "R22") (pin "2") (pinfunction "2_2") (pintype "passive"))
      (node (ref "U5") (pin "11") (pinfunction "USBDP_11") (pintype "bidirectional"))
    )
    (net (code "171") (name "Net-(U5-~{CTS})") (class "Default")
      (node (ref "J15") (pin "3") (pinfunction "3_3") (pintype "passive"))
      (node (ref "U5") (pin "9") (pinfunction "~{CTS}_9") (pintype "input"))
    )
    (net (code "172") (name "Net-(U5-~{DTR})") (class "Default")
      (node (ref "J15") (pin "5") (pinfunction "5_5") (pintype "passive"))
      (node (ref "U5") (pin "1") (pinfunction "~{DTR}_1") (pintype "output"))
    )
    (net (code "173") (name "Net-(U5-~{RI})") (class "Default")
      (node (ref "R53") (pin "1") (pinfunction "1_1") (pintype "passive"))
      (node (ref "R62") (pin "1") (pinfunction "1_1") (pintype "passive"))
      (node (ref "U5") (pin "5") (pinfunction "~{RI}_5") (pintype "input"))
    )
    (net (code "174") (name "Net-(U5-~{RTS})") (class "Default")
      (node (ref "J15") (pin "1") (pinfunction "1_1") (pintype "passive"))
      (node (ref "U5") (pin "2") (pinfunction "~{RTS}_2") (pintype "output"))
    )
    (net (code "175") (name "Net-(U12-A0)") (class "Default")
      (node (ref "R43") (pin "2") (pinfunction "2_2") (pintype "passive"))
      (node (ref "U12") (pin "1") (pinfunction "A0_1") (pintype "bidirectional"))
    )
    (net (code "176") (name "Net-(U12-A1)") (class "Default")
      (node (ref "R44") (pin "2") (pinfunction "2_2") (pintype "passive"))
      (node (ref "U12") (pin "2") (pinfunction "A1_2") (pintype "bidirectional"))
    )
    (net (code "177") (name "Net-(U12-A2)") (class "Default")
      (node (ref "J25") (pin "2") (pinfunction "2_2") (pintype "passive"))
      (node (ref "R45") (pin "2") (pinfunction "2_2") (pintype "passive"))
      (node (ref "U12") (pin "3") (pinfunction "A2_3") (pintype "bidirectional"))
    )
    (net (code "178") (name "Net-(U13-1Y)") (class "Default")
      (node (ref "R40") (pin "1") (pinfunction "1_1") (pintype "passive"))
      (node (ref "U13") (pin "6") (pinfunction "1Y_6") (pintype "output"))
    )
    (net (code "179") (name "Net-(U13-2Y)") (class "Default")
      (node (ref "R37") (pin "1") (pinfunction "1_1") (pintype "passive"))
      (node (ref "U13") (pin "3") (pinfunction "2Y_3") (pintype "output"))
    )
    (net (code "180") (name "Net-(U18-IN+)") (class "Default")
      (node (ref "R64") (pin "4") (pinfunction "4_4") (pintype "passive"))
      (node (ref "U18") (pin "1") (pinfunction "IN+_1") (pintype "bidirectional"))
    )
    (net (code "181") (name "Net-(U18-IN-)") (class "Default")
      (node (ref "R64") (pin "3") (pinfunction "3_3") (pintype "passive"))
      (node (ref "U18") (pin "8") (pinfunction "IN-_8") (pintype "bidirectional"))
    )
    (net (code "182") (name "Net-(U18-OUT)") (class "Default")
      (node (ref "R70") (pin "1") (pinfunction "1_1") (pintype "passive"))
      (node (ref "U18") (pin "4") (pinfunction "OUT_4") (pintype "bidirectional"))
    )
    (net (code "183") (name "Net-(U19-IN+)") (class "Default")
      (node (ref "R65") (pin "4") (pinfunction "4_4") (pintype "passive"))
      (node (ref "U19") (pin "1") (pinfunction "IN+_1") (pintype "bidirectional"))
    )
    (net (code "184") (name "Net-(U19-IN-)") (class "Default")
      (node (ref "R65") (pin "3") (pinfunction "3_3") (pintype "passive"))
      (node (ref "U19") (pin "8") (pinfunction "IN-_8") (pintype "bidirectional"))
    )
    (net (code "185") (name "Net-(U19-OUT)") (class "Default")
      (node (ref "R71") (pin "1") (pinfunction "1_1") (pintype "passive"))
      (node (ref "U19") (pin "4") (pinfunction "OUT_4") (pintype "bidirectional"))
    )
    (net (code "186") (name "Net-(U21-1Y)") (class "Default")
      (node (ref "D8") (pin "C") (pinfunction "C_C") (pintype "passive"))
      (node (ref "U21") (pin "6") (pinfunction "1Y_6") (pintype "output"))
    )
    (net (code "187") (name "Net-(U21-2Y)") (class "Default")
      (node (ref "D9") (pin "C") (pinfunction "C_C") (pintype "passive"))
      (node (ref "U21") (pin "3") (pinfunction "2Y_3") (pintype "output"))
    )
    (net (code "188") (name "Net-(U22-1Y)") (class "Default")
      (node (ref "D10") (pin "C") (pinfunction "C_C") (pintype "passive"))
      (node (ref "U22") (pin "6") (pinfunction "1Y_6") (pintype "output"))
    )
    (net (code "189") (name "Net-(U22-2Y)") (class "Default")
      (node (ref "D11") (pin "C") (pinfunction "C_C") (pintype "passive"))
      (node (ref "U22") (pin "3") (pinfunction "2Y_3") (pintype "output"))
    )
    (net (code "190") (name "Net-(U23-1Y)") (class "Default")
      (node (ref "D12") (pin "C") (pinfunction "C_C") (pintype "passive"))
      (node (ref "U23") (pin "6") (pinfunction "1Y_6") (pintype "output"))
    )
    (net (code "191") (name "Net-(U23-2Y)") (class "Default")
      (node (ref "D13") (pin "C") (pinfunction "C_C") (pintype "passive"))
      (node (ref "U23") (pin "3") (pinfunction "2Y_3") (pintype "output"))
    )
    (net (code "192") (name "Net-(U24-1Y)") (class "Default")
      (node (ref "D14") (pin "C") (pinfunction "C_C") (pintype "passive"))
      (node (ref "U24") (pin "6") (pinfunction "1Y_6") (pintype "output"))
    )
    (net (code "193") (name "Net-(U24-2Y)") (class "Default")
      (node (ref "D15") (pin "C") (pinfunction "C_C") (pintype "passive"))
      (node (ref "U24") (pin "3") (pinfunction "2Y_3") (pintype "output"))
    )
    (net (code "194") (name "Net-(U25-1Y)") (class "Default")
      (node (ref "D16") (pin "A") (pinfunction "A_A") (pintype "passive"))
      (node (ref "U25") (pin "6") (pinfunction "1Y_6") (pintype "output"))
    )
    (net (code "195") (name "Net-(U25-2A)") (class "Default")
      (node (ref "R98") (pin "2") (pinfunction "2_2") (pintype "passive"))
      (node (ref "U25") (pin "5") (pinfunction "2A_5") (pintype "input"))
    )
    (net (code "196") (name "Net-(U25-2Y)") (class "Default")
      (node (ref "D17") (pin "A") (pinfunction "A_A") (pintype "passive"))
      (node (ref "U25") (pin "3") (pinfunction "2Y_3") (pintype "output"))
    )
    (net (code "197") (name "PWR_BUT") (class "Default")
      (node (ref "J30") (pin "1") (pinfunction "1_1") (pintype "passive"))
      (node (ref "MD1") (pin "~9") (pinfunction "9_~9") (pintype "bidirectional"))
      (node (ref "S1") (pin "1") (pinfunction "S_1") (pintype "passive"))
      (node (ref "S1") (pin "2") (pinfunction "S1_2") (pintype "passive"))
    )
    (net (code "198") (name "PWR_SW_ON") (class "Default")
      (node (ref "R56") (pin "1") (pinfunction "1_1") (pintype "passive"))
      (node (ref "R57") (pin "2") (pinfunction "2_2") (pintype "passive"))
      (node (ref "R99") (pin "2") (pinfunction "2_2") (pintype "passive"))
      (node (ref "U20") (pin "2") (pinfunction "ON_2") (pintype "bidirectional"))
      (node (ref "U22") (pin "1") (pinfunction "1OE_1") (pintype "input"))
      (node (ref "U22") (pin "7") (pinfunction "2OE_7") (pintype "input"))
    )
    (net (code "199") (name "READER_I-SENSE") (class "Default")
      (node (ref "C27") (pin "1") (pinfunction "+_1") (pintype "passive"))
      (node (ref "R71") (pin "2") (pinfunction "2_2") (pintype "passive"))
      (node (ref "U14") (pin "11") (pinfunction "S3_11") (pintype "bidirectional"))
    )
    (net (code "200") (name "READER_RX") (class "Default")
      (node (ref "J30") (pin "3") (pinfunction "3_3") (pintype "passive"))
      (node (ref "MD1") (pin "~13") (pinfunction "13_~13") (pintype "bidirectional"))
      (node (ref "U17") (pin "6") (pinfunction "IN2_6") (pintype "bidirectional"))
      (node (ref "U22") (pin "2") (pinfunction "1A_2") (pintype "input"))
    )
    (net (code "201") (name "READER_TX") (class "Default")
      (node (ref "J30") (pin "2") (pinfunction "2_2") (pintype "passive"))
      (node (ref "MD1") (pin "~11") (pinfunction "11_~11") (pintype "bidirectional"))
      (node (ref "U17") (pin "7") (pinfunction "OUT1_7") (pintype "bidirectional"))
      (node (ref "U22") (pin "5") (pinfunction "2A_5") (pintype "input"))
    )
    (net (code "202") (name "RESET") (class "Default")
      (node (ref "J29") (pin "4") (pinfunction "4_4") (pintype "passive"))
      (node (ref "MD1") (pin "19") (pinfunction "19_19") (pintype "bidirectional"))
      (node (ref "MD3") (pin "5") (pinfunction "~{RESET}_5") (pintype "input"))
      (node (ref "U11") (pin "14") (pinfunction "~{RESET}_14") (pintype "bidirectional"))
    )
    (net (code "203") (name "RIGHT_BUT") (class "Default")
      (node (ref "MD1") (pin "~23") (pinfunction "23_~23") (pintype "bidirectional"))
      (node (ref "R79") (pin "1") (pinfunction "1_1") (pintype "passive"))
      (node (ref "S5") (pin "1") (pinfunction "S_1") (pintype "passive"))
      (node (ref "S5") (pin "2") (pinfunction "S1_2") (pintype "passive"))
    )
    (net (code "204") (name "SCL{slash}SCLK") (class "Default")
      (node (ref "J28") (pin "7") (pinfunction "7_7") (pintype "passive"))
      (node (ref "J37") (pin "1") (pinfunction "1_1") (pintype "passive"))
      (node (ref "J37A") (pin "1") (pinfunction "1_1") (pintype "passive"))
      (node (ref "J38") (pin "2") (pinfunction "2_2") (pintype "passive"))
      (node (ref "J41") (pin "1") (pinfunction "1_1") (pintype "passive"))
      (node (ref "U11") (pin "5") (pinfunction "SCL/SCLK_5") (pintype "bidirectional"))
    )
    (net (code "205") (name "SDA") (class "Default")
      (node (ref "J36") (pin "2") (pinfunction "2_2") (pintype "passive"))
      (node (ref "J37") (pin "2") (pinfunction "2_2") (pintype "passive"))
      (node (ref "J37A") (pin "2") (pinfunction "2_2") (pintype "passive"))
      (node (ref "J41") (pin "3") (pinfunction "3_3") (pintype "passive"))
      (node (ref "U11") (pin "6") (pinfunction "SDA_6") (pintype "bidirectional"))
    )
    (net (code "206") (name "SO") (class "Default")
      (node (ref "J28") (pin "5") (pinfunction "5_5") (pintype "passive"))
      (node (ref "J37") (pin "3") (pinfunction "3_3") (pintype "passive"))
      (node (ref "J37A") (pin "3") (pinfunction "3_3") (pintype "passive"))
      (node (ref "U11") (pin "4") (pinfunction "SO_4") (pintype "bidirectional"))
    )
    (net (code "207") (name "SPI1_CS0") (class "Default")
      (node (ref "J28") (pin "2") (pinfunction "2_2") (pintype "passive"))
      (node (ref "J32") (pin "20") (pinfunction "20_20") (pintype "passive"))
      (node (ref "MD1") (pin "~28") (pinfunction "28_~28") (pintype "bidirectional"))
    )
    (net (code "208") (name "SPI1_D0") (class "Default")
      (node (ref "J28") (pin "6") (pinfunction "6_6") (pintype "passive"))
      (node (ref "J32") (pin "22") (pinfunction "22_22") (pintype "passive"))
      (node (ref "MD1") (pin "~29") (pinfunction "29_~29") (pintype "bidirectional"))
    )
    (net (code "209") (name "SPI1_D1") (class "Default")
      (node (ref "J28") (pin "4") (pinfunction "4_4") (pintype "passive"))
      (node (ref "J32") (pin "24") (pinfunction "24_24") (pintype "passive"))
      (node (ref "MD1") (pin "~30") (pinfunction "30_~30") (pintype "bidirectional"))
    )
    (net (code "210") (name "SPI1_SCLK") (class "Default")
      (node (ref "J28") (pin "8") (pinfunction "8_8") (pintype "passive"))
      (node (ref "J32") (pin "26") (pinfunction "26_26") (pintype "passive"))
      (node (ref "MD1") (pin "~31") (pinfunction "31_~31") (pintype "bidirectional"))
    )
    (net (code "211") (name "SYS_5V") (class "Default")
      (node (ref "C24") (pin "2") (pinfunction "-_2") (pintype "passive"))
      (node (ref "C25") (pin "2") (pinfunction "-_2") (pintype "passive"))
      (node (ref "C32") (pin "1") (pinfunction "+_1") (pintype "passive"))
      (node (ref "C33") (pin "1") (pinfunction "+_1") (pintype "passive"))
      (node (ref "C35") (pin "1") (pinfunction "+_1") (pintype "passive"))
      (node (ref "C40") (pin "1") (pinfunction "+_1") (pintype "passive"))
      (node (ref "C5") (pin "1") (pinfunction "+_1") (pintype "passive"))
      (node (ref "J32") (pin "2") (pinfunction "2_2") (pintype "passive"))
      (node (ref "L1") (pin "1") (pinfunction "1_1") (pintype "bidirectional"))
      (node (ref "MD1") (pin "~7") (pinfunction "7_~7") (pintype "bidirectional"))
      (node (ref "MD1") (pin "~8") (pinfunction "8_~8") (pintype "bidirectional"))
      (node (ref "U14") (pin "1") (pinfunction "IN1_1") (pintype "bidirectional"))
      (node (ref "U14") (pin "13") (pinfunction "VCC_13") (pintype "bidirectional"))
      (node (ref "U14") (pin "16") (pinfunction "IN2_16") (pintype "bidirectional"))
      (node (ref "U14") (pin "8") (pinfunction "IN4_8") (pintype "bidirectional"))
      (node (ref "U14") (pin "9") (pinfunction "IN3_9") (pintype "bidirectional"))
      (node (ref "U15") (pin "1") (pinfunction "IN1_1") (pintype "bidirectional"))
      (node (ref "U15") (pin "13") (pinfunction "VCC_13") (pintype "bidirectional"))
      (node (ref "U15") (pin "16") (pinfunction "IN2_16") (pintype "bidirectional"))
      (node (ref "U15") (pin "8") (pinfunction "IN4_8") (pintype "bidirectional"))
      (node (ref "U15") (pin "9") (pinfunction "IN3_9") (pintype "bidirectional"))
      (node (ref "U18") (pin "3") (pinfunction "VCC_3") (pintype "bidirectional"))
      (node (ref "U19") (pin "3") (pinfunction "VCC_3") (pintype "bidirectional"))
      (node (ref "U2") (pin "5") (pinfunction "VIN_5") (pintype "bidirectional"))
      (node (ref "U3") (pin "3") (pinfunction "VCC_3") (pintype "bidirectional"))
    )
    (net (code "212") (name "SYS_~{RESET}") (class "Default")
      (node (ref "J30") (pin "8") (pinfunction "8_8") (pintype "passive"))
      (node (ref "MD1") (pin "~10") (pinfunction "10_~10") (pintype "bidirectional"))
      (node (ref "R76") (pin "1") (pinfunction "1_1") (pintype "passive"))
      (node (ref "S2") (pin "1") (pinfunction "S_1") (pintype "passive"))
      (node (ref "S2") (pin "2") (pinfunction "S1_2") (pintype "passive"))
    )
    (net (code "213") (name "UART0_RX") (class "Default")
      (node (ref "J16") (pin "6") (pinfunction "6_6") (pintype "passive"))
      (node (ref "MD1") (pin "`4") (pinfunction "4_`4") (pintype "bidirectional"))
    )
    (net (code "214") (name "UART0_TX") (class "Default")
      (node (ref "J16") (pin "5") (pinfunction "5_5") (pintype "passive"))
      (node (ref "MD1") (pin "`5") (pinfunction "5_`5") (pintype "bidirectional"))
    )
    (net (code "215") (name "UART2_RX") (class "Default")
      (node (ref "J30") (pin "6") (pinfunction "6_6") (pintype "passive"))
      (node (ref "MD1") (pin "~22") (pinfunction "22_~22") (pintype "bidirectional"))
      (node (ref "U10") (pin "6") (pinfunction "1Y_6") (pintype "output"))
      (node (ref "U4") (pin "6") (pinfunction "1Y_6") (pintype "output"))
      (node (ref "U6") (pin "6") (pinfunction "1Y_6") (pintype "output"))
      (node (ref "U7") (pin "6") (pinfunction "1Y_6") (pintype "output"))
      (node (ref "U8") (pin "6") (pinfunction "1Y_6") (pintype "output"))
      (node (ref "U9") (pin "6") (pinfunction "1Y_6") (pintype "output"))
    )
    (net (code "216") (name "UART2_TX") (class "Default")
      (node (ref "J30") (pin "5") (pinfunction "5_5") (pintype "passive"))
      (node (ref "MD1") (pin "~21") (pinfunction "21_~21") (pintype "bidirectional"))
      (node (ref "U10") (pin "5") (pinfunction "2A_5") (pintype "input"))
      (node (ref "U4") (pin "5") (pinfunction "2A_5") (pintype "input"))
      (node (ref "U6") (pin "5") (pinfunction "2A_5") (pintype "input"))
      (node (ref "U7") (pin "5") (pinfunction "2A_5") (pintype "input"))
      (node (ref "U8") (pin "5") (pinfunction "2A_5") (pintype "input"))
      (node (ref "U9") (pin "5") (pinfunction "2A_5") (pintype "input"))
    )
    (net (code "217") (name "UART_3V3") (class "Default")
      (node (ref "C15") (pin "1") (pinfunction "+_1") (pintype "passive"))
      (node (ref "D1") (pin "A") (pinfunction "A_A") (pintype "passive"))
      (node (ref "D2") (pin "A") (pinfunction "A_A") (pintype "passive"))
      (node (ref "R50") (pin "1") (pinfunction "1_1") (pintype "passive"))
      (node (ref "U5") (pin "13") (pinfunction "3V3OUT_13") (pintype "output"))
      (node (ref "U5") (pin "14") (pinfunction "~{RESET}_14") (pintype "input"))
      (node (ref "U5") (pin "3") (pinfunction "VCCIO_3") (pintype "power_in"))
    )
    (net (code "218") (name "UART_MUX_0") (class "Default")
      (node (ref "J29") (pin "1") (pinfunction "1_1") (pintype "passive"))
      (node (ref "MD1") (pin "7") (pinfunction "7_7") (pintype "bidirectional"))
      (node (ref "U1") (pin "1") (pinfunction "A0_1") (pintype "bidirectional"))
    )
    (net (code "219") (name "UART_MUX_1") (class "Default")
      (node (ref "J29") (pin "6") (pinfunction "6_6") (pintype "passive"))
      (node (ref "MD1") (pin "14") (pinfunction "14_14") (pintype "bidirectional"))
      (node (ref "U1") (pin "2") (pinfunction "A1_2") (pintype "bidirectional"))
    )
    (net (code "220") (name "UART_MUX_2") (class "Default")
      (node (ref "J29") (pin "3") (pinfunction "3_3") (pintype "passive"))
      (node (ref "MD1") (pin "17") (pinfunction "17_17") (pintype "bidirectional"))
      (node (ref "U1") (pin "3") (pinfunction "A2_3") (pintype "bidirectional"))
    )
    (net (code "221") (name "UP_BUT") (class "Default")
      (node (ref "MD1") (pin "~16") (pinfunction "16_~16") (pintype "bidirectional"))
      (node (ref "R77") (pin "1") (pinfunction "1_1") (pintype "passive"))
      (node (ref "S3") (pin "1") (pinfunction "S_1") (pintype "passive"))
      (node (ref "S3") (pin "2") (pinfunction "S1_2") (pintype "passive"))
    )
    (net (code "222") (name "USB_5V") (class "Default")
      (node (ref "C3") (pin "1") (pinfunction "+_1") (pintype "passive"))
      (node (ref "FB1") (pin "2") (pinfunction "P$2_2") (pintype "bidirectional"))
      (node (ref "J12") (pin "1") (pinfunction "1_1") (pintype "passive"))
    )
    (net (code "223") (name "USB_UART_RX") (class "Default")
      (node (ref "J16") (pin "1") (pinfunction "1_1") (pintype "passive"))
      (node (ref "U10") (pin "3") (pinfunction "2Y_3") (pintype "output"))
    )
    (net (code "224") (name "USB_UART_TX") (class "Default")
      (node (ref "J16") (pin "2") (pinfunction "2_2") (pintype "passive"))
      (node (ref "R75") (pin "1") (pinfunction "1_1") (pintype "passive"))
      (node (ref "U10") (pin "2") (pinfunction "1A_2") (pintype "input"))
    )
    (net (code "225") (name "VDD_3V3B") (class "Default")
      (node (ref "C10") (pin "2") (pinfunction "-_2") (pintype "passive"))
      (node (ref "C11") (pin "2") (pinfunction "-_2") (pintype "passive"))
      (node (ref "C13") (pin "1") (pinfunction "+_1") (pintype "passive"))
      (node (ref "C16") (pin "1") (pinfunction "+_1") (pintype "passive"))
      (node (ref "C17") (pin "1") (pinfunction "+_1") (pintype "passive"))
      (node (ref "C34") (pin "1") (pinfunction "+_1") (pintype "passive"))
      (node (ref "C36") (pin "1") (pinfunction "+_1") (pintype "passive"))
      (node (ref "C37") (pin "1") (pinfunction "+_1") (pintype "passive"))
      (node (ref "C39") (pin "1") (pinfunction "+_1") (pintype "passive"))
      (node (ref "C4") (pin "2") (pinfunction "-_2") (pintype "passive"))
      (node (ref "C41") (pin "1") (pinfunction "+_1") (pintype "passive"))
      (node (ref "C42") (pin "1") (pinfunction "+_1") (pintype "passive"))
      (node (ref "C43") (pin "2") (pinfunction "-_2") (pintype "passive"))
      (node (ref "C44") (pin "2") (pinfunction "-_2") (pintype "passive"))
      (node (ref "C45") (pin "2") (pinfunction "-_2") (pintype "passive"))
      (node (ref "C46") (pin "2") (pinfunction "-_2") (pintype "passive"))
      (node (ref "C47") (pin "2") (pinfunction "-_2") (pintype "passive"))
      (node (ref "C7") (pin "2") (pinfunction "-_2") (pintype "passive"))
      (node (ref "C8") (pin "2") (pinfunction "-_2") (pintype "passive"))
      (node (ref "C9") (pin "2") (pinfunction "-_2") (pintype "passive"))
      (node (ref "FB2") (pin "1") (pinfunction "P$1_1") (pintype "bidirectional"))
      (node (ref "J10") (pin "1") (pinfunction "1_1") (pintype "passive"))
      (node (ref "J32") (pin "4") (pinfunction "4_4") (pintype "passive"))
      (node (ref "MD1") (pin "~3") (pinfunction "3_~3") (pintype "bidirectional"))
      (node (ref "MD1") (pin "~4") (pinfunction "4_~4") (pintype "bidirectional"))
      (node (ref "MD2") (pin "~1") (pinfunction "1_~1") (pintype "passive"))
      (node (ref "MD3") (pin "1") (pinfunction "VDD_1") (pintype "power_in"))
      (node (ref "R25") (pin "1") (pinfunction "1_1") (pintype "passive"))
      (node (ref "R29") (pin "1") (pinfunction "1_1") (pintype "passive"))
      (node (ref "R30") (pin "1") (pinfunction "1_1") (pintype "passive"))
      (node (ref "R32") (pin "1") (pinfunction "1_1") (pintype "passive"))
      (node (ref "R33") (pin "1") (pinfunction "1_1") (pintype "passive"))
      (node (ref "R43") (pin "1") (pinfunction "1_1") (pintype "passive"))
      (node (ref "R44") (pin "1") (pinfunction "1_1") (pintype "passive"))
      (node (ref "R45") (pin "1") (pinfunction "1_1") (pintype "passive"))
      (node (ref "R46") (pin "1") (pinfunction "1_1") (pintype "passive"))
      (node (ref "R56") (pin "2") (pinfunction "2_2") (pintype "passive"))
      (node (ref "R58") (pin "1") (pinfunction "1_1") (pintype "passive"))
      (node (ref "R59") (pin "1") (pinfunction "1_1") (pintype "passive"))
      (node (ref "R62") (pin "2") (pinfunction "2_2") (pintype "passive"))
      (node (ref "R63") (pin "1") (pinfunction "1_1") (pintype "passive"))
      (node (ref "R68") (pin "1") (pinfunction "1_1") (pintype "passive"))
      (node (ref "R72") (pin "1") (pinfunction "1_1") (pintype "passive"))
      (node (ref "R73") (pin "2") (pinfunction "2_2") (pintype "passive"))
      (node (ref "R74") (pin "2") (pinfunction "2_2") (pintype "passive"))
      (node (ref "R75") (pin "2") (pinfunction "2_2") (pintype "passive"))
      (node (ref "R76") (pin "2") (pinfunction "2_2") (pintype "passive"))
      (node (ref "R77") (pin "2") (pinfunction "2_2") (pintype "passive"))
      (node (ref "R78") (pin "2") (pinfunction "2_2") (pintype "passive"))
      (node (ref "R79") (pin "2") (pinfunction "2_2") (pintype "passive"))
      (node (ref "R80") (pin "2") (pinfunction "2_2") (pintype "passive"))
      (node (ref "R81") (pin "2") (pinfunction "2_2") (pintype "passive"))
      (node (ref "R83") (pin "1") (pinfunction "1_1") (pintype "passive"))
      (node (ref "R85") (pin "1") (pinfunction "1_1") (pintype "passive"))
      (node (ref "R86") (pin "1") (pinfunction "1_1") (pintype "passive"))
      (node (ref "R87") (pin "1") (pinfunction "1_1") (pintype "passive"))
      (node (ref "R88") (pin "1") (pinfunction "1_1") (pintype "passive"))
      (node (ref "R89") (pin "1") (pinfunction "1_1") (pintype "passive"))
      (node (ref "R90") (pin "1") (pinfunction "1_1") (pintype "passive"))
      (node (ref "R91") (pin "1") (pinfunction "1_1") (pintype "passive"))
      (node (ref "R92") (pin "1") (pinfunction "1_1") (pintype "passive"))
      (node (ref "U1") (pin "16") (pinfunction "VCC_16") (pintype "bidirectional"))
      (node (ref "U1") (pin "6") (pinfunction "OE0_6") (pintype "bidirectional"))
      (node (ref "U10") (pin "8") (pinfunction "VCC_8") (pintype "power_in"))
      (node (ref "U11") (pin "1") (pinfunction "VCC_1") (pintype "bidirectional"))
      (node (ref "U12") (pin "8") (pinfunction "VCC_8") (pintype "power_in"))
      (node (ref "U13") (pin "1") (pinfunction "1OE_1") (pintype "input"))
      (node (ref "U13") (pin "7") (pinfunction "2OE_7") (pintype "input"))
      (node (ref "U13") (pin "8") (pinfunction "VCC_8") (pintype "power_in"))
      (node (ref "U17") (pin "8") (pinfunction "+V2_8") (pintype "bidirectional"))
      (node (ref "U21") (pin "8") (pinfunction "VCC_8") (pintype "power_in"))
      (node (ref "U22") (pin "8") (pinfunction "VCC_8") (pintype "power_in"))
      (node (ref "U23") (pin "8") (pinfunction "VCC_8") (pintype "power_in"))
      (node (ref "U24") (pin "8") (pinfunction "VCC_8") (pintype "power_in"))
      (node (ref "U25") (pin "1") (pinfunction "1OE_1") (pintype "input"))
      (node (ref "U25") (pin "7") (pinfunction "2OE_7") (pintype "input"))
      (node (ref "U25") (pin "8") (pinfunction "VCC_8") (pintype "power_in"))
      (node (ref "U3") (pin "5") (pinfunction "VIO_5") (pintype "bidirectional"))
      (node (ref "U4") (pin "8") (pinfunction "VCC_8") (pintype "power_in"))
      (node (ref "U6") (pin "8") (pinfunction "VCC_8") (pintype "power_in"))
      (node (ref "U7") (pin "8") (pinfunction "VCC_8") (pintype "power_in"))
      (node (ref "U8") (pin "8") (pinfunction "VCC_8") (pintype "power_in"))
      (node (ref "U9") (pin "8") (pinfunction "VCC_8") (pintype "power_in"))
    )
    (net (code "226") (name "VDD_5V") (class "Default")
      (node (ref "C18") (pin "1") (pinfunction "+_1") (pintype "passive"))
      (node (ref "C28") (pin "A") (pinfunction "+_A") (pintype "passive"))
      (node (ref "C29") (pin "1") (pinfunction "+_1") (pintype "passive"))
      (node (ref "D4") (pin "C") (pinfunction "C_C") (pintype "passive"))
      (node (ref "F2") (pin "2") (pinfunction "2_2") (pintype "bidirectional"))
      (node (ref "J32") (pin "6") (pinfunction "6_6") (pintype "passive"))
      (node (ref "R64") (pin "2") (pinfunction "2_2") (pintype "passive"))
      (node (ref "U20") (pin "1") (pinfunction "IN1_1") (pintype "bidirectional"))
      (node (ref "U20") (pin "3") (pinfunction "VBIAS_3") (pintype "bidirectional"))
      (node (ref "U20") (pin "4") (pinfunction "IN2_4") (pintype "bidirectional"))
    )
    (net (code "227") (name "XBEE_AD3{slash}DIO3") (class "Default")
      (node (ref "J27") (pin "1") (pinfunction "1_1") (pintype "passive"))
      (node (ref "MD3") (pin "17") (pinfunction "AD3/DIO3_17") (pintype "bidirectional"))
    )
    (net (code "228") (name "XBEE_AD4{slash}DIO4") (class "Default")
      (node (ref "J27") (pin "5") (pinfunction "5_5") (pintype "passive"))
      (node (ref "MD3") (pin "11") (pinfunction "AD4/DIO4_11") (pintype "bidirectional"))
    )
    (net (code "229") (name "XBEE_AD5{slash}DIO5") (class "Default")
      (node (ref "J27") (pin "2") (pinfunction "2_2") (pintype "passive"))
      (node (ref "MD3") (pin "15") (pinfunction "ASSOC/AD5/DIO5_15") (pintype "bidirectional"))
    )
    (net (code "230") (name "XBEE_ON{slash}SLEEP") (class "Default")
      (node (ref "J27") (pin "4") (pinfunction "4_4") (pintype "passive"))
      (node (ref "MD3") (pin "13") (pinfunction "ON/~{SLEEP}_13") (pintype "bidirectional"))
    )
    (net (code "231") (name "XBEE_PWM1") (class "Default")
      (node (ref "J27") (pin "6") (pinfunction "6_6") (pintype "passive"))
      (node (ref "MD3") (pin "7") (pinfunction "PWM1_7") (pintype "bidirectional"))
    )
    (net (code "232") (name "XBEE_RX") (class "Default")
      (node (ref "J19") (pin "4") (pinfunction "4_4") (pintype "passive"))
      (node (ref "MD3") (pin "3") (pinfunction "DIN/~{CONFIG}_3") (pintype "input"))
      (node (ref "U21") (pin "2") (pinfunction "1A_2") (pintype "input"))
      (node (ref "U9") (pin "3") (pinfunction "2Y_3") (pintype "output"))
    )
    (net (code "233") (name "XBEE_SEL") (class "Default")
      (node (ref "U1") (pin "10") (pinfunction "Y5_10") (pintype "bidirectional"))
      (node (ref "U21") (pin "1") (pinfunction "1OE_1") (pintype "input"))
      (node (ref "U21") (pin "7") (pinfunction "2OE_7") (pintype "input"))
      (node (ref "U9") (pin "1") (pinfunction "1OE_1") (pintype "input"))
      (node (ref "U9") (pin "7") (pinfunction "2OE_7") (pintype "input"))
    )
    (net (code "234") (name "XBEE_TX") (class "Default")
      (node (ref "J19") (pin "3") (pinfunction "3_3") (pintype "passive"))
      (node (ref "MD3") (pin "2") (pinfunction "DOUT_2") (pintype "output"))
      (node (ref "U21") (pin "5") (pinfunction "2A_5") (pintype "input"))
      (node (ref "U9") (pin "2") (pinfunction "1A_2") (pintype "input"))
    )
    (net (code "235") (name "XBEE_VREF") (class "Default")
      (node (ref "J27") (pin "3") (pinfunction "3_3") (pintype "passive"))
      (node (ref "MD3") (pin "14") (pinfunction "VREF_14") (pintype "bidirectional"))
    )
    (net (code "236") (name "XBEE_~{CTS}") (class "Default")
      (node (ref "J15") (pin "4") (pinfunction "4_4") (pintype "passive"))
      (node (ref "MD3") (pin "12") (pinfunction "~{CTS}/DIO7_12") (pintype "output"))
    )
    (net (code "237") (name "XBEE_~{DTR}") (class "Default")
      (node (ref "J15") (pin "6") (pinfunction "6_6") (pintype "passive"))
      (node (ref "MD3") (pin "9") (pinfunction "~{DTR}/SLEEP_RQ/DI8_9") (pintype "bidirectional"))
    )
    (net (code "238") (name "XBEE_~{RTS}") (class "Default")
      (node (ref "J15") (pin "2") (pinfunction "2_2") (pintype "passive"))
      (node (ref "MD3") (pin "16") (pinfunction "~{RTS}/DIO6_16") (pintype "input"))
    )
    (net (code "239") (name "unconnected-(J12-Pad4)") (class "Default")
      (node (ref "J12") (pin "4") (pinfunction "4_4") (pintype "passive"))
    )
    (net (code "240") (name "unconnected-(J20-Pad2)") (class "Default")
      (node (ref "J20") (pin "2") (pinfunction "2_2") (pintype "passive"))
    )
    (net (code "241") (name "unconnected-(J20-Pad3)") (class "Default")
      (node (ref "J20") (pin "3") (pinfunction "3_3") (pintype "passive"))
    )
    (net (code "242") (name "unconnected-(J20A-Pad2)") (class "Default")
      (node (ref "J20A") (pin "2") (pinfunction "2_2") (pintype "passive"))
    )
    (net (code "243") (name "unconnected-(J20A-Pad3)") (class "Default")
      (node (ref "J20A") (pin "3") (pinfunction "3_3") (pintype "passive"))
    )
    (net (code "244") (name "unconnected-(J28-Pad10)") (class "Default")
      (node (ref "J28") (pin "10") (pinfunction "10_10") (pintype "passive"))
    )
    (net (code "245") (name "unconnected-(J28-Pad12)") (class "Default")
      (node (ref "J28") (pin "12") (pinfunction "12_12") (pintype "passive"))
    )
    (net (code "246") (name "unconnected-(J32-Pad3)") (class "Default")
      (node (ref "J32") (pin "3") (pinfunction "3_3") (pintype "passive"))
    )
    (net (code "247") (name "unconnected-(J32-Pad5)") (class "Default")
      (node (ref "J32") (pin "5") (pinfunction "5_5") (pintype "passive"))
    )
    (net (code "248") (name "unconnected-(MD1B-25-Pad~25)") (class "Default")
      (node (ref "MD1") (pin "~25") (pinfunction "25_~25") (pintype "bidirectional"))
    )
    (net (code "249") (name "unconnected-(MD1B-32-Pad~32)") (class "Default")
      (node (ref "MD1") (pin "~32") (pinfunction "32_~32") (pintype "bidirectional"))
    )
    (net (code "250") (name "unconnected-(MD1C-2-Pad`2)") (class "Default")
      (node (ref "MD1") (pin "`2") (pinfunction "2_`2") (pintype "bidirectional"))
    )
    (net (code "251") (name "unconnected-(MD1C-3-Pad`3)") (class "Default")
      (node (ref "MD1") (pin "`3") (pinfunction "3_`3") (pintype "bidirectional"))
    )
    (net (code "252") (name "unconnected-(MD1C-6-Pad`6)") (class "Default")
      (node (ref "MD1") (pin "`6") (pinfunction "6_`6") (pintype "bidirectional"))
    )
    (net (code "253") (name "unconnected-(MD2-Pad35)") (class "Default")
      (node (ref "MD2") (pin "35") (pinfunction "35_35") (pintype "passive"))
    )
    (net (code "254") (name "unconnected-(MD2-Pad37)") (class "Default")
      (node (ref "MD2") (pin "37") (pinfunction "37_37") (pintype "passive"))
    )
    (net (code "255") (name "unconnected-(MD2-Pad38)") (class "Default")
      (node (ref "MD2") (pin "38") (pinfunction "38_38") (pintype "passive"))
    )
    (net (code "256") (name "unconnected-(MD2-Pad39)") (class "Default")
      (node (ref "MD2") (pin "39") (pinfunction "39_39") (pintype "passive"))
    )
    (net (code "257") (name "unconnected-(MD2-Pad40)") (class "Default")
      (node (ref "MD2") (pin "40") (pinfunction "40_40") (pintype "passive"))
    )
    (net (code "258") (name "unconnected-(MD3-AD0{slash}DIO0-Pad20)") (class "Default")
      (node (ref "MD3") (pin "20") (pinfunction "AD0/DIO0_20") (pintype "bidirectional"))
    )
    (net (code "259") (name "unconnected-(MD3-AD1{slash}DIO1-Pad19)") (class "Default")
      (node (ref "MD3") (pin "19") (pinfunction "AD1/DIO1_19") (pintype "bidirectional"))
    )
    (net (code "260") (name "unconnected-(MD3-AD2{slash}DIO2-Pad18)") (class "Default")
      (node (ref "MD3") (pin "18") (pinfunction "AD2/DIO2_18") (pintype "bidirectional"))
    )
    (net (code "261") (name "unconnected-(MD3-D08*-Pad4)") (class "Default")
      (node (ref "MD3") (pin "4") (pinfunction "D08*_4") (pintype "bidirectional"))
    )
    (net (code "262") (name "unconnected-(MD3-RESERVED-Pad8)") (class "Default")
      (node (ref "MD3") (pin "8") (pinfunction "RESERVED_8") (pintype "bidirectional"))
    )
    (net (code "263") (name "unconnected-(R84-Pad1)") (class "Default")
      (node (ref "R84") (pin "1") (pinfunction "1_1") (pintype "passive"))
    )
    (net (code "264") (name "unconnected-(R84-Pad2)") (class "Default")
      (node (ref "R84") (pin "2") (pinfunction "2_2") (pintype "passive"))
    )
    (net (code "265") (name "unconnected-(R95-Pad1)") (class "Default")
      (node (ref "R95") (pin "1") (pinfunction "1_1") (pintype "passive"))
    )
    (net (code "266") (name "unconnected-(R95-Pad2)") (class "Default")
      (node (ref "R95") (pin "2") (pinfunction "2_2") (pintype "passive"))
    )
    (net (code "267") (name "unconnected-(R96-Pad1)") (class "Default")
      (node (ref "R96") (pin "1") (pinfunction "1_1") (pintype "passive"))
    )
    (net (code "268") (name "unconnected-(R96-Pad2)") (class "Default")
      (node (ref "R96") (pin "2") (pinfunction "2_2") (pintype "passive"))
    )
    (net (code "269") (name "unconnected-(R97-Pad1)") (class "Default")
      (node (ref "R97") (pin "1") (pinfunction "1_1") (pintype "passive"))
    )
    (net (code "270") (name "unconnected-(R97-Pad2)") (class "Default")
      (node (ref "R97") (pin "2") (pinfunction "2_2") (pintype "passive"))
    )
    (net (code "271") (name "unconnected-(U1-Y0-Pad15)") (class "Default")
      (node (ref "U1") (pin "15") (pinfunction "Y0_15") (pintype "bidirectional"))
    )
    (net (code "272") (name "unconnected-(U1-Y7-Pad7)") (class "Default")
      (node (ref "U1") (pin "7") (pinfunction "Y7_7") (pintype "bidirectional"))
    )
    (net (code "273") (name "unconnected-(U5-CBUS0-Pad18)") (class "Default")
      (node (ref "U5") (pin "18") (pinfunction "CBUS0_18") (pintype "bidirectional"))
    )
    (net (code "274") (name "unconnected-(U5-CBUS3-Pad19)") (class "Default")
      (node (ref "U5") (pin "19") (pinfunction "CBUS3_19") (pintype "bidirectional"))
    )
    (net (code "275") (name "unconnected-(U5-~{DCD}-Pad8)") (class "Default")
      (node (ref "U5") (pin "8") (pinfunction "~{DCD}_8") (pintype "input"))
    )
    (net (code "276") (name "unconnected-(U5-~{DSR}-Pad7)") (class "Default")
      (node (ref "U5") (pin "7") (pinfunction "~{DSR}_7") (pintype "input"))
    )
    (net (code "277") (name "unconnected-(U11-XTAL2-Pad16)") (class "Default")
      (node (ref "U11") (pin "16") (pinfunction "XTAL2_16") (pintype "bidirectional"))
    )
    (net (code "278") (name "unconnected-(U11-~{CTS}-Pad11)") (class "Default")
      (node (ref "U11") (pin "11") (pinfunction "~{CTS}_11") (pintype "bidirectional"))
    )
    (net (code "279") (name "unconnected-(U11-~{RTS}-Pad10)") (class "Default")
      (node (ref "U11") (pin "10") (pinfunction "~{RTS}_10") (pintype "bidirectional"))
    )
    (net (code "280") (name "unconnected-(U15-D4-Pad7)") (class "Default")
      (node (ref "U15") (pin "7") (pinfunction "D4_7") (pintype "bidirectional"))
    )
    (net (code "281") (name "unconnected-(U15-S4-Pad6)") (class "Default")
      (node (ref "U15") (pin "6") (pinfunction "S4_6") (pintype "bidirectional"))
    )
    (net (code "282") (name "~{IRQ}") (class "Default")
      (node (ref "J37") (pin "4") (pinfunction "4_4") (pintype "passive"))
      (node (ref "J37A") (pin "4") (pinfunction "4_4") (pintype "passive"))
      (node (ref "R58") (pin "2") (pinfunction "2_2") (pintype "passive"))
      (node (ref "R82") (pin "1") (pinfunction "1_1") (pintype "passive"))
      (node (ref "U11") (pin "7") (pinfunction "~{IRQ}_7") (pintype "bidirectional"))
    )
    (net (code "283") (name "~{LCD_BACKLIGHT}") (class "Default")
      (node (ref "MD1") (pin "~14") (pinfunction "14_~14") (pintype "bidirectional"))
      (node (ref "U2") (pin "4") (pinfunction "~{SHDN}_4") (pintype "bidirectional"))
    )
  )
)
